# Bhoreal_Slimpro.net
KiCad netlist of a schematic drawn in EAGLE
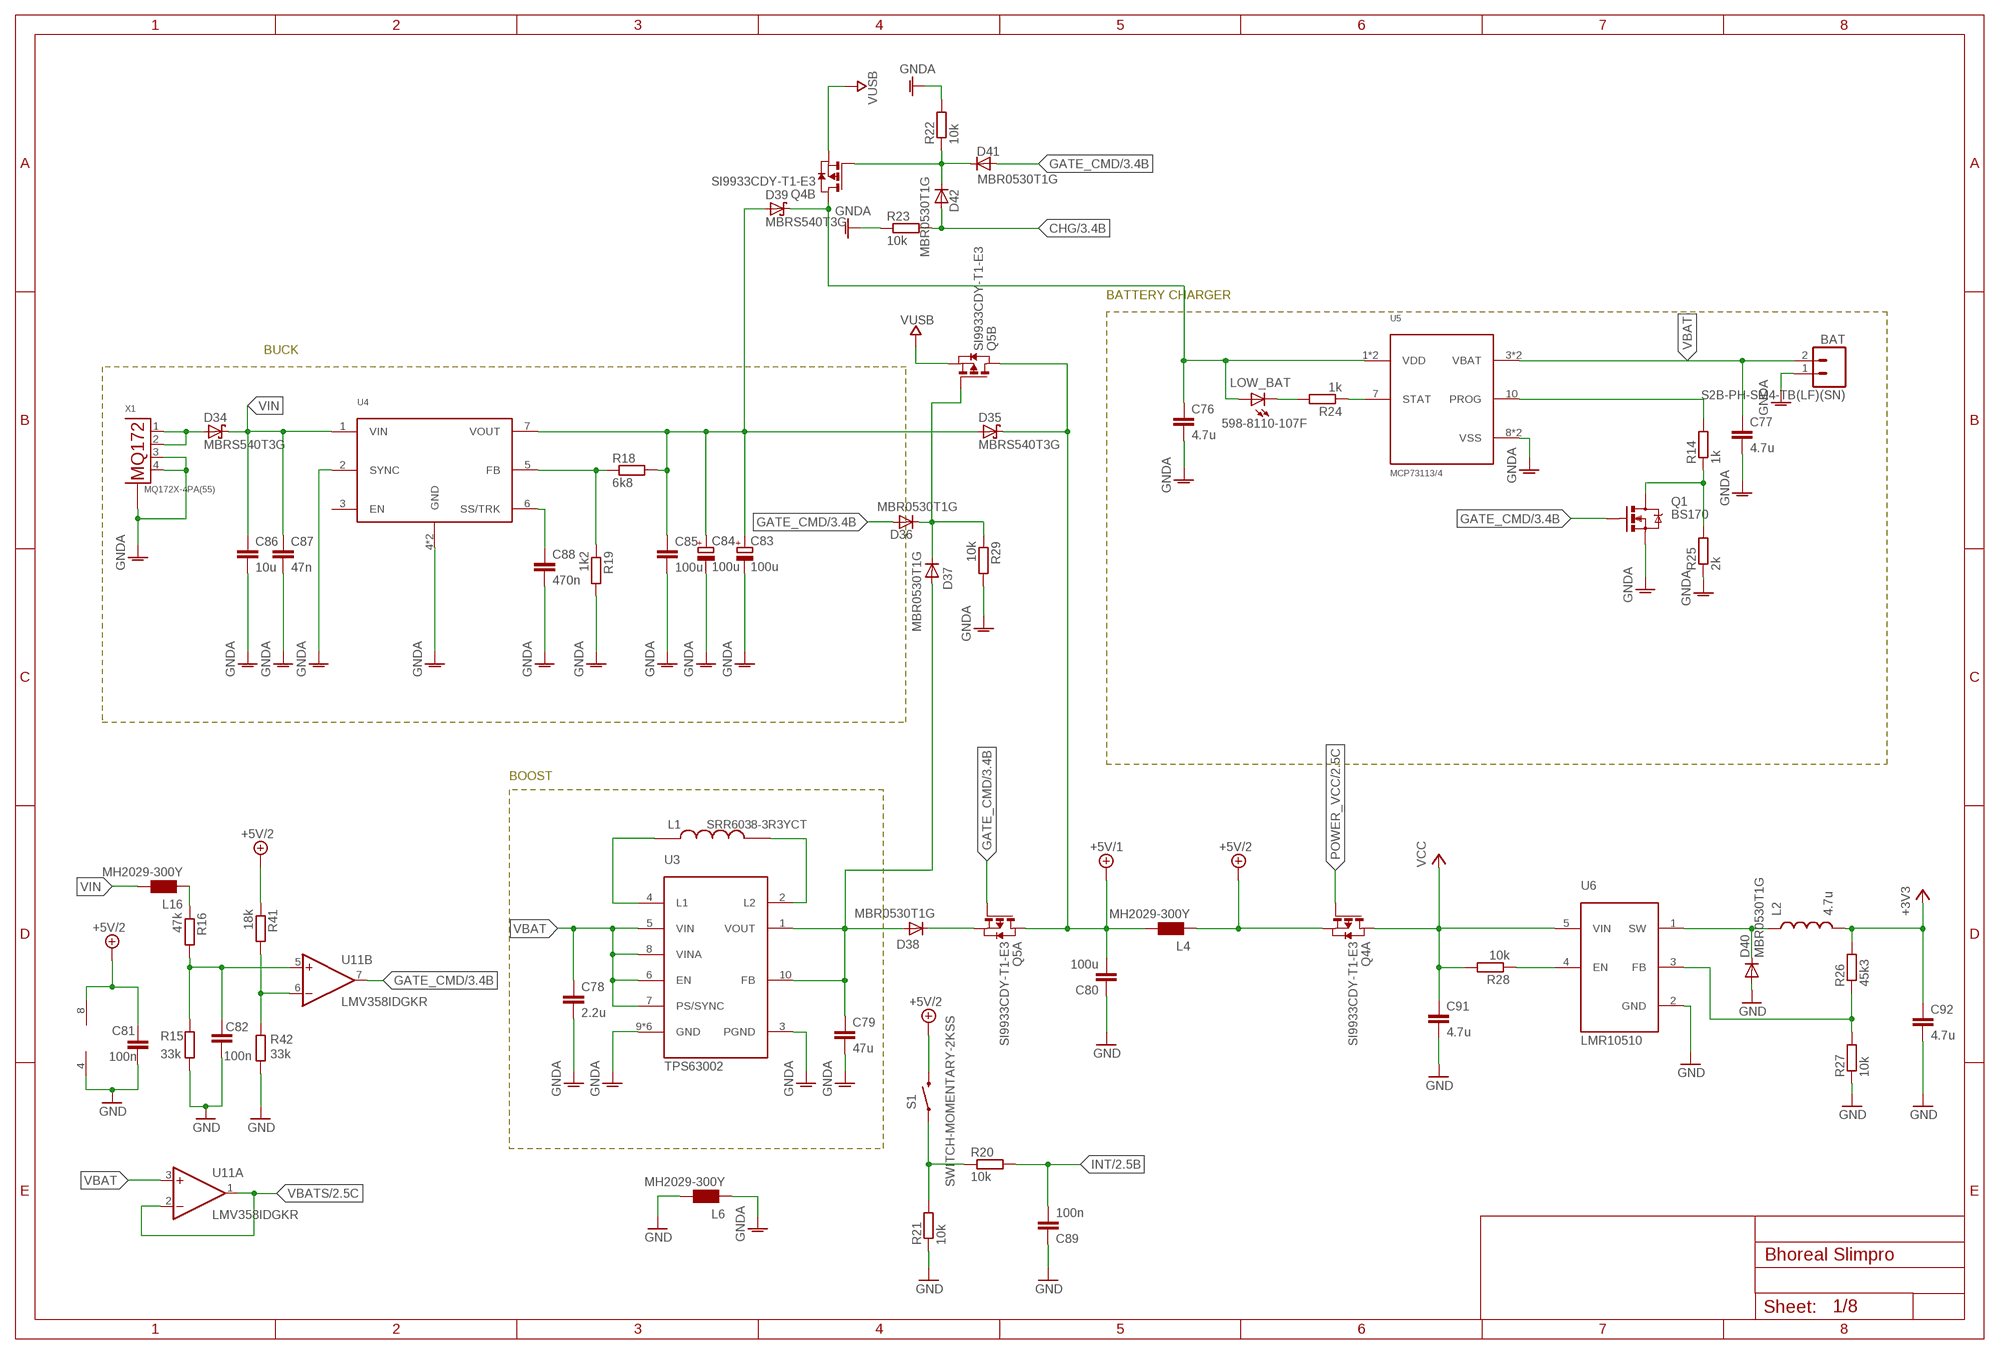
[diagram p0: schematic, sheet 1]
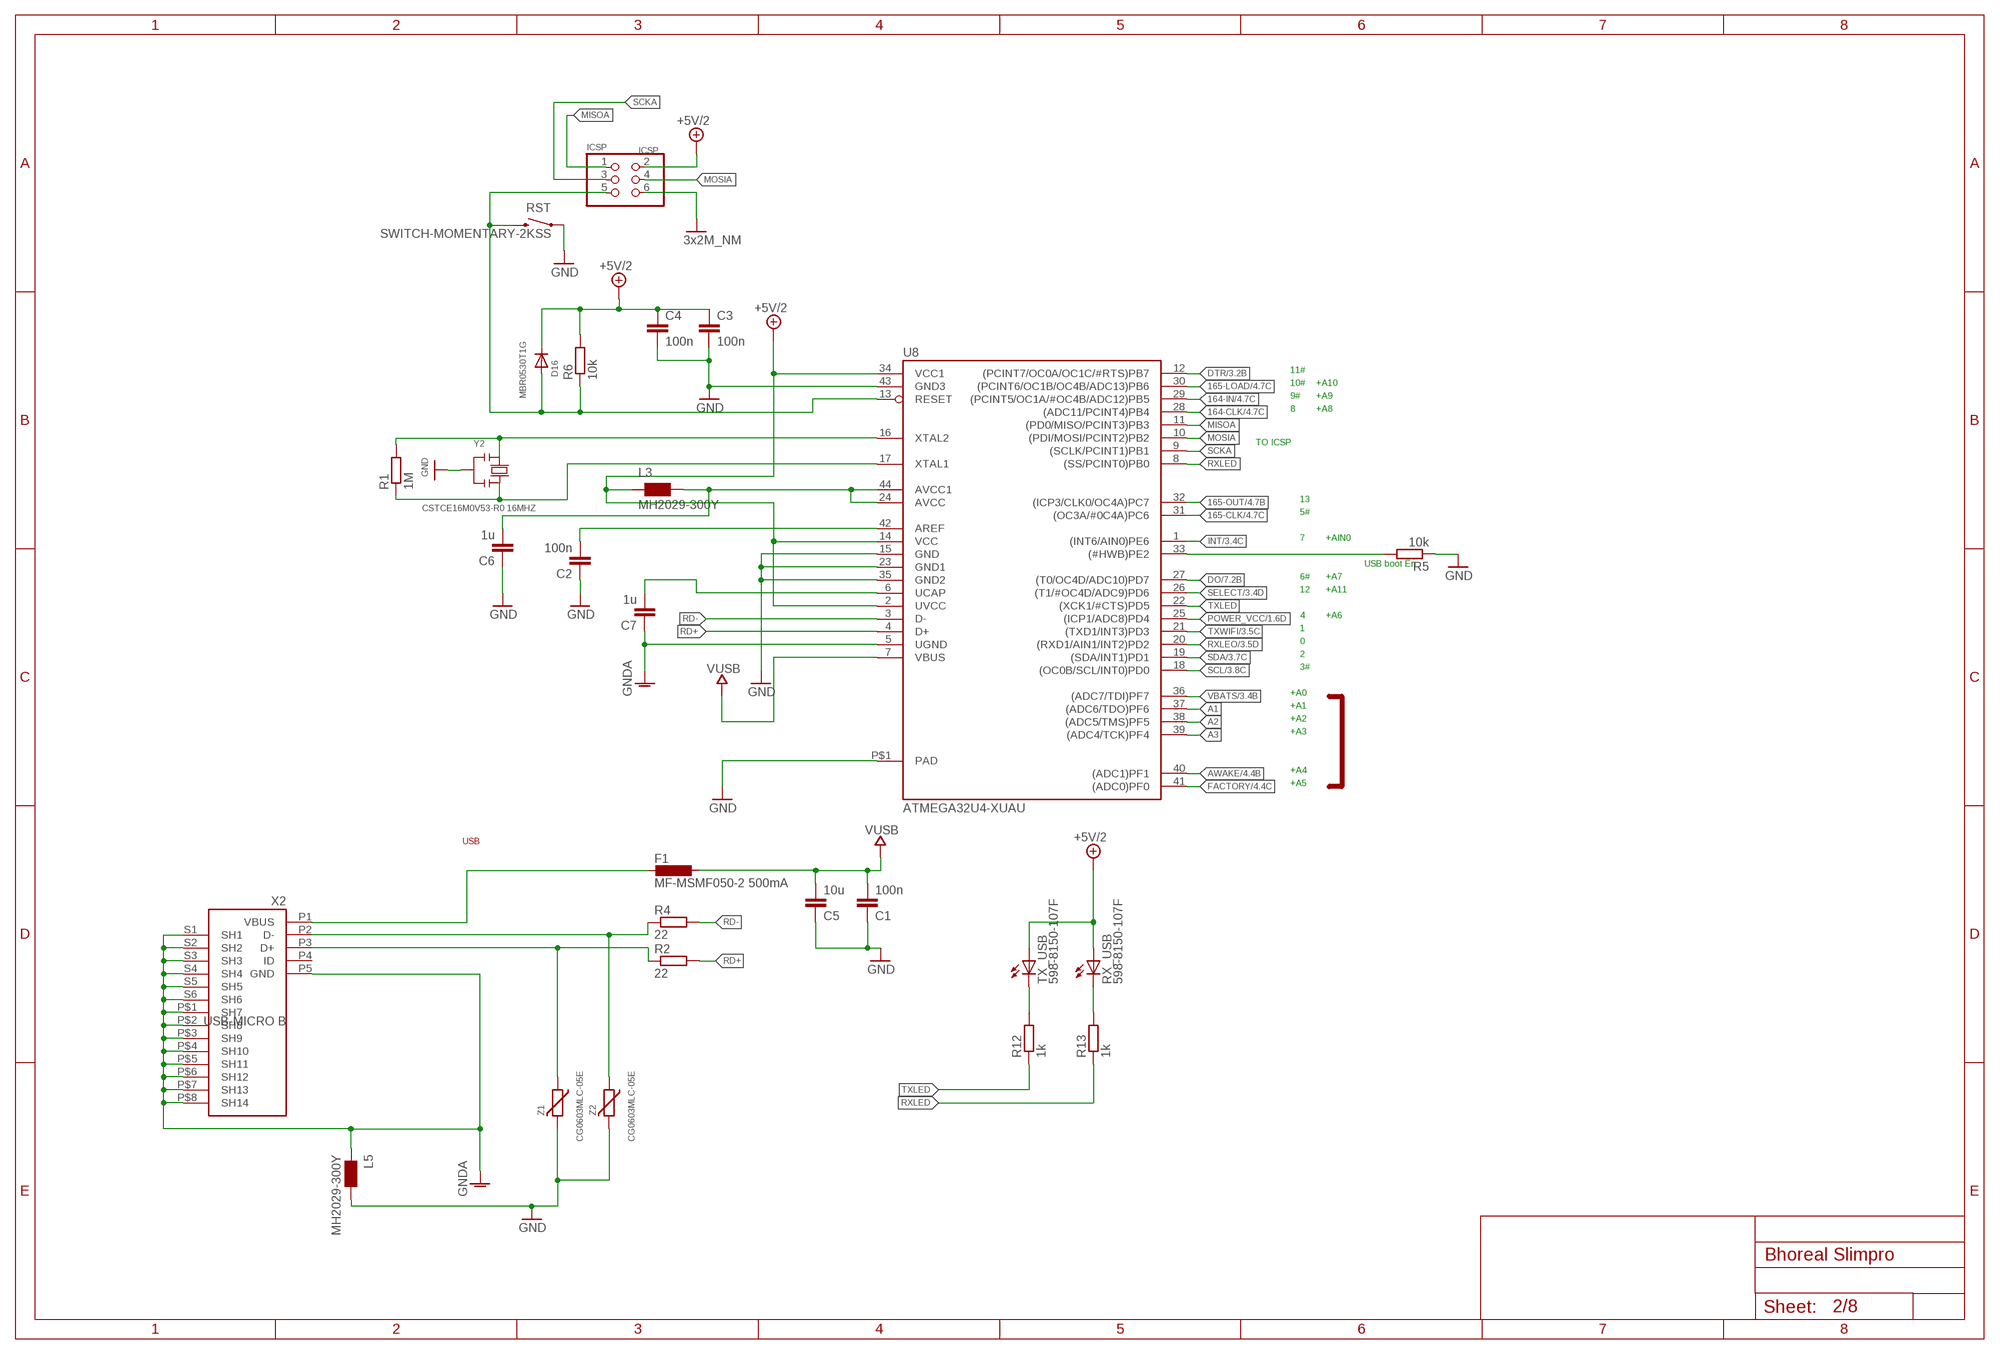
[diagram p1: schematic, sheet 2]
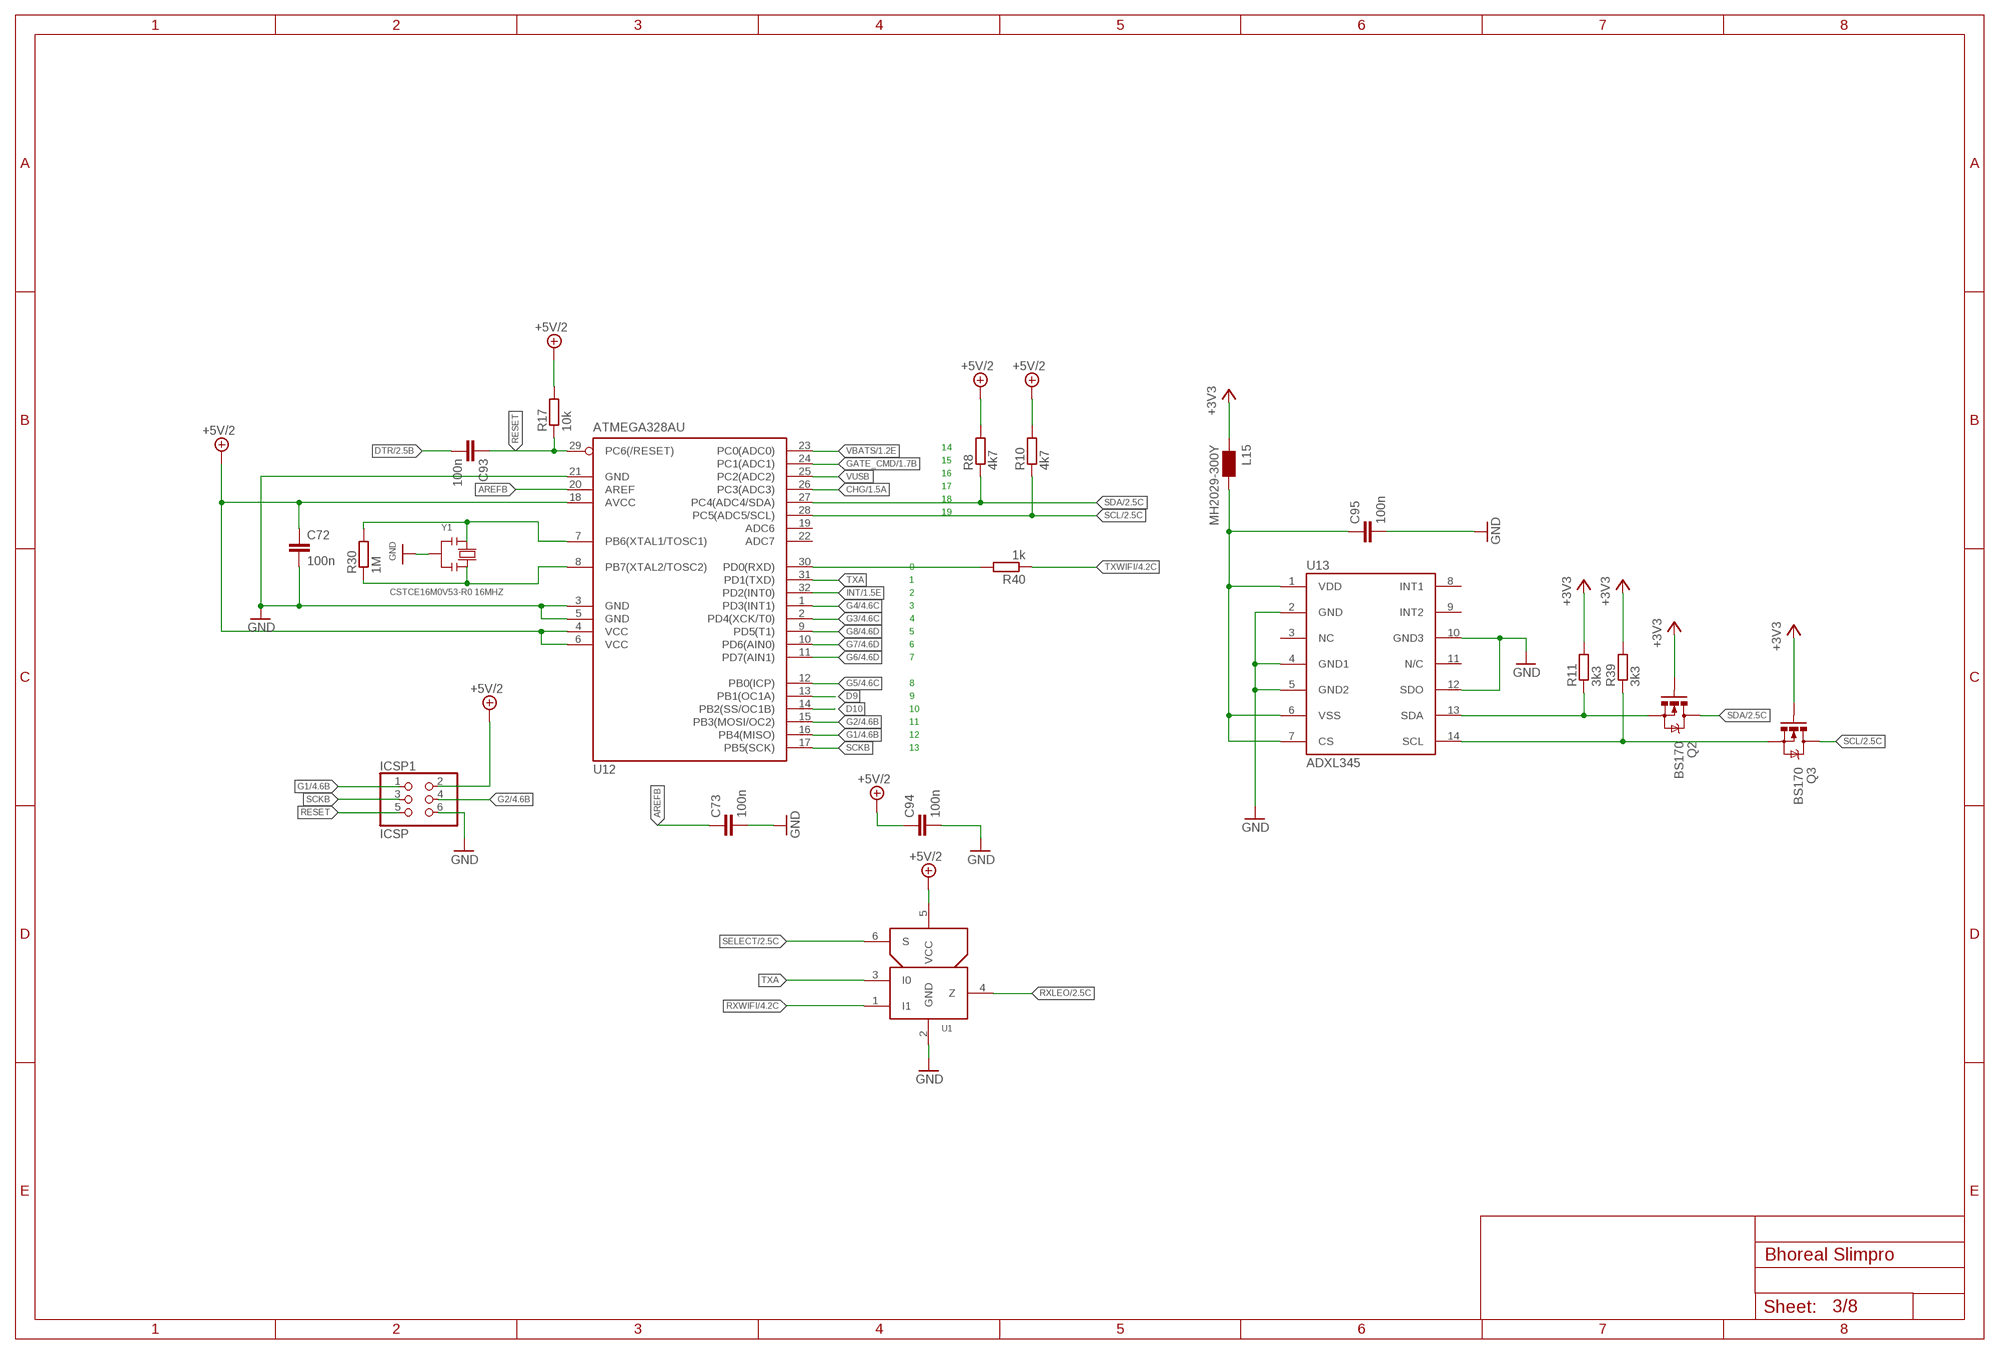
[diagram p2: schematic, sheet 3]
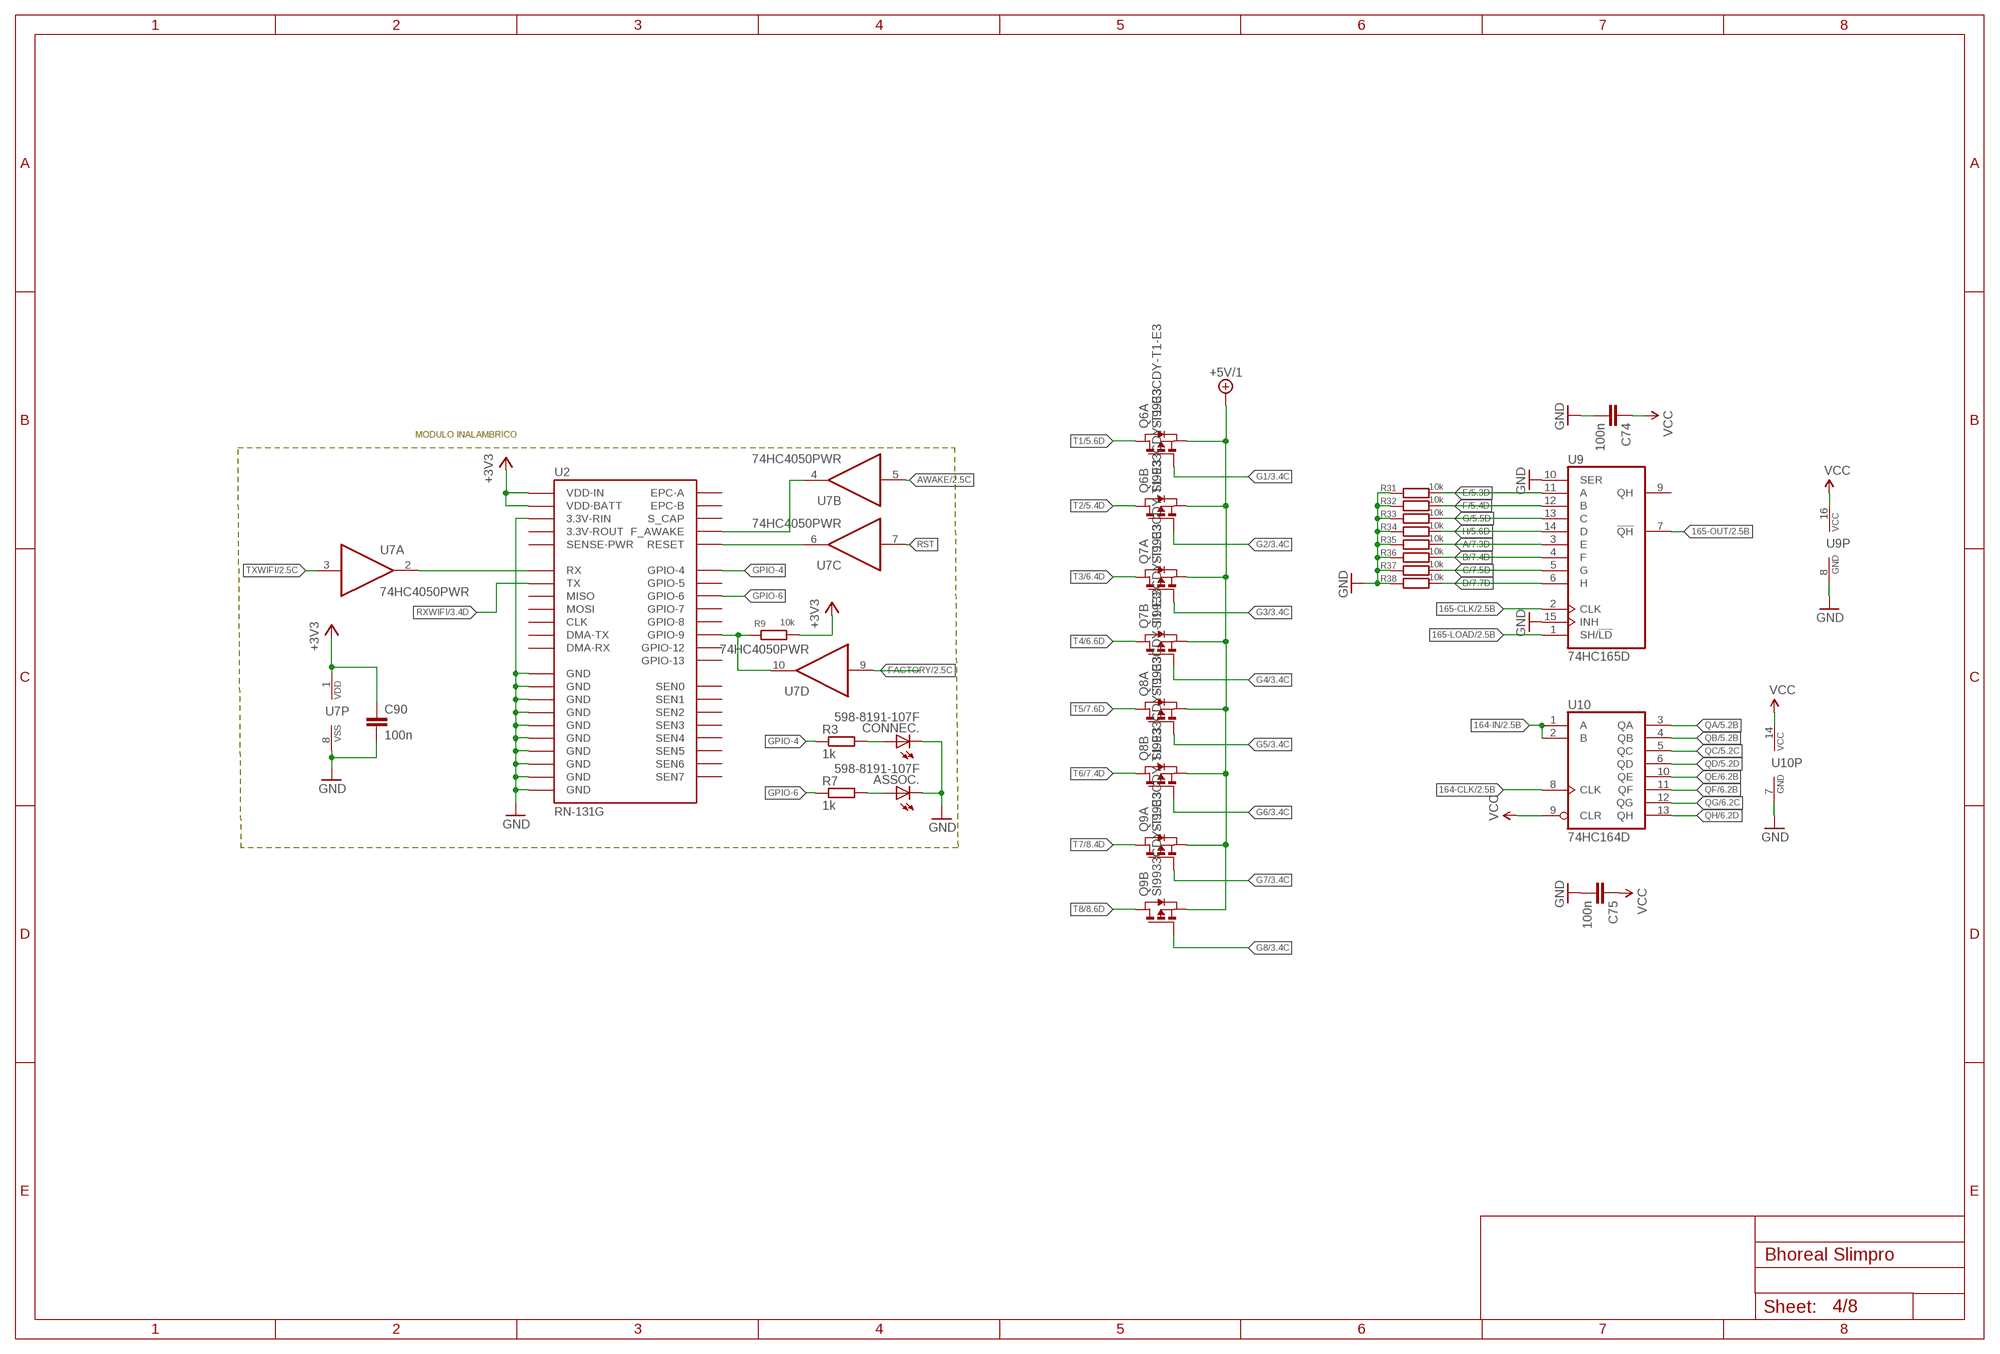
[diagram p3: schematic, sheet 4]
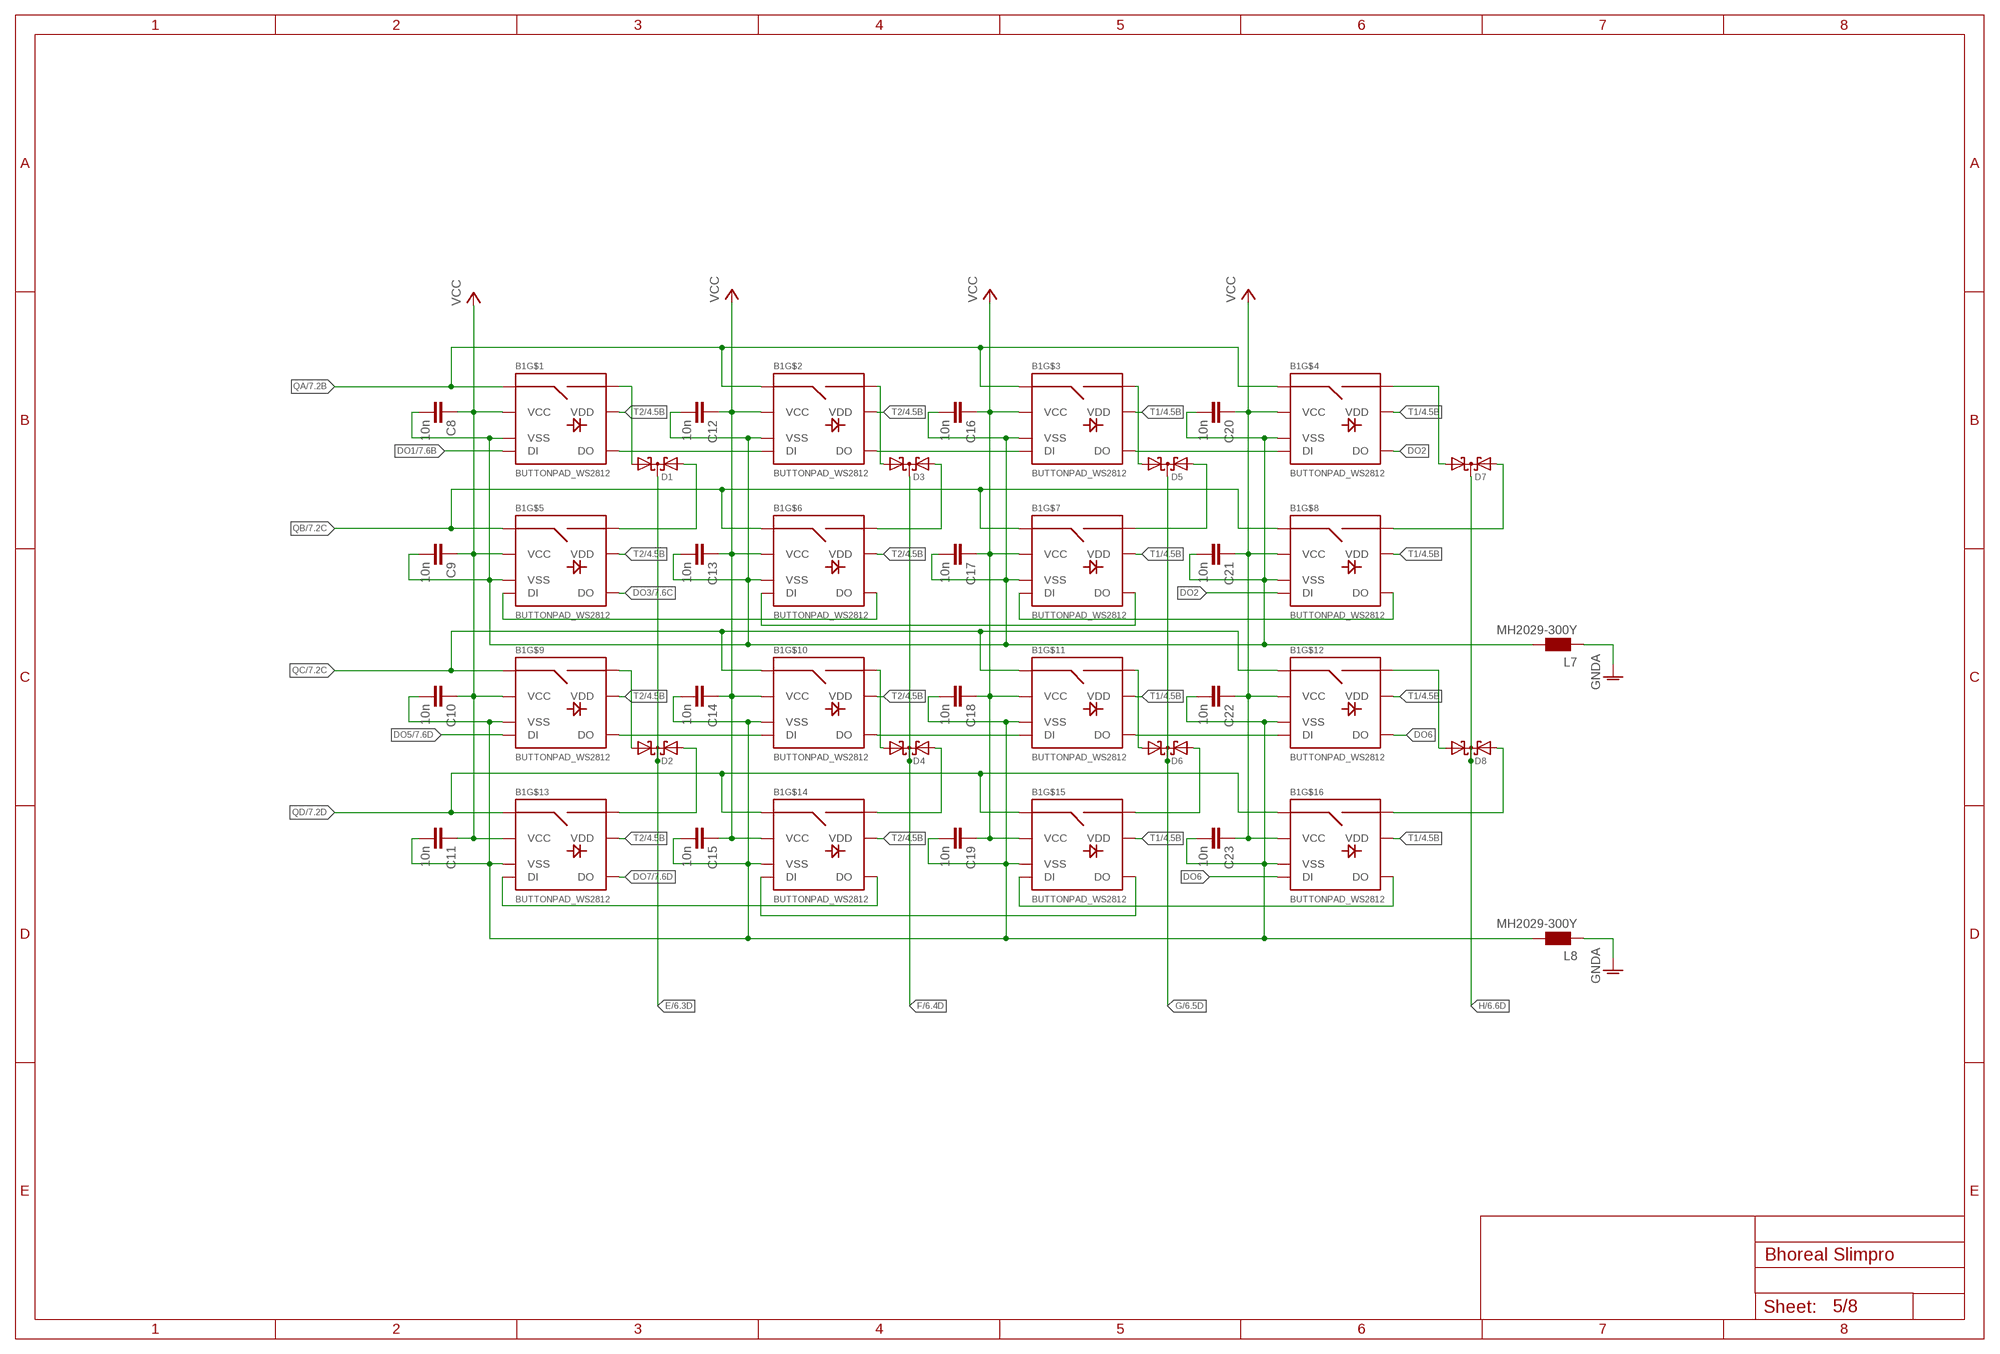
[diagram p4: schematic, sheet 5]
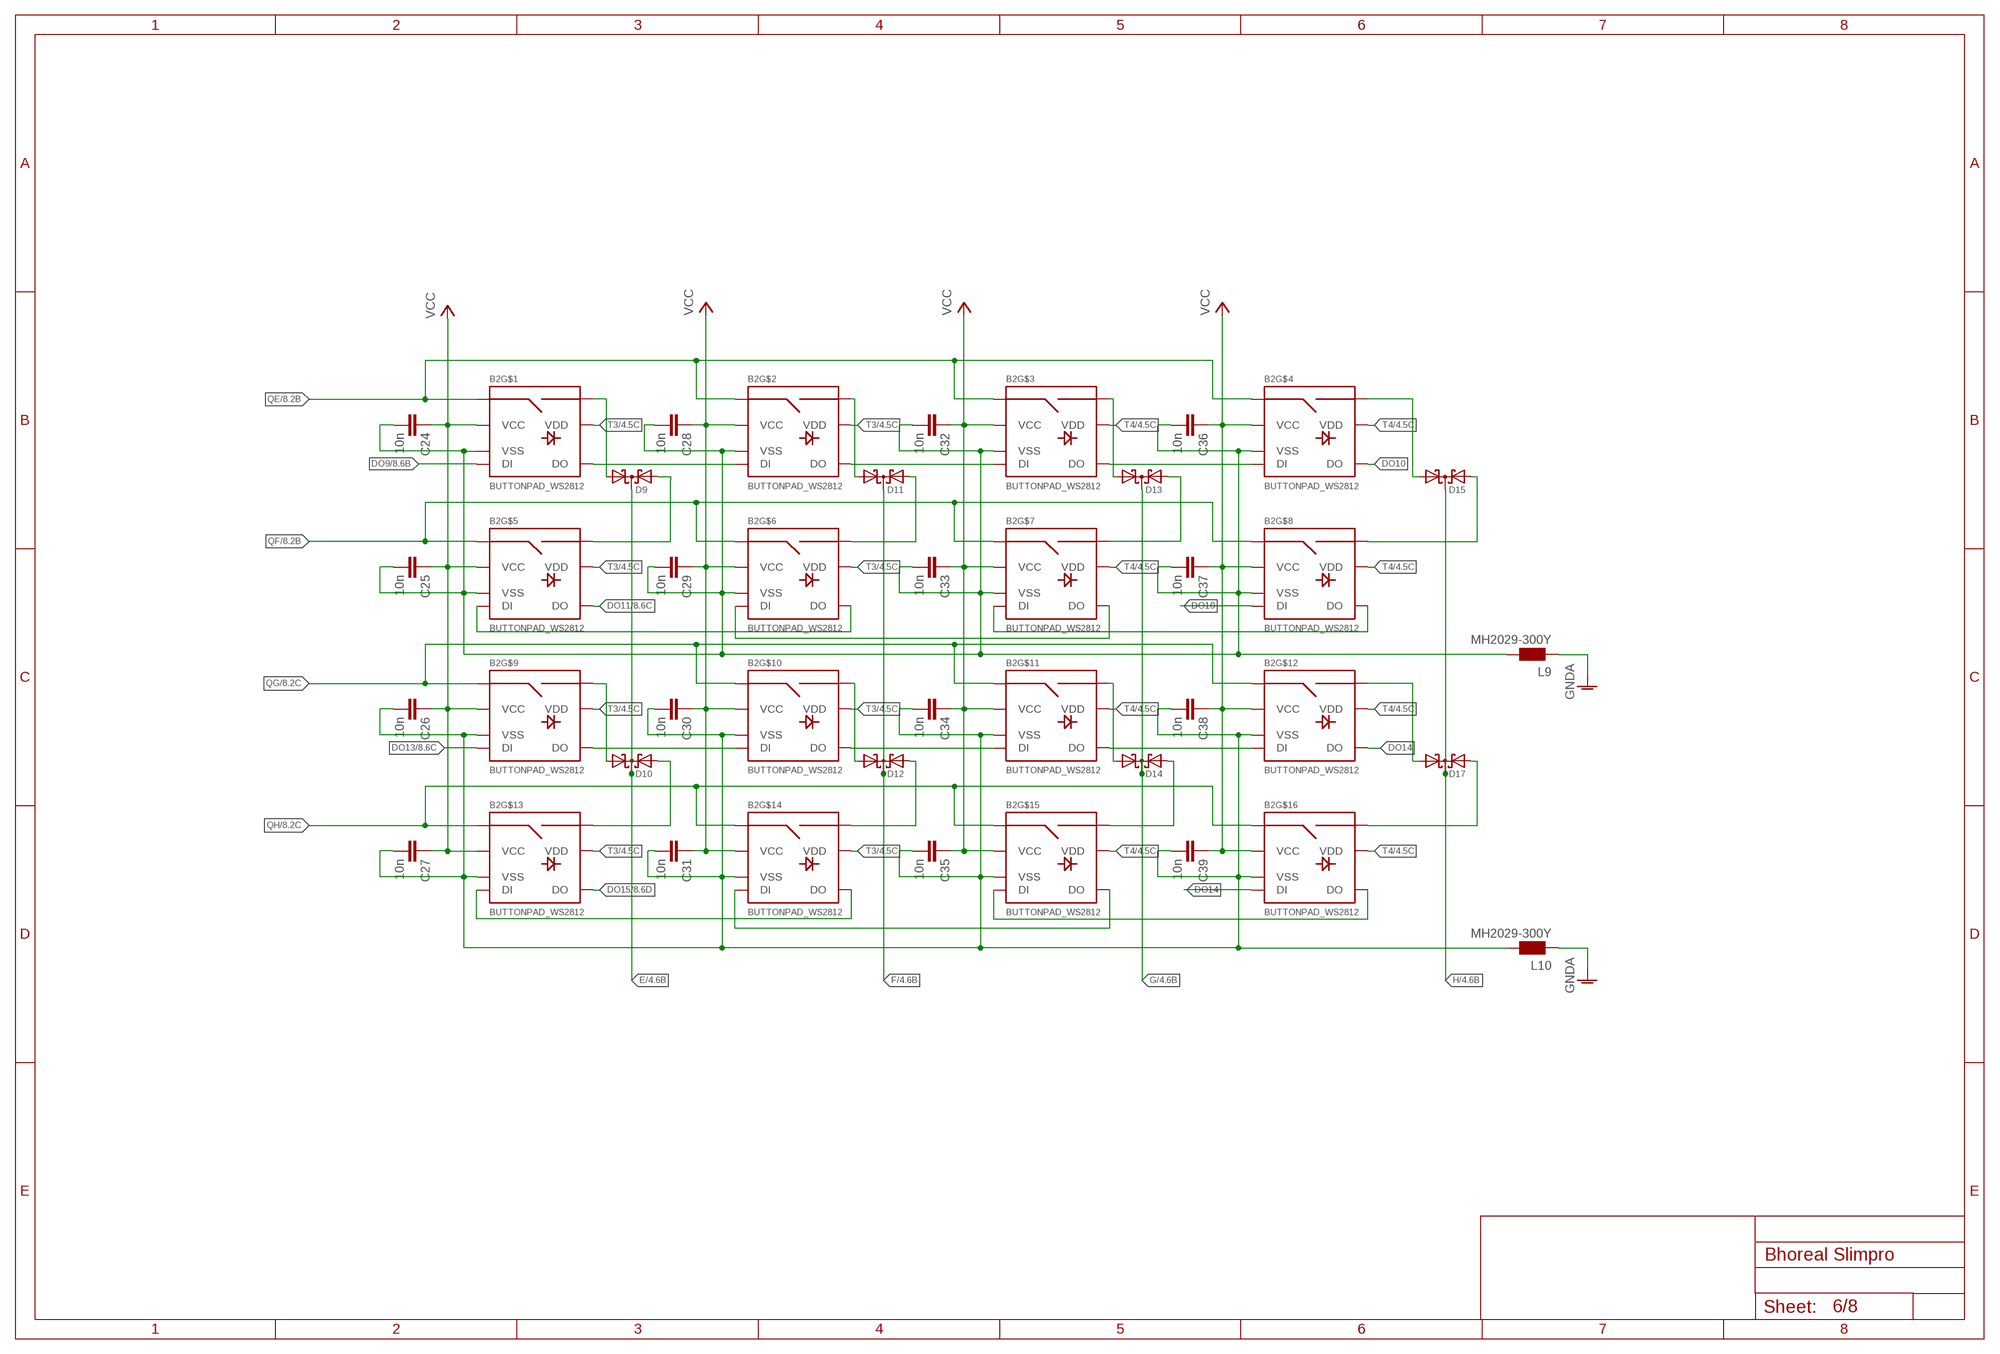
[diagram p5: schematic, sheet 6]
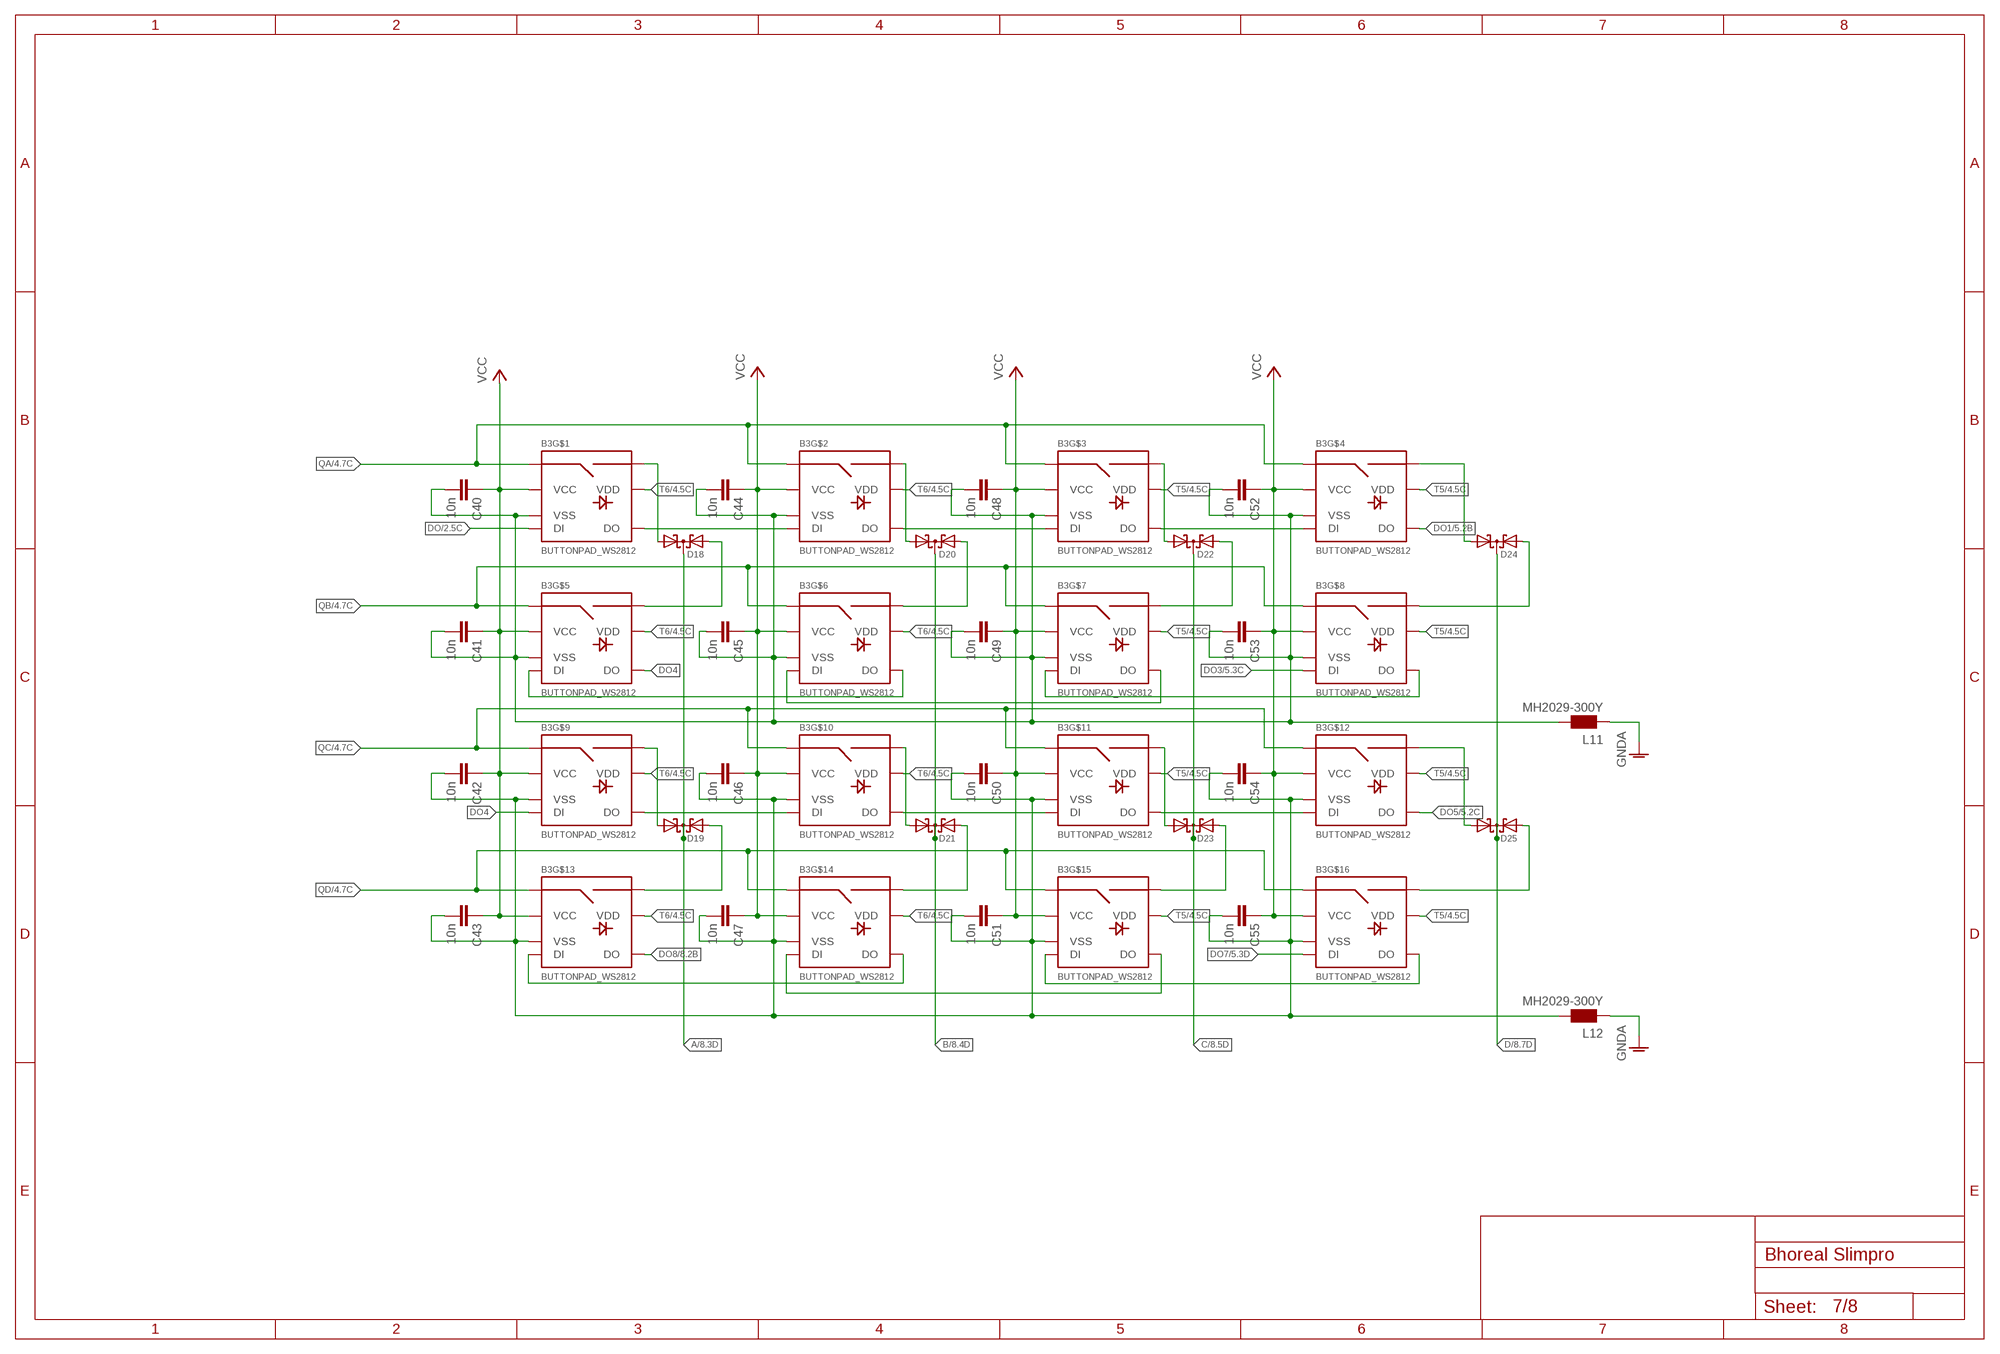
[diagram p6: schematic, sheet 7]
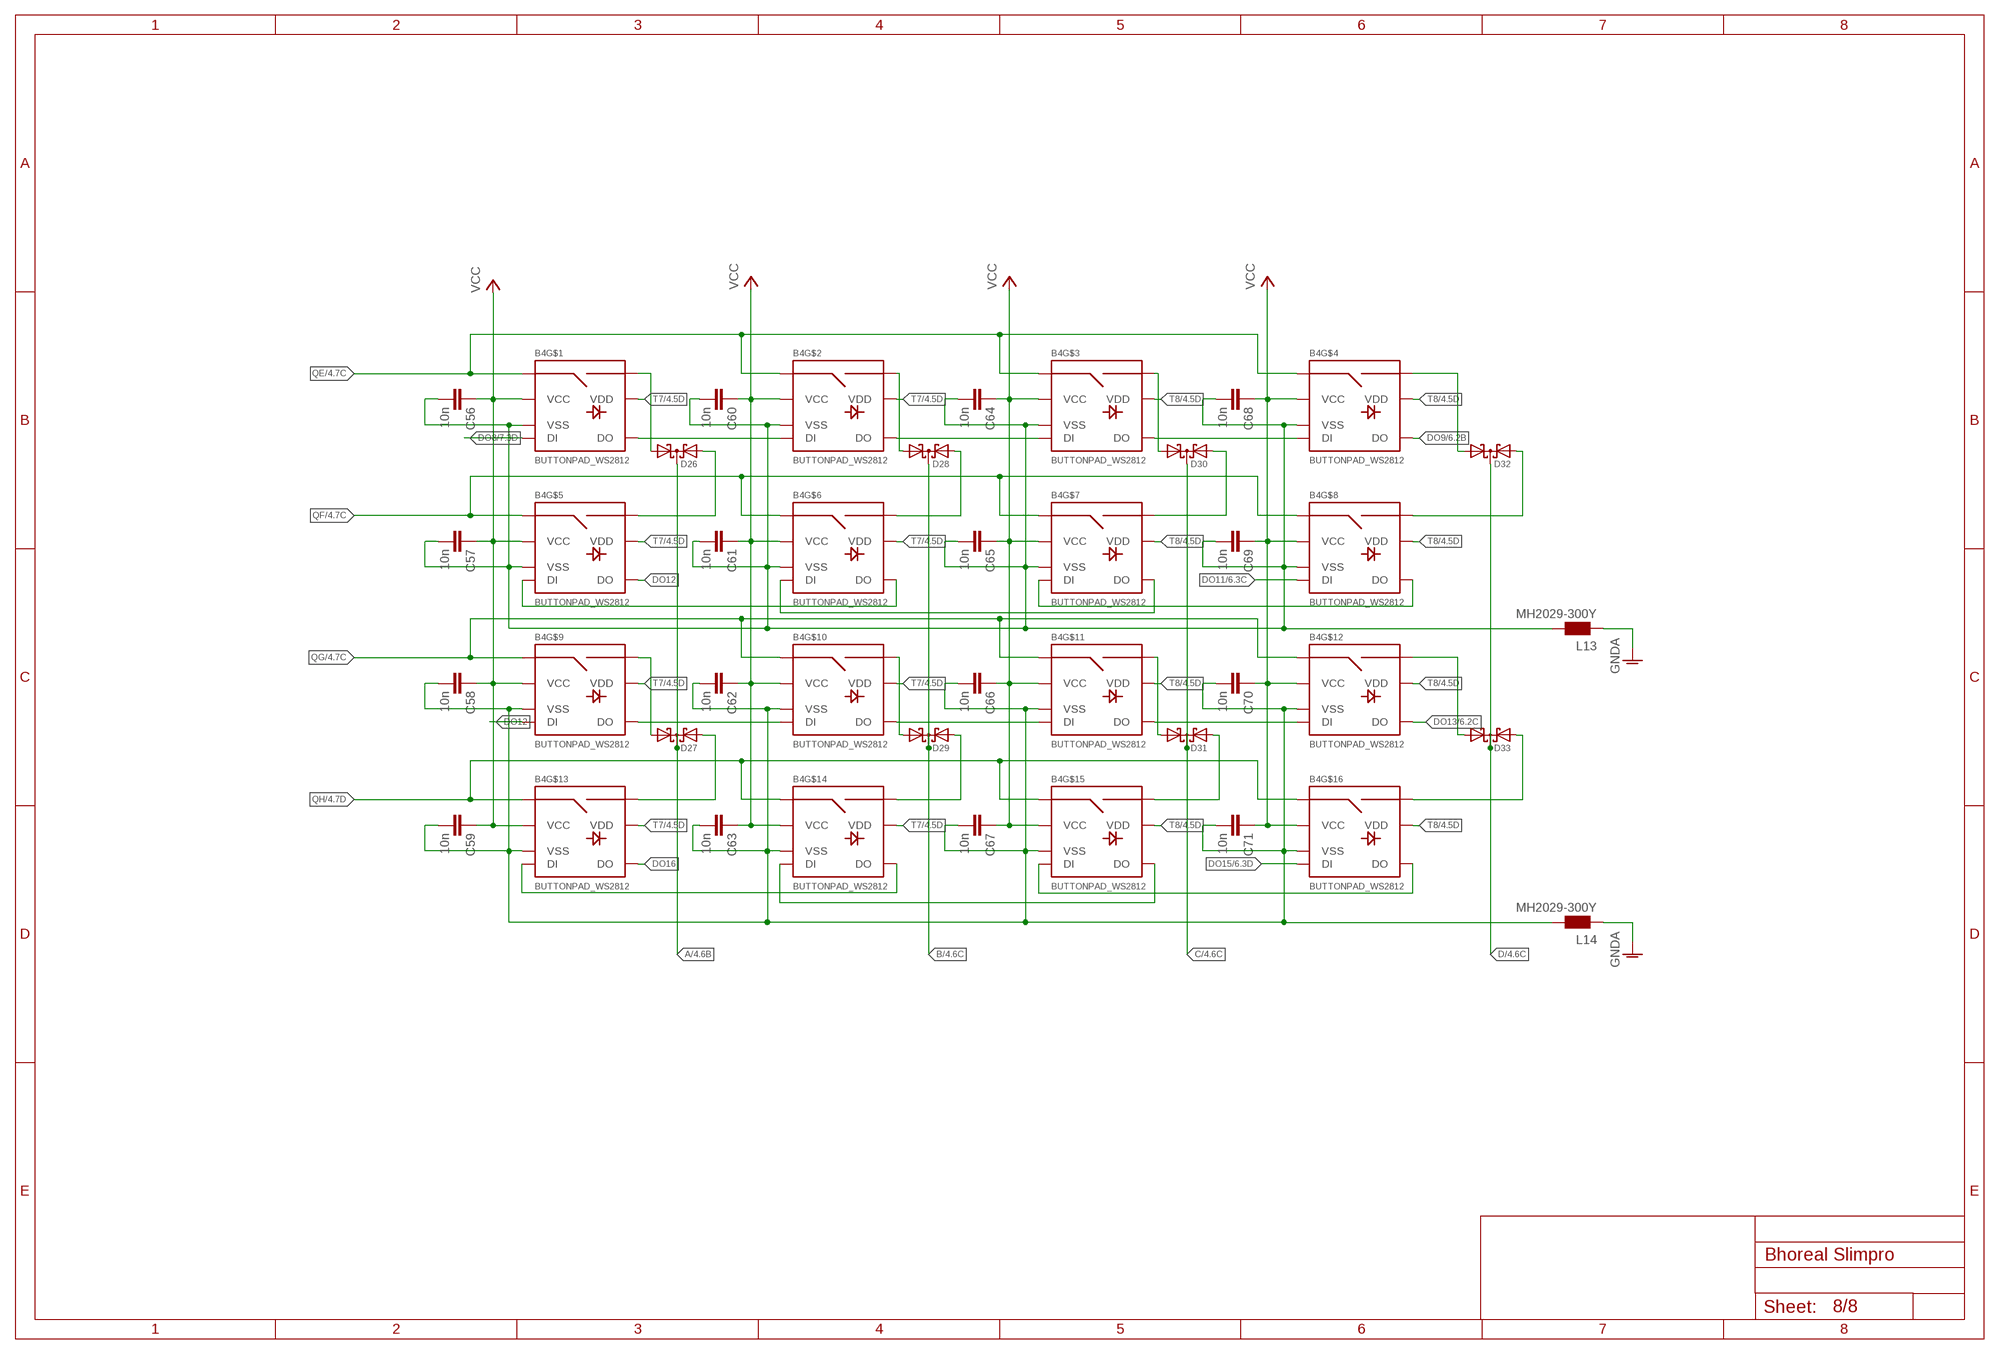
[diagram p7: schematic, sheet 8]

(export (version "E")
  (design (tool "Eeschema 10.0.6"))
  (components
    (comp (ref "ASSOC.")
      (value "598-8191-107F")
      (footprint "eagle-import:CHIP-LED0805")
      (libsource (lib "eagle-import") (part "LEDCHIP-LED0805"))
    )
    (comp (ref "C74")
      (value "100n")
      (footprint "eagle-import:C0603")
      (libsource (lib "eagle-import") (part "rcl_C-EUC0603"))
    )
    (comp (ref "C75")
      (value "100n")
      (footprint "eagle-import:C0603")
      (libsource (lib "eagle-import") (part "rcl_C-EUC0603"))
    )
    (comp (ref "C90")
      (value "100n")
      (footprint "eagle-import:C0603")
      (libsource (lib "eagle-import") (part "rcl_C-EUC0603"))
    )
    (comp (ref "CONNEC.")
      (value "598-8191-107F")
      (footprint "eagle-import:CHIP-LED0805")
      (libsource (lib "eagle-import") (part "LEDCHIP-LED0805"))
    )
    (comp (ref "Q6")
      (value "SI9933CDY-T1-E3")
      (footprint "eagle-import:SO8")
      (libsource (lib "eagle-import") (part "PMOS2SO8"))
    )
    (comp (ref "Q7")
      (value "SI9933CDY-T1-E3")
      (footprint "eagle-import:SO8")
      (libsource (lib "eagle-import") (part "PMOS2SO8"))
    )
    (comp (ref "Q8")
      (value "SI9933CDY-T1-E3")
      (footprint "eagle-import:SO8")
      (libsource (lib "eagle-import") (part "PMOS2SO8"))
    )
    (comp (ref "Q9")
      (value "SI9933CDY-T1-E3")
      (footprint "eagle-import:SO8")
      (libsource (lib "eagle-import") (part "PMOS2SO8"))
    )
    (comp (ref "R3")
      (value "1k")
      (footprint "eagle-import:R0603")
      (libsource (lib "eagle-import") (part "R-EU_R0603"))
    )
    (comp (ref "R7")
      (value "1k")
      (footprint "eagle-import:R0603")
      (libsource (lib "eagle-import") (part "R-EU_R0603"))
    )
    (comp (ref "R9")
      (value "10k")
      (footprint "eagle-import:R0603")
      (libsource (lib "eagle-import") (part "R-EU_R0603"))
    )
    (comp (ref "R31")
      (value "10k")
      (footprint "eagle-import:R0603")
      (libsource (lib "eagle-import") (part "R-EU_R0603"))
    )
    (comp (ref "R32")
      (value "10k")
      (footprint "eagle-import:R0603")
      (libsource (lib "eagle-import") (part "R-EU_R0603"))
    )
    (comp (ref "R33")
      (value "10k")
      (footprint "eagle-import:R0603")
      (libsource (lib "eagle-import") (part "R-EU_R0603"))
    )
    (comp (ref "R34")
      (value "10k")
      (footprint "eagle-import:R0603")
      (libsource (lib "eagle-import") (part "R-EU_R0603"))
    )
    (comp (ref "R35")
      (value "10k")
      (footprint "eagle-import:R0603")
      (libsource (lib "eagle-import") (part "R-EU_R0603"))
    )
    (comp (ref "R36")
      (value "10k")
      (footprint "eagle-import:R0603")
      (libsource (lib "eagle-import") (part "R-EU_R0603"))
    )
    (comp (ref "R37")
      (value "10k")
      (footprint "eagle-import:R0603")
      (libsource (lib "eagle-import") (part "R-EU_R0603"))
    )
    (comp (ref "R38")
      (value "10k")
      (footprint "eagle-import:R0603")
      (libsource (lib "eagle-import") (part "R-EU_R0603"))
    )
    (comp (ref "U2")
      (value "RN-131G")
      (footprint "eagle-import:RN-131G")
      (libsource (lib "eagle-import") (part "RN-131G"))
    )
    (comp (ref "U7")
      (value "74HC4050PWR")
      (footprint "eagle-import:TSSOP16")
      (libsource (lib "eagle-import") (part "74HC4050PWR"))
    )
    (comp (ref "U9")
      (value "74HC165D")
      (footprint "eagle-import:SO16")
      (libsource (lib "eagle-import") (part "74165DHC"))
    )
    (comp (ref "U10")
      (value "74HC164D")
      (footprint "eagle-import:SO14")
      (libsource (lib "eagle-import") (part "74164DHC"))
    )
    (comp (ref "B4")
      (value "BUTTONPAD_WS2812")
      (footprint "eagle-import:BUTTONPAD_WS2812")
      (libsource (lib "eagle-import") (part "BUTTONPAD_WS2812"))
    )
    (comp (ref "C56")
      (value "10n")
      (footprint "eagle-import:C0603")
      (libsource (lib "eagle-import") (part "rcl_C-EUC0603"))
    )
    (comp (ref "C57")
      (value "10n")
      (footprint "eagle-import:C0603")
      (libsource (lib "eagle-import") (part "rcl_C-EUC0603"))
    )
    (comp (ref "C58")
      (value "10n")
      (footprint "eagle-import:C0603")
      (libsource (lib "eagle-import") (part "rcl_C-EUC0603"))
    )
    (comp (ref "C59")
      (value "10n")
      (footprint "eagle-import:C0603")
      (libsource (lib "eagle-import") (part "rcl_C-EUC0603"))
    )
    (comp (ref "C60")
      (value "10n")
      (footprint "eagle-import:C0603")
      (libsource (lib "eagle-import") (part "rcl_C-EUC0603"))
    )
    (comp (ref "C61")
      (value "10n")
      (footprint "eagle-import:C0603")
      (libsource (lib "eagle-import") (part "rcl_C-EUC0603"))
    )
    (comp (ref "C62")
      (value "10n")
      (footprint "eagle-import:C0603")
      (libsource (lib "eagle-import") (part "rcl_C-EUC0603"))
    )
    (comp (ref "C63")
      (value "10n")
      (footprint "eagle-import:C0603")
      (libsource (lib "eagle-import") (part "rcl_C-EUC0603"))
    )
    (comp (ref "C64")
      (value "10n")
      (footprint "eagle-import:C0603")
      (libsource (lib "eagle-import") (part "rcl_C-EUC0603"))
    )
    (comp (ref "C65")
      (value "10n")
      (footprint "eagle-import:C0603")
      (libsource (lib "eagle-import") (part "rcl_C-EUC0603"))
    )
    (comp (ref "C66")
      (value "10n")
      (footprint "eagle-import:C0603")
      (libsource (lib "eagle-import") (part "rcl_C-EUC0603"))
    )
    (comp (ref "C67")
      (value "10n")
      (footprint "eagle-import:C0603")
      (libsource (lib "eagle-import") (part "rcl_C-EUC0603"))
    )
    (comp (ref "C68")
      (value "10n")
      (footprint "eagle-import:C0603")
      (libsource (lib "eagle-import") (part "rcl_C-EUC0603"))
    )
    (comp (ref "C69")
      (value "10n")
      (footprint "eagle-import:C0603")
      (libsource (lib "eagle-import") (part "rcl_C-EUC0603"))
    )
    (comp (ref "C70")
      (value "10n")
      (footprint "eagle-import:C0603")
      (libsource (lib "eagle-import") (part "rcl_C-EUC0603"))
    )
    (comp (ref "C71")
      (value "10n")
      (footprint "eagle-import:C0603")
      (libsource (lib "eagle-import") (part "rcl_C-EUC0603"))
    )
    (comp (ref "D26")
      (value "BAV70LT3G")
      (footprint "eagle-import:SOT23")
      (libsource (lib "eagle-import") (part "BAS70-05"))
    )
    (comp (ref "D27")
      (value "BAV70LT3G")
      (footprint "eagle-import:SOT23")
      (libsource (lib "eagle-import") (part "BAS70-05"))
    )
    (comp (ref "D28")
      (value "BAV70LT3G")
      (footprint "eagle-import:SOT23")
      (libsource (lib "eagle-import") (part "BAS70-05"))
    )
    (comp (ref "D29")
      (value "BAV70LT3G")
      (footprint "eagle-import:SOT23")
      (libsource (lib "eagle-import") (part "BAS70-05"))
    )
    (comp (ref "D30")
      (value "BAV70LT3G")
      (footprint "eagle-import:SOT23")
      (libsource (lib "eagle-import") (part "BAS70-05"))
    )
    (comp (ref "D31")
      (value "BAV70LT3G")
      (footprint "eagle-import:SOT23")
      (libsource (lib "eagle-import") (part "BAS70-05"))
    )
    (comp (ref "D32")
      (value "BAV70LT3G")
      (footprint "eagle-import:SOT23")
      (libsource (lib "eagle-import") (part "BAS70-05"))
    )
    (comp (ref "D33")
      (value "BAV70LT3G")
      (footprint "eagle-import:SOT23")
      (libsource (lib "eagle-import") (part "BAS70-05"))
    )
    (comp (ref "L13")
      (value "MH2029-300Y")
      (footprint "eagle-import:0805")
      (libsource (lib "eagle-import") (part "WE-CBF_0805"))
    )
    (comp (ref "L14")
      (value "MH2029-300Y")
      (footprint "eagle-import:0805")
      (libsource (lib "eagle-import") (part "WE-CBF_0805"))
    )
    (comp (ref "B2")
      (value "BUTTONPAD_WS2812")
      (footprint "eagle-import:BUTTONPAD_WS2812")
      (libsource (lib "eagle-import") (part "BUTTONPAD_WS2812"))
    )
    (comp (ref "C24")
      (value "10n")
      (footprint "eagle-import:C0603")
      (libsource (lib "eagle-import") (part "rcl_C-EUC0603"))
    )
    (comp (ref "C25")
      (value "10n")
      (footprint "eagle-import:C0603")
      (libsource (lib "eagle-import") (part "rcl_C-EUC0603"))
    )
    (comp (ref "C26")
      (value "10n")
      (footprint "eagle-import:C0603")
      (libsource (lib "eagle-import") (part "rcl_C-EUC0603"))
    )
    (comp (ref "C27")
      (value "10n")
      (footprint "eagle-import:C0603")
      (libsource (lib "eagle-import") (part "rcl_C-EUC0603"))
    )
    (comp (ref "C28")
      (value "10n")
      (footprint "eagle-import:C0603")
      (libsource (lib "eagle-import") (part "rcl_C-EUC0603"))
    )
    (comp (ref "C29")
      (value "10n")
      (footprint "eagle-import:C0603")
      (libsource (lib "eagle-import") (part "rcl_C-EUC0603"))
    )
    (comp (ref "C30")
      (value "10n")
      (footprint "eagle-import:C0603")
      (libsource (lib "eagle-import") (part "rcl_C-EUC0603"))
    )
    (comp (ref "C31")
      (value "10n")
      (footprint "eagle-import:C0603")
      (libsource (lib "eagle-import") (part "rcl_C-EUC0603"))
    )
    (comp (ref "C32")
      (value "10n")
      (footprint "eagle-import:C0603")
      (libsource (lib "eagle-import") (part "rcl_C-EUC0603"))
    )
    (comp (ref "C33")
      (value "10n")
      (footprint "eagle-import:C0603")
      (libsource (lib "eagle-import") (part "rcl_C-EUC0603"))
    )
    (comp (ref "C34")
      (value "10n")
      (footprint "eagle-import:C0603")
      (libsource (lib "eagle-import") (part "rcl_C-EUC0603"))
    )
    (comp (ref "C35")
      (value "10n")
      (footprint "eagle-import:C0603")
      (libsource (lib "eagle-import") (part "rcl_C-EUC0603"))
    )
    (comp (ref "C36")
      (value "10n")
      (footprint "eagle-import:C0603")
      (libsource (lib "eagle-import") (part "rcl_C-EUC0603"))
    )
    (comp (ref "C37")
      (value "10n")
      (footprint "eagle-import:C0603")
      (libsource (lib "eagle-import") (part "rcl_C-EUC0603"))
    )
    (comp (ref "C38")
      (value "10n")
      (footprint "eagle-import:C0603")
      (libsource (lib "eagle-import") (part "rcl_C-EUC0603"))
    )
    (comp (ref "C39")
      (value "10n")
      (footprint "eagle-import:C0603")
      (libsource (lib "eagle-import") (part "rcl_C-EUC0603"))
    )
    (comp (ref "D9")
      (value "BAV70LT3G")
      (footprint "eagle-import:SOT23")
      (libsource (lib "eagle-import") (part "BAS70-05"))
    )
    (comp (ref "D10")
      (value "BAV70LT3G")
      (footprint "eagle-import:SOT23")
      (libsource (lib "eagle-import") (part "BAS70-05"))
    )
    (comp (ref "D11")
      (value "BAV70LT3G")
      (footprint "eagle-import:SOT23")
      (libsource (lib "eagle-import") (part "BAS70-05"))
    )
    (comp (ref "D12")
      (value "BAV70LT3G")
      (footprint "eagle-import:SOT23")
      (libsource (lib "eagle-import") (part "BAS70-05"))
    )
    (comp (ref "D13")
      (value "BAV70LT3G")
      (footprint "eagle-import:SOT23")
      (libsource (lib "eagle-import") (part "BAS70-05"))
    )
    (comp (ref "D14")
      (value "BAV70LT3G")
      (footprint "eagle-import:SOT23")
      (libsource (lib "eagle-import") (part "BAS70-05"))
    )
    (comp (ref "D15")
      (value "BAV70LT3G")
      (footprint "eagle-import:SOT23")
      (libsource (lib "eagle-import") (part "BAS70-05"))
    )
    (comp (ref "D17")
      (value "BAV70LT3G")
      (footprint "eagle-import:SOT23")
      (libsource (lib "eagle-import") (part "BAS70-05"))
    )
    (comp (ref "L9")
      (value "MH2029-300Y")
      (footprint "eagle-import:0805")
      (libsource (lib "eagle-import") (part "WE-CBF_0805"))
    )
    (comp (ref "L10")
      (value "MH2029-300Y")
      (footprint "eagle-import:0805")
      (libsource (lib "eagle-import") (part "WE-CBF_0805"))
    )
    (comp (ref "BAT")
      (value "S2B-PH-SM4-TB(LF)(SN)")
      (footprint "eagle-import:S2B-PH")
      (libsource (lib "eagle-import") (part "M02-JST-2MM-SMT"))
    )
    (comp (ref "C76")
      (value "4.7u")
      (footprint "eagle-import:C0805")
      (libsource (lib "eagle-import") (part "rcl_C-EUC0805"))
    )
    (comp (ref "C77")
      (value "4.7u")
      (footprint "eagle-import:C0805")
      (libsource (lib "eagle-import") (part "rcl_C-EUC0805"))
    )
    (comp (ref "C78")
      (value "2.2u")
      (footprint "eagle-import:C0805")
      (libsource (lib "eagle-import") (part "rcl_C-EUC0805"))
    )
    (comp (ref "C79")
      (value "47u")
      (footprint "eagle-import:C1812")
      (libsource (lib "eagle-import") (part "rcl_C-EUC1812"))
    )
    (comp (ref "C80")
      (value "100u")
      (footprint "eagle-import:C1206")
      (libsource (lib "eagle-import") (part "rcl_C-EUC1206"))
    )
    (comp (ref "C81")
      (value "100n")
      (footprint "eagle-import:C0603")
      (libsource (lib "eagle-import") (part "rcl_C-EUC0603"))
    )
    (comp (ref "C82")
      (value "100n")
      (footprint "eagle-import:C0603")
      (libsource (lib "eagle-import") (part "rcl_C-EUC0603"))
    )
    (comp (ref "C83")
      (value "100u")
      (footprint "eagle-import:D_7343-31R")
      (libsource (lib "eagle-import") (part "CPOL-EUD/7343-31R"))
    )
    (comp (ref "C84")
      (value "100u")
      (footprint "eagle-import:D_7343-31R")
      (libsource (lib "eagle-import") (part "CPOL-EUD/7343-31R"))
    )
    (comp (ref "C85")
      (value "100u")
      (footprint "eagle-import:C1210")
      (libsource (lib "eagle-import") (part "rcl_C-EUC1210"))
    )
    (comp (ref "C86")
      (value "10u")
      (footprint "eagle-import:C1210")
      (libsource (lib "eagle-import") (part "rcl_C-EUC1210"))
    )
    (comp (ref "C87")
      (value "47n")
      (footprint "eagle-import:C1206")
      (libsource (lib "eagle-import") (part "rcl_C-EUC1206"))
    )
    (comp (ref "C88")
      (value "470n")
      (footprint "eagle-import:C0805")
      (libsource (lib "eagle-import") (part "rcl_C-EUC0805"))
    )
    (comp (ref "C89")
      (value "100n")
      (footprint "eagle-import:C0603")
      (libsource (lib "eagle-import") (part "rcl_C-EUC0603"))
    )
    (comp (ref "C91")
      (value "4.7u")
      (footprint "eagle-import:C0603")
      (libsource (lib "eagle-import") (part "rcl_C-EUC0603"))
    )
    (comp (ref "C92")
      (value "4.7u")
      (footprint "eagle-import:C0603")
      (libsource (lib "eagle-import") (part "rcl_C-EUC0603"))
    )
    (comp (ref "D34")
      (value "MBRS540T3G")
      (footprint "eagle-import:SMC")
      (libsource (lib "eagle-import") (part "SCHOTTKY-DIODESMC"))
    )
    (comp (ref "D35")
      (value "MBRS540T3G")
      (footprint "eagle-import:SMC")
      (libsource (lib "eagle-import") (part "SCHOTTKY-DIODESMC"))
    )
    (comp (ref "D36")
      (value "MBR0530T1G")
      (footprint "eagle-import:SOD123")
      (libsource (lib "eagle-import") (part "DIODE-SOD123"))
    )
    (comp (ref "D37")
      (value "MBR0530T1G")
      (footprint "eagle-import:SOD123")
      (libsource (lib "eagle-import") (part "DIODE-SOD123"))
    )
    (comp (ref "D38")
      (value "MBR0530T1G")
      (footprint "eagle-import:SOD123")
      (libsource (lib "eagle-import") (part "DIODE-SOD123"))
    )
    (comp (ref "D39")
      (value "MBRS540T3G")
      (footprint "eagle-import:SMC")
      (libsource (lib "eagle-import") (part "SCHOTTKY-DIODESMC"))
    )
    (comp (ref "D40")
      (value "MBR0530T1G")
      (footprint "eagle-import:SOD123")
      (libsource (lib "eagle-import") (part "DIODE-SOD123"))
    )
    (comp (ref "D41")
      (value "MBR0530T1G")
      (footprint "eagle-import:SOD123")
      (libsource (lib "eagle-import") (part "DIODE-SOD123"))
    )
    (comp (ref "D42")
      (value "MBR0530T1G")
      (footprint "eagle-import:SOD123")
      (libsource (lib "eagle-import") (part "DIODE-SOD123"))
    )
    (comp (ref "L1")
      (value "SRR6038-3R3YCT")
      (footprint "eagle-import:SRR6038")
      (libsource (lib "eagle-import") (part "LSRR6038"))
    )
    (comp (ref "L2")
      (value "4.7u")
      (footprint "eagle-import:1210")
      (libsource (lib "eagle-import") (part "INDUCTOR1210"))
    )
    (comp (ref "L4")
      (value "MH2029-300Y")
      (footprint "eagle-import:0805")
      (libsource (lib "eagle-import") (part "WE-CBF_0805"))
    )
    (comp (ref "L6")
      (value "MH2029-300Y")
      (footprint "eagle-import:0805")
      (libsource (lib "eagle-import") (part "WE-CBF_0805"))
    )
    (comp (ref "L16")
      (value "MH2029-300Y")
      (footprint "eagle-import:0805")
      (libsource (lib "eagle-import") (part "WE-CBF_0805"))
    )
    (comp (ref "LOW_BAT")
      (value "598-8110-107F")
      (footprint "eagle-import:CHIP-LED0805")
      (libsource (lib "eagle-import") (part "LEDCHIP-LED0805"))
    )
    (comp (ref "Q1")
      (value "BS170")
      (footprint "eagle-import:SOT23")
      (libsource (lib "eagle-import") (part "MOSFET-NCHANNELBSS123LT1G"))
    )
    (comp (ref "Q4")
      (value "SI9933CDY-T1-E3")
      (footprint "eagle-import:SO8")
      (libsource (lib "eagle-import") (part "PMOS2SO8"))
    )
    (comp (ref "Q5")
      (value "SI9933CDY-T1-E3")
      (footprint "eagle-import:SO8")
      (libsource (lib "eagle-import") (part "PMOS2SO8"))
    )
    (comp (ref "R14")
      (value "1k")
      (footprint "eagle-import:R0603")
      (libsource (lib "eagle-import") (part "R-EU_R0603"))
    )
    (comp (ref "R15")
      (value "33k")
      (footprint "eagle-import:R0603")
      (libsource (lib "eagle-import") (part "R-EU_R0603"))
    )
    (comp (ref "R16")
      (value "47k")
      (footprint "eagle-import:R0603")
      (libsource (lib "eagle-import") (part "R-EU_R0603"))
    )
    (comp (ref "R18")
      (value "6k8")
      (footprint "eagle-import:R0603")
      (libsource (lib "eagle-import") (part "R-EU_R0603"))
    )
    (comp (ref "R19")
      (value "1k2")
      (footprint "eagle-import:R0603")
      (libsource (lib "eagle-import") (part "R-EU_R0603"))
    )
    (comp (ref "R20")
      (value "10k")
      (footprint "eagle-import:R0603")
      (libsource (lib "eagle-import") (part "R-EU_R0603"))
    )
    (comp (ref "R21")
      (value "10k")
      (footprint "eagle-import:R0603")
      (libsource (lib "eagle-import") (part "R-EU_R0603"))
    )
    (comp (ref "R22")
      (value "10k")
      (footprint "eagle-import:R0603")
      (libsource (lib "eagle-import") (part "R-EU_R0603"))
    )
    (comp (ref "R23")
      (value "10k")
      (footprint "eagle-import:R0603")
      (libsource (lib "eagle-import") (part "R-EU_R0603"))
    )
    (comp (ref "R24")
      (value "1k")
      (footprint "eagle-import:R0603")
      (libsource (lib "eagle-import") (part "R-EU_R0603"))
    )
    (comp (ref "R25")
      (value "2k")
      (footprint "eagle-import:R0603")
      (libsource (lib "eagle-import") (part "R-EU_R0603"))
    )
    (comp (ref "R26")
      (value "45k3")
      (footprint "eagle-import:R0603")
      (libsource (lib "eagle-import") (part "R-EU_R0603"))
    )
    (comp (ref "R27")
      (value "10k")
      (footprint "eagle-import:R0603")
      (libsource (lib "eagle-import") (part "R-EU_R0603"))
    )
    (comp (ref "R28")
      (value "10k")
      (footprint "eagle-import:R0603")
      (libsource (lib "eagle-import") (part "R-EU_R0603"))
    )
    (comp (ref "R29")
      (value "10k")
      (footprint "eagle-import:R0603")
      (libsource (lib "eagle-import") (part "R-EU_R0603"))
    )
    (comp (ref "R41")
      (value "18k")
      (footprint "eagle-import:R0603")
      (libsource (lib "eagle-import") (part "R-EU_R0603"))
    )
    (comp (ref "R42")
      (value "33k")
      (footprint "eagle-import:R0603")
      (libsource (lib "eagle-import") (part "R-EU_R0603"))
    )
    (comp (ref "S1")
      (value "SWITCH-MOMENTARY-2KSS")
      (footprint "eagle-import:KSS241G")
      (libsource (lib "eagle-import") (part "SWITCH-MOMENTARY-2KSS"))
    )
    (comp (ref "U3")
      (value "TPS63002")
      (footprint "eagle-import:QFN-10_PAD")
      (libsource (lib "eagle-import") (part "TPS63002"))
    )
    (comp (ref "U4")
      (value "LMZ2200X")
      (footprint "eagle-import:TO-PMOD")
      (libsource (lib "eagle-import") (part "LMZ2200X"))
    )
    (comp (ref "U5")
      (value "MCP73113/4")
      (footprint "eagle-import:DFN-10")
      (libsource (lib "eagle-import") (part "MCP73113/4"))
    )
    (comp (ref "U6")
      (value "LMR10510")
      (footprint "eagle-import:SOT23-5L")
      (libsource (lib "eagle-import") (part "LMR10510SOT23"))
    )
    (comp (ref "U11")
      (value "LMV358IDGKR")
      (footprint "eagle-import:MSOP08")
      (libsource (lib "eagle-import") (part "LMV358?MMX"))
    )
    (comp (ref "X1")
      (value "MQ172X-4PA(55)")
      (footprint "eagle-import:MQ172X-4PA(55)")
      (libsource (lib "eagle-import") (part "MQ172X-4PA(55)"))
    )
    (comp (ref "C72")
      (value "100n")
      (footprint "eagle-import:C0603")
      (libsource (lib "eagle-import") (part "rcl_C-EUC0603"))
    )
    (comp (ref "C73")
      (value "100n")
      (footprint "eagle-import:C0603")
      (libsource (lib "eagle-import") (part "rcl_C-EUC0603"))
    )
    (comp (ref "C93")
      (value "100n")
      (footprint "eagle-import:C0603")
      (libsource (lib "eagle-import") (part "rcl_C-EUC0603"))
    )
    (comp (ref "C94")
      (value "100n")
      (footprint "eagle-import:C0603")
      (libsource (lib "eagle-import") (part "rcl_C-EUC0603"))
    )
    (comp (ref "C95")
      (value "100n")
      (footprint "eagle-import:C0603")
      (libsource (lib "eagle-import") (part "rcl_C-EUC0603"))
    )
    (comp (ref "ICSP1")
      (value "ICSP")
      (footprint "eagle-import:2X03")
      (libsource (lib "eagle-import") (part "pinhead_PINHD-2X3"))
    )
    (comp (ref "L15")
      (value "MH2029-300Y")
      (footprint "eagle-import:0805")
      (libsource (lib "eagle-import") (part "WE-CBF_0805"))
    )
    (comp (ref "Q2")
      (value "BS170")
      (footprint "eagle-import:SOT23")
      (libsource (lib "eagle-import") (part "MOSFET-NCHANNELBSS123LT1G"))
    )
    (comp (ref "Q3")
      (value "BS170")
      (footprint "eagle-import:SOT23")
      (libsource (lib "eagle-import") (part "MOSFET-NCHANNELBSS123LT1G"))
    )
    (comp (ref "R8")
      (value "4k7")
      (footprint "eagle-import:R0603")
      (libsource (lib "eagle-import") (part "R-EU_R0603"))
    )
    (comp (ref "R10")
      (value "4k7")
      (footprint "eagle-import:R0603")
      (libsource (lib "eagle-import") (part "R-EU_R0603"))
    )
    (comp (ref "R11")
      (value "3k3")
      (footprint "eagle-import:R0603")
      (libsource (lib "eagle-import") (part "R-EU_R0603"))
    )
    (comp (ref "R17")
      (value "10k")
      (footprint "eagle-import:R0603")
      (libsource (lib "eagle-import") (part "R-EU_R0603"))
    )
    (comp (ref "R30")
      (value "1M")
      (footprint "eagle-import:R0603")
      (libsource (lib "eagle-import") (part "R-EU_R0603"))
    )
    (comp (ref "R39")
      (value "3k3")
      (footprint "eagle-import:R0603")
      (libsource (lib "eagle-import") (part "R-EU_R0603"))
    )
    (comp (ref "R40")
      (value "1k")
      (footprint "eagle-import:R0603")
      (libsource (lib "eagle-import") (part "R-EU_R0603"))
    )
    (comp (ref "U1")
      (value "NC7SZ157P6X")
      (footprint "eagle-import:SC70")
      (libsource (lib "eagle-import") (part "NC7SV157"))
    )
    (comp (ref "U12")
      (value "ATMEGA328AU")
      (footprint "eagle-import:TQFP32-08")
      (fields (field (name "MPN") "ATMEGA8-16AU"))
      (libsource (lib "eagle-import") (part "MEGA8-AI"))
    )
    (comp (ref "U13")
      (value "ADXL345")
      (footprint "eagle-import:LGA14")
      (libsource (lib "eagle-import") (part "ADXL345"))
    )
    (comp (ref "Y1")
      (value "CSTCE16M0V53-R0 16MHZ")
      (footprint "eagle-import:RESONATOR")
      (libsource (lib "eagle-import") (part "RESONATORMU"))
    )
    (comp (ref "B3")
      (value "BUTTONPAD_WS2812")
      (footprint "eagle-import:BUTTONPAD_WS2812")
      (libsource (lib "eagle-import") (part "BUTTONPAD_WS2812"))
    )
    (comp (ref "C40")
      (value "10n")
      (footprint "eagle-import:C0603")
      (libsource (lib "eagle-import") (part "rcl_C-EUC0603"))
    )
    (comp (ref "C41")
      (value "10n")
      (footprint "eagle-import:C0603")
      (libsource (lib "eagle-import") (part "rcl_C-EUC0603"))
    )
    (comp (ref "C42")
      (value "10n")
      (footprint "eagle-import:C0603")
      (libsource (lib "eagle-import") (part "rcl_C-EUC0603"))
    )
    (comp (ref "C43")
      (value "10n")
      (footprint "eagle-import:C0603")
      (libsource (lib "eagle-import") (part "rcl_C-EUC0603"))
    )
    (comp (ref "C44")
      (value "10n")
      (footprint "eagle-import:C0603")
      (libsource (lib "eagle-import") (part "rcl_C-EUC0603"))
    )
    (comp (ref "C45")
      (value "10n")
      (footprint "eagle-import:C0603")
      (libsource (lib "eagle-import") (part "rcl_C-EUC0603"))
    )
    (comp (ref "C46")
      (value "10n")
      (footprint "eagle-import:C0603")
      (libsource (lib "eagle-import") (part "rcl_C-EUC0603"))
    )
    (comp (ref "C47")
      (value "10n")
      (footprint "eagle-import:C0603")
      (libsource (lib "eagle-import") (part "rcl_C-EUC0603"))
    )
    (comp (ref "C48")
      (value "10n")
      (footprint "eagle-import:C0603")
      (libsource (lib "eagle-import") (part "rcl_C-EUC0603"))
    )
    (comp (ref "C49")
      (value "10n")
      (footprint "eagle-import:C0603")
      (libsource (lib "eagle-import") (part "rcl_C-EUC0603"))
    )
    (comp (ref "C50")
      (value "10n")
      (footprint "eagle-import:C0603")
      (libsource (lib "eagle-import") (part "rcl_C-EUC0603"))
    )
    (comp (ref "C51")
      (value "10n")
      (footprint "eagle-import:C0603")
      (libsource (lib "eagle-import") (part "rcl_C-EUC0603"))
    )
    (comp (ref "C52")
      (value "10n")
      (footprint "eagle-import:C0603")
      (libsource (lib "eagle-import") (part "rcl_C-EUC0603"))
    )
    (comp (ref "C53")
      (value "10n")
      (footprint "eagle-import:C0603")
      (libsource (lib "eagle-import") (part "rcl_C-EUC0603"))
    )
    (comp (ref "C54")
      (value "10n")
      (footprint "eagle-import:C0603")
      (libsource (lib "eagle-import") (part "rcl_C-EUC0603"))
    )
    (comp (ref "C55")
      (value "10n")
      (footprint "eagle-import:C0603")
      (libsource (lib "eagle-import") (part "rcl_C-EUC0603"))
    )
    (comp (ref "D18")
      (value "BAV70LT3G")
      (footprint "eagle-import:SOT23")
      (libsource (lib "eagle-import") (part "BAS70-05"))
    )
    (comp (ref "D19")
      (value "BAV70LT3G")
      (footprint "eagle-import:SOT23")
      (libsource (lib "eagle-import") (part "BAS70-05"))
    )
    (comp (ref "D20")
      (value "BAV70LT3G")
      (footprint "eagle-import:SOT23")
      (libsource (lib "eagle-import") (part "BAS70-05"))
    )
    (comp (ref "D21")
      (value "BAV70LT3G")
      (footprint "eagle-import:SOT23")
      (libsource (lib "eagle-import") (part "BAS70-05"))
    )
    (comp (ref "D22")
      (value "BAV70LT3G")
      (footprint "eagle-import:SOT23")
      (libsource (lib "eagle-import") (part "BAS70-05"))
    )
    (comp (ref "D23")
      (value "BAV70LT3G")
      (footprint "eagle-import:SOT23")
      (libsource (lib "eagle-import") (part "BAS70-05"))
    )
    (comp (ref "D24")
      (value "BAV70LT3G")
      (footprint "eagle-import:SOT23")
      (libsource (lib "eagle-import") (part "BAS70-05"))
    )
    (comp (ref "D25")
      (value "BAV70LT3G")
      (footprint "eagle-import:SOT23")
      (libsource (lib "eagle-import") (part "BAS70-05"))
    )
    (comp (ref "L11")
      (value "MH2029-300Y")
      (footprint "eagle-import:0805")
      (libsource (lib "eagle-import") (part "WE-CBF_0805"))
    )
    (comp (ref "L12")
      (value "MH2029-300Y")
      (footprint "eagle-import:0805")
      (libsource (lib "eagle-import") (part "WE-CBF_0805"))
    )
    (comp (ref "C1")
      (value "100n")
      (footprint "eagle-import:C0603")
      (libsource (lib "eagle-import") (part "rcl_C-EUC0603"))
    )
    (comp (ref "C2")
      (value "100n")
      (footprint "eagle-import:C0603")
      (libsource (lib "eagle-import") (part "rcl_C-EUC0603"))
    )
    (comp (ref "C3")
      (value "100n")
      (footprint "eagle-import:C0603")
      (libsource (lib "eagle-import") (part "rcl_C-EUC0603"))
    )
    (comp (ref "C4")
      (value "100n")
      (footprint "eagle-import:C0603")
      (libsource (lib "eagle-import") (part "rcl_C-EUC0603"))
    )
    (comp (ref "C5")
      (value "10u")
      (footprint "eagle-import:C0805")
      (libsource (lib "eagle-import") (part "C-EUC0805"))
    )
    (comp (ref "C6")
      (value "1u")
      (footprint "eagle-import:C0805")
      (libsource (lib "eagle-import") (part "C-EUC0805"))
    )
    (comp (ref "C7")
      (value "1u")
      (footprint "eagle-import:C0805")
      (libsource (lib "eagle-import") (part "C-EUC0805"))
    )
    (comp (ref "D16")
      (value "MBR0530T1G")
      (footprint "eagle-import:SOD123")
      (libsource (lib "eagle-import") (part "DIODE-SOD123"))
    )
    (comp (ref "F1")
      (value "MF-MSMF050-2 500mA")
      (footprint "eagle-import:L1812")
      (libsource (lib "eagle-import") (part "L-EUL1812"))
    )
    (comp (ref "ICSP")
      (value "ICSP")
      (footprint "eagle-import:2X03")
      (libsource (lib "eagle-import") (part "PINHD-2X3"))
    )
    (comp (ref "L3")
      (value "MH2029-300Y")
      (footprint "eagle-import:0805")
      (libsource (lib "eagle-import") (part "WE-CBF_0805"))
    )
    (comp (ref "L5")
      (value "MH2029-300Y")
      (footprint "eagle-import:0805")
      (libsource (lib "eagle-import") (part "WE-CBF_0805"))
    )
    (comp (ref "R1")
      (value "1M")
      (footprint "eagle-import:R0603")
      (libsource (lib "eagle-import") (part "R-EU_R0603"))
    )
    (comp (ref "R2")
      (value "22")
      (footprint "eagle-import:R0603")
      (libsource (lib "eagle-import") (part "R-EU_R0603"))
    )
    (comp (ref "R4")
      (value "22")
      (footprint "eagle-import:R0603")
      (libsource (lib "eagle-import") (part "R-EU_R0603"))
    )
    (comp (ref "R5")
      (value "10k")
      (footprint "eagle-import:R0603")
      (libsource (lib "eagle-import") (part "R-EU_R0603"))
    )
    (comp (ref "R6")
      (value "10k")
      (footprint "eagle-import:R0603")
      (libsource (lib "eagle-import") (part "R-EU_R0603"))
    )
    (comp (ref "R12")
      (value "1k")
      (footprint "eagle-import:R0603")
      (libsource (lib "eagle-import") (part "R-EU_R0603"))
    )
    (comp (ref "R13")
      (value "1k")
      (footprint "eagle-import:R0603")
      (libsource (lib "eagle-import") (part "R-EU_R0603"))
    )
    (comp (ref "RST")
      (value "SWITCH-MOMENTARY-2KSS")
      (footprint "eagle-import:KSS241G")
      (libsource (lib "eagle-import") (part "SWITCH-MOMENTARY-2KSS"))
    )
    (comp (ref "RX_USB")
      (value "598-8150-107F")
      (footprint "eagle-import:CHIPLED_0805")
      (libsource (lib "eagle-import") (part "LEDCHIPLED_0805"))
    )
    (comp (ref "TX_USB")
      (value "598-8150-107F")
      (footprint "eagle-import:CHIPLED_0805")
      (libsource (lib "eagle-import") (part "LEDCHIPLED_0805"))
    )
    (comp (ref "U8")
      (value "ATMEGA32U4-XUAU")
      (footprint "eagle-import:TQFP44-PAD")
      (libsource (lib "eagle-import") (part "ATMEGA32U4-XUAU"))
    )
    (comp (ref "X2")
      (value "USB-MICRO B")
      (footprint "eagle-import:CON2_USB_MICRO_B_AT")
      (libsource (lib "eagle-import") (part "MYCON2_USB-MINI-B"))
    )
    (comp (ref "Y2")
      (value "CSTCE16M0V53-R0 16MHZ")
      (footprint "eagle-import:RESONATOR")
      (libsource (lib "eagle-import") (part "RESONATORMU"))
    )
    (comp (ref "Z1")
      (value "CG0603MLC-05E")
      (footprint "eagle-import:CT_CN0603")
      (libsource (lib "eagle-import") (part "VARISTORCN0603"))
    )
    (comp (ref "Z2")
      (value "CG0603MLC-05E")
      (footprint "eagle-import:CT_CN0603")
      (libsource (lib "eagle-import") (part "VARISTORCN0603"))
    )
    (comp (ref "B1")
      (value "BUTTONPAD_WS2812")
      (footprint "eagle-import:BUTTONPAD_WS2812")
      (libsource (lib "eagle-import") (part "BUTTONPAD_WS2812"))
    )
    (comp (ref "C8")
      (value "10n")
      (footprint "eagle-import:C0603")
      (libsource (lib "eagle-import") (part "rcl_C-EUC0603"))
    )
    (comp (ref "C9")
      (value "10n")
      (footprint "eagle-import:C0603")
      (libsource (lib "eagle-import") (part "rcl_C-EUC0603"))
    )
    (comp (ref "C10")
      (value "10n")
      (footprint "eagle-import:C0603")
      (libsource (lib "eagle-import") (part "rcl_C-EUC0603"))
    )
    (comp (ref "C11")
      (value "10n")
      (footprint "eagle-import:C0603")
      (libsource (lib "eagle-import") (part "rcl_C-EUC0603"))
    )
    (comp (ref "C12")
      (value "10n")
      (footprint "eagle-import:C0603")
      (libsource (lib "eagle-import") (part "rcl_C-EUC0603"))
    )
    (comp (ref "C13")
      (value "10n")
      (footprint "eagle-import:C0603")
      (libsource (lib "eagle-import") (part "rcl_C-EUC0603"))
    )
    (comp (ref "C14")
      (value "10n")
      (footprint "eagle-import:C0603")
      (libsource (lib "eagle-import") (part "rcl_C-EUC0603"))
    )
    (comp (ref "C15")
      (value "10n")
      (footprint "eagle-import:C0603")
      (libsource (lib "eagle-import") (part "rcl_C-EUC0603"))
    )
    (comp (ref "C16")
      (value "10n")
      (footprint "eagle-import:C0603")
      (libsource (lib "eagle-import") (part "rcl_C-EUC0603"))
    )
    (comp (ref "C17")
      (value "10n")
      (footprint "eagle-import:C0603")
      (libsource (lib "eagle-import") (part "rcl_C-EUC0603"))
    )
    (comp (ref "C18")
      (value "10n")
      (footprint "eagle-import:C0603")
      (libsource (lib "eagle-import") (part "rcl_C-EUC0603"))
    )
    (comp (ref "C19")
      (value "10n")
      (footprint "eagle-import:C0603")
      (libsource (lib "eagle-import") (part "rcl_C-EUC0603"))
    )
    (comp (ref "C20")
      (value "10n")
      (footprint "eagle-import:C0603")
      (libsource (lib "eagle-import") (part "rcl_C-EUC0603"))
    )
    (comp (ref "C21")
      (value "10n")
      (footprint "eagle-import:C0603")
      (libsource (lib "eagle-import") (part "rcl_C-EUC0603"))
    )
    (comp (ref "C22")
      (value "10n")
      (footprint "eagle-import:C0603")
      (libsource (lib "eagle-import") (part "rcl_C-EUC0603"))
    )
    (comp (ref "C23")
      (value "10n")
      (footprint "eagle-import:C0603")
      (libsource (lib "eagle-import") (part "rcl_C-EUC0603"))
    )
    (comp (ref "D1")
      (value "BAV70LT3G")
      (footprint "eagle-import:SOT23")
      (libsource (lib "eagle-import") (part "BAS70-05"))
    )
    (comp (ref "D2")
      (value "BAV70LT3G")
      (footprint "eagle-import:SOT23")
      (libsource (lib "eagle-import") (part "BAS70-05"))
    )
    (comp (ref "D3")
      (value "BAV70LT3G")
      (footprint "eagle-import:SOT23")
      (libsource (lib "eagle-import") (part "BAS70-05"))
    )
    (comp (ref "D4")
      (value "BAV70LT3G")
      (footprint "eagle-import:SOT23")
      (libsource (lib "eagle-import") (part "BAS70-05"))
    )
    (comp (ref "D5")
      (value "BAV70LT3G")
      (footprint "eagle-import:SOT23")
      (libsource (lib "eagle-import") (part "BAS70-05"))
    )
    (comp (ref "D6")
      (value "BAV70LT3G")
      (footprint "eagle-import:SOT23")
      (libsource (lib "eagle-import") (part "BAS70-05"))
    )
    (comp (ref "D7")
      (value "BAV70LT3G")
      (footprint "eagle-import:SOT23")
      (libsource (lib "eagle-import") (part "BAS70-05"))
    )
    (comp (ref "D8")
      (value "BAV70LT3G")
      (footprint "eagle-import:SOT23")
      (libsource (lib "eagle-import") (part "BAS70-05"))
    )
    (comp (ref "L7")
      (value "MH2029-300Y")
      (footprint "eagle-import:0805")
      (libsource (lib "eagle-import") (part "WE-CBF_0805"))
    )
    (comp (ref "L8")
      (value "MH2029-300Y")
      (footprint "eagle-import:0805")
      (libsource (lib "eagle-import") (part "WE-CBF_0805"))
    )
  )
  (nets
    (net (code "1") (name "+3V3") (class "Default")
      (node (ref "C90") (pin "1") (pinfunction "1_1") (pintype "passive"))
      (node (ref "C92") (pin "1") (pinfunction "1_1") (pintype "passive"))
      (node (ref "L15") (pin "1") (pinfunction "1_1") (pintype "passive"))
      (node (ref "L2") (pin "2") (pinfunction "2_2") (pintype "passive"))
      (node (ref "Q2") (pin "1") (pinfunction "G_1") (pintype "passive"))
      (node (ref "Q3") (pin "1") (pinfunction "G_1") (pintype "passive"))
      (node (ref "R11") (pin "2") (pinfunction "2_2") (pintype "passive"))
      (node (ref "R26") (pin "2") (pinfunction "2_2") (pintype "passive"))
      (node (ref "R39") (pin "2") (pinfunction "2_2") (pintype "passive"))
      (node (ref "R9") (pin "2") (pinfunction "2_2") (pintype "passive"))
      (node (ref "U2") (pin "P$20") (pinfunction "VDD-BATT_P$20") (pintype "bidirectional"))
      (node (ref "U2") (pin "P$21") (pinfunction "VDD-IN_P$21") (pintype "bidirectional"))
      (node (ref "U7") (pin "1") (pinfunction "VDD_1") (pintype "power_in"))
    )
    (net (code "2") (name "+5V{slash}1") (class "Default")
      (node (ref "C80") (pin "2") (pinfunction "2_2") (pintype "passive"))
      (node (ref "D35") (pin "C") (pinfunction "C_C") (pintype "passive"))
      (node (ref "L4") (pin "2") (pinfunction "2_2") (pintype "passive"))
      (node (ref "Q5") (pin "5") (pinfunction "D_5") (pintype "passive"))
      (node (ref "Q5") (pin "6") (pinfunction "D_6") (pintype "passive"))
      (node (ref "Q5") (pin "7") (pinfunction "D_7") (pintype "passive"))
      (node (ref "Q5") (pin "8") (pinfunction "D_8") (pintype "passive"))
      (node (ref "Q6") (pin "1") (pinfunction "S_1") (pintype "passive"))
      (node (ref "Q6") (pin "3") (pinfunction "S_3") (pintype "passive"))
      (node (ref "Q7") (pin "1") (pinfunction "S_1") (pintype "passive"))
      (node (ref "Q7") (pin "3") (pinfunction "S_3") (pintype "passive"))
      (node (ref "Q8") (pin "1") (pinfunction "S_1") (pintype "passive"))
      (node (ref "Q8") (pin "3") (pinfunction "S_3") (pintype "passive"))
      (node (ref "Q9") (pin "1") (pinfunction "S_1") (pintype "passive"))
      (node (ref "Q9") (pin "3") (pinfunction "S_3") (pintype "passive"))
    )
    (net (code "3") (name "+5V{slash}2") (class "Default")
      (node (ref "C3") (pin "1") (pinfunction "1_1") (pintype "passive"))
      (node (ref "C4") (pin "1") (pinfunction "1_1") (pintype "passive"))
      (node (ref "C72") (pin "1") (pinfunction "1_1") (pintype "passive"))
      (node (ref "C81") (pin "1") (pinfunction "1_1") (pintype "passive"))
      (node (ref "C94") (pin "1") (pinfunction "1_1") (pintype "passive"))
      (node (ref "D16") (pin "C") (pinfunction "C_C") (pintype "passive"))
      (node (ref "ICSP") (pin "2") (pinfunction "2_2") (pintype "passive"))
      (node (ref "ICSP1") (pin "2") (pinfunction "2_2") (pintype "passive"))
      (node (ref "L3") (pin "1") (pinfunction "1_1") (pintype "passive"))
      (node (ref "L4") (pin "1") (pinfunction "1_1") (pintype "passive"))
      (node (ref "Q4") (pin "1") (pinfunction "S_1") (pintype "passive"))
      (node (ref "R10") (pin "2") (pinfunction "2_2") (pintype "passive"))
      (node (ref "R17") (pin "2") (pinfunction "2_2") (pintype "passive"))
      (node (ref "R41") (pin "1") (pinfunction "1_1") (pintype "passive"))
      (node (ref "R6") (pin "2") (pinfunction "2_2") (pintype "passive"))
      (node (ref "R8") (pin "2") (pinfunction "2_2") (pintype "passive"))
      (node (ref "RX_USB") (pin "A") (pinfunction "A_A") (pintype "passive"))
      (node (ref "S1") (pin "2") (pinfunction "2_2") (pintype "passive"))
      (node (ref "TX_USB") (pin "A") (pinfunction "A_A") (pintype "passive"))
      (node (ref "U1") (pin "5") (pinfunction "VCC_5") (pintype "bidirectional"))
      (node (ref "U11") (pin "8") (pinfunction "V+_8") (pintype "power_in"))
      (node (ref "U12") (pin "18") (pinfunction "AVCC_18") (pintype "power_in"))
      (node (ref "U12") (pin "4") (pinfunction "VCC_4") (pintype "power_in"))
      (node (ref "U12") (pin "6") (pinfunction "VCC_6") (pintype "power_in"))
      (node (ref "U8") (pin "14") (pinfunction "VCC_14") (pintype "power_in"))
      (node (ref "U8") (pin "2") (pinfunction "UVCC_2") (pintype "power_in"))
      (node (ref "U8") (pin "34") (pinfunction "VCC1_34") (pintype "power_in"))
    )
    (net (code "4") (name "164-CLK") (class "Default")
      (node (ref "U10") (pin "8") (pinfunction "CLK_8") (pintype "input"))
      (node (ref "U8") (pin "28") (pinfunction "(ADC11/PCINT4)PB4_28") (pintype "bidirectional"))
    )
    (net (code "5") (name "164-IN") (class "Default")
      (node (ref "U10") (pin "1") (pinfunction "A_1") (pintype "input"))
      (node (ref "U10") (pin "2") (pinfunction "B_2") (pintype "input"))
      (node (ref "U8") (pin "29") (pinfunction "(PCINT5/OC1A/#OC4B/ADC12)PB5_29") (pintype "bidirectional"))
    )
    (net (code "6") (name "165-CLK") (class "Default")
      (node (ref "U8") (pin "31") (pinfunction "(OC3A/#0C4A)PC6_31") (pintype "bidirectional"))
      (node (ref "U9") (pin "2") (pinfunction "CLK_2") (pintype "input"))
    )
    (net (code "7") (name "165-LOAD") (class "Default")
      (node (ref "U8") (pin "30") (pinfunction "(PCINT6/OC1B/OC4B/ADC13)PB6_30") (pintype "bidirectional"))
      (node (ref "U9") (pin "1") (pinfunction "SH/~{LD}_1") (pintype "input"))
    )
    (net (code "8") (name "165-OUT") (class "Default")
      (node (ref "U8") (pin "32") (pinfunction "(ICP3/CLK0/OC4A)PC7_32") (pintype "bidirectional"))
      (node (ref "U9") (pin "7") (pinfunction "~{QH}_7") (pintype "output"))
    )
    (net (code "9") (name "A") (class "Default")
      (node (ref "D18") (pin "3") (pinfunction "C_3") (pintype "passive"))
      (node (ref "D19") (pin "3") (pinfunction "C_3") (pintype "passive"))
      (node (ref "D26") (pin "3") (pinfunction "C_3") (pintype "passive"))
      (node (ref "D27") (pin "3") (pinfunction "C_3") (pintype "passive"))
      (node (ref "R35") (pin "2") (pinfunction "2_2") (pintype "passive"))
      (node (ref "U9") (pin "3") (pinfunction "E_3") (pintype "input"))
    )
    (net (code "10") (name "A1") (class "Default")
      (node (ref "U8") (pin "37") (pinfunction "(ADC6/TDO)PF6_37") (pintype "bidirectional"))
    )
    (net (code "11") (name "A2") (class "Default")
      (node (ref "U8") (pin "38") (pinfunction "(ADC5/TMS)PF5_38") (pintype "bidirectional"))
    )
    (net (code "12") (name "A3") (class "Default")
      (node (ref "U8") (pin "39") (pinfunction "(ADC4/TCK)PF4_39") (pintype "bidirectional"))
    )
    (net (code "13") (name "AREFB") (class "Default")
      (node (ref "C73") (pin "1") (pinfunction "1_1") (pintype "passive"))
      (node (ref "U12") (pin "20") (pinfunction "AREF_20") (pintype "passive"))
    )
    (net (code "14") (name "AWAKE") (class "Default")
      (node (ref "U7") (pin "5") (pinfunction "I_5") (pintype "input"))
      (node (ref "U8") (pin "40") (pinfunction "(ADC1)PF1_40") (pintype "bidirectional"))
    )
    (net (code "15") (name "B") (class "Default")
      (node (ref "D20") (pin "3") (pinfunction "C_3") (pintype "passive"))
      (node (ref "D21") (pin "3") (pinfunction "C_3") (pintype "passive"))
      (node (ref "D28") (pin "3") (pinfunction "C_3") (pintype "passive"))
      (node (ref "D29") (pin "3") (pinfunction "C_3") (pintype "passive"))
      (node (ref "R36") (pin "2") (pinfunction "2_2") (pintype "passive"))
      (node (ref "U9") (pin "4") (pinfunction "F_4") (pintype "input"))
    )
    (net (code "16") (name "C") (class "Default")
      (node (ref "D22") (pin "3") (pinfunction "C_3") (pintype "passive"))
      (node (ref "D23") (pin "3") (pinfunction "C_3") (pintype "passive"))
      (node (ref "D30") (pin "3") (pinfunction "C_3") (pintype "passive"))
      (node (ref "D31") (pin "3") (pinfunction "C_3") (pintype "passive"))
      (node (ref "R37") (pin "2") (pinfunction "2_2") (pintype "passive"))
      (node (ref "U9") (pin "5") (pinfunction "G_5") (pintype "input"))
    )
    (net (code "17") (name "CHG") (class "Default")
      (node (ref "D42") (pin "A") (pinfunction "A_A") (pintype "passive"))
      (node (ref "R23") (pin "2") (pinfunction "2_2") (pintype "passive"))
      (node (ref "U12") (pin "26") (pinfunction "PC3(ADC3)_26") (pintype "bidirectional"))
    )
    (net (code "18") (name "D") (class "Default")
      (node (ref "D24") (pin "3") (pinfunction "C_3") (pintype "passive"))
      (node (ref "D25") (pin "3") (pinfunction "C_3") (pintype "passive"))
      (node (ref "D32") (pin "3") (pinfunction "C_3") (pintype "passive"))
      (node (ref "D33") (pin "3") (pinfunction "C_3") (pintype "passive"))
      (node (ref "R38") (pin "2") (pinfunction "2_2") (pintype "passive"))
      (node (ref "U9") (pin "6") (pinfunction "H_6") (pintype "input"))
    )
    (net (code "19") (name "D9") (class "Default")
      (node (ref "U12") (pin "13") (pinfunction "PB1(OC1A)_13") (pintype "bidirectional"))
    )
    (net (code "20") (name "D10") (class "Default")
      (node (ref "U12") (pin "14") (pinfunction "PB2(SS/OC1B)_14") (pintype "bidirectional"))
    )
    (net (code "21") (name "DO") (class "Default")
      (node (ref "B3") (pin "2A") (pinfunction "DI_2A") (pintype "bidirectional"))
      (node (ref "U8") (pin "27") (pinfunction "(T0/OC4D/ADC10)PD7_27") (pintype "bidirectional"))
    )
    (net (code "22") (name "DO1") (class "Default")
      (node (ref "B1") (pin "2A") (pinfunction "DI_2A") (pintype "bidirectional"))
      (node (ref "B3") (pin "1D") (pinfunction "DO_1D") (pintype "bidirectional"))
    )
    (net (code "23") (name "DO2") (class "Default")
      (node (ref "B1") (pin "1D") (pinfunction "DO_1D") (pintype "bidirectional"))
      (node (ref "B1") (pin "2H") (pinfunction "DI_2H") (pintype "bidirectional"))
    )
    (net (code "24") (name "DO3") (class "Default")
      (node (ref "B1") (pin "1E") (pinfunction "DO_1E") (pintype "bidirectional"))
      (node (ref "B3") (pin "2H") (pinfunction "DI_2H") (pintype "bidirectional"))
    )
    (net (code "25") (name "DO4") (class "Default")
      (node (ref "B3") (pin "1E") (pinfunction "DO_1E") (pintype "bidirectional"))
      (node (ref "B3") (pin "2I") (pinfunction "DI_2I") (pintype "bidirectional"))
    )
    (net (code "26") (name "DO5") (class "Default")
      (node (ref "B1") (pin "2I") (pinfunction "DI_2I") (pintype "bidirectional"))
      (node (ref "B3") (pin "1L") (pinfunction "DO_1L") (pintype "bidirectional"))
    )
    (net (code "27") (name "DO6") (class "Default")
      (node (ref "B1") (pin "1L") (pinfunction "DO_1L") (pintype "bidirectional"))
      (node (ref "B1") (pin "2P") (pinfunction "DI_2P") (pintype "bidirectional"))
    )
    (net (code "28") (name "DO7") (class "Default")
      (node (ref "B1") (pin "1M") (pinfunction "DO_1M") (pintype "bidirectional"))
      (node (ref "B3") (pin "2P") (pinfunction "DI_2P") (pintype "bidirectional"))
    )
    (net (code "29") (name "DO8") (class "Default")
      (node (ref "B3") (pin "1M") (pinfunction "DO_1M") (pintype "bidirectional"))
      (node (ref "B4") (pin "2A") (pinfunction "DI_2A") (pintype "bidirectional"))
    )
    (net (code "30") (name "DO9") (class "Default")
      (node (ref "B2") (pin "2A") (pinfunction "DI_2A") (pintype "bidirectional"))
      (node (ref "B4") (pin "1D") (pinfunction "DO_1D") (pintype "bidirectional"))
    )
    (net (code "31") (name "DO10") (class "Default")
      (node (ref "B2") (pin "1D") (pinfunction "DO_1D") (pintype "bidirectional"))
      (node (ref "B2") (pin "2H") (pinfunction "DI_2H") (pintype "bidirectional"))
    )
    (net (code "32") (name "DO11") (class "Default")
      (node (ref "B2") (pin "1E") (pinfunction "DO_1E") (pintype "bidirectional"))
      (node (ref "B4") (pin "2H") (pinfunction "DI_2H") (pintype "bidirectional"))
    )
    (net (code "33") (name "DO12") (class "Default")
      (node (ref "B4") (pin "1E") (pinfunction "DO_1E") (pintype "bidirectional"))
      (node (ref "B4") (pin "2I") (pinfunction "DI_2I") (pintype "bidirectional"))
    )
    (net (code "34") (name "DO13") (class "Default")
      (node (ref "B2") (pin "2I") (pinfunction "DI_2I") (pintype "bidirectional"))
      (node (ref "B4") (pin "1L") (pinfunction "DO_1L") (pintype "bidirectional"))
    )
    (net (code "35") (name "DO14") (class "Default")
      (node (ref "B2") (pin "1L") (pinfunction "DO_1L") (pintype "bidirectional"))
      (node (ref "B2") (pin "2P") (pinfunction "DI_2P") (pintype "bidirectional"))
    )
    (net (code "36") (name "DO15") (class "Default")
      (node (ref "B2") (pin "1M") (pinfunction "DO_1M") (pintype "bidirectional"))
      (node (ref "B4") (pin "2P") (pinfunction "DI_2P") (pintype "bidirectional"))
    )
    (net (code "37") (name "DO16") (class "Default")
      (node (ref "B4") (pin "1M") (pinfunction "DO_1M") (pintype "bidirectional"))
    )
    (net (code "38") (name "DTR") (class "Default")
      (node (ref "C93") (pin "2") (pinfunction "2_2") (pintype "passive"))
      (node (ref "U8") (pin "12") (pinfunction "(PCINT7/OC0A/OC1C/#RTS)PB7_12") (pintype "bidirectional"))
    )
    (net (code "39") (name "E") (class "Default")
      (node (ref "D1") (pin "3") (pinfunction "C_3") (pintype "passive"))
      (node (ref "D10") (pin "3") (pinfunction "C_3") (pintype "passive"))
      (node (ref "D2") (pin "3") (pinfunction "C_3") (pintype "passive"))
      (node (ref "D9") (pin "3") (pinfunction "C_3") (pintype "passive"))
      (node (ref "R31") (pin "2") (pinfunction "2_2") (pintype "passive"))
      (node (ref "U9") (pin "11") (pinfunction "A_11") (pintype "input"))
    )
    (net (code "40") (name "F") (class "Default")
      (node (ref "D11") (pin "3") (pinfunction "C_3") (pintype "passive"))
      (node (ref "D12") (pin "3") (pinfunction "C_3") (pintype "passive"))
      (node (ref "D3") (pin "3") (pinfunction "C_3") (pintype "passive"))
      (node (ref "D4") (pin "3") (pinfunction "C_3") (pintype "passive"))
      (node (ref "R32") (pin "2") (pinfunction "2_2") (pintype "passive"))
      (node (ref "U9") (pin "12") (pinfunction "B_12") (pintype "input"))
    )
    (net (code "41") (name "FACTORY") (class "Default")
      (node (ref "U7") (pin "9") (pinfunction "I_9") (pintype "input"))
      (node (ref "U8") (pin "41") (pinfunction "(ADC0)PF0_41") (pintype "bidirectional"))
    )
    (net (code "42") (name "G") (class "Default")
      (node (ref "D13") (pin "3") (pinfunction "C_3") (pintype "passive"))
      (node (ref "D14") (pin "3") (pinfunction "C_3") (pintype "passive"))
      (node (ref "D5") (pin "3") (pinfunction "C_3") (pintype "passive"))
      (node (ref "D6") (pin "3") (pinfunction "C_3") (pintype "passive"))
      (node (ref "R33") (pin "2") (pinfunction "2_2") (pintype "passive"))
      (node (ref "U9") (pin "13") (pinfunction "C_13") (pintype "input"))
    )
    (net (code "43") (name "G1") (class "Default")
      (node (ref "ICSP1") (pin "1") (pinfunction "1_1") (pintype "passive"))
      (node (ref "Q6") (pin "2") (pinfunction "G_2") (pintype "passive"))
      (node (ref "U12") (pin "16") (pinfunction "PB4(MISO)_16") (pintype "bidirectional"))
    )
    (net (code "44") (name "G2") (class "Default")
      (node (ref "ICSP1") (pin "4") (pinfunction "4_4") (pintype "passive"))
      (node (ref "Q6") (pin "4") (pinfunction "G_4") (pintype "passive"))
      (node (ref "U12") (pin "15") (pinfunction "PB3(MOSI/OC2)_15") (pintype "bidirectional"))
    )
    (net (code "45") (name "G3") (class "Default")
      (node (ref "Q7") (pin "2") (pinfunction "G_2") (pintype "passive"))
      (node (ref "U12") (pin "2") (pinfunction "PD4(XCK/T0)_2") (pintype "bidirectional"))
    )
    (net (code "46") (name "G4") (class "Default")
      (node (ref "Q7") (pin "4") (pinfunction "G_4") (pintype "passive"))
      (node (ref "U12") (pin "1") (pinfunction "PD3(INT1)_1") (pintype "bidirectional"))
    )
    (net (code "47") (name "G5") (class "Default")
      (node (ref "Q8") (pin "2") (pinfunction "G_2") (pintype "passive"))
      (node (ref "U12") (pin "12") (pinfunction "PB0(ICP)_12") (pintype "bidirectional"))
    )
    (net (code "48") (name "G6") (class "Default")
      (node (ref "Q8") (pin "4") (pinfunction "G_4") (pintype "passive"))
      (node (ref "U12") (pin "11") (pinfunction "PD7(AIN1)_11") (pintype "bidirectional"))
    )
    (net (code "49") (name "G7") (class "Default")
      (node (ref "Q9") (pin "2") (pinfunction "G_2") (pintype "passive"))
      (node (ref "U12") (pin "10") (pinfunction "PD6(AIN0)_10") (pintype "bidirectional"))
    )
    (net (code "50") (name "G8") (class "Default")
      (node (ref "Q9") (pin "4") (pinfunction "G_4") (pintype "passive"))
      (node (ref "U12") (pin "9") (pinfunction "PD5(T1)_9") (pintype "bidirectional"))
    )
    (net (code "51") (name "GATE_CMD") (class "Default")
      (node (ref "D36") (pin "A") (pinfunction "A_A") (pintype "passive"))
      (node (ref "D41") (pin "A") (pinfunction "A_A") (pintype "passive"))
      (node (ref "Q1") (pin "1") (pinfunction "G_1") (pintype "passive"))
      (node (ref "Q5") (pin "2") (pinfunction "G_2") (pintype "passive"))
      (node (ref "U11") (pin "7") (pinfunction "OUT_7") (pintype "output"))
      (node (ref "U12") (pin "24") (pinfunction "PC1(ADC1)_24") (pintype "bidirectional"))
    )
    (net (code "52") (name "GND") (class "Default")
      (node (ref "ASSOC.") (pin "C") (pinfunction "C_C") (pintype "passive"))
      (node (ref "C1") (pin "1") (pinfunction "1_1") (pintype "passive"))
      (node (ref "C2") (pin "1") (pinfunction "1_1") (pintype "passive"))
      (node (ref "C3") (pin "2") (pinfunction "2_2") (pintype "passive"))
      (node (ref "C4") (pin "2") (pinfunction "2_2") (pintype "passive"))
      (node (ref "C5") (pin "1") (pinfunction "1_1") (pintype "passive"))
      (node (ref "C6") (pin "1") (pinfunction "1_1") (pintype "passive"))
      (node (ref "C72") (pin "2") (pinfunction "2_2") (pintype "passive"))
      (node (ref "C73") (pin "2") (pinfunction "2_2") (pintype "passive"))
      (node (ref "C74") (pin "2") (pinfunction "2_2") (pintype "passive"))
      (node (ref "C75") (pin "2") (pinfunction "2_2") (pintype "passive"))
      (node (ref "C80") (pin "1") (pinfunction "1_1") (pintype "passive"))
      (node (ref "C81") (pin "2") (pinfunction "2_2") (pintype "passive"))
      (node (ref "C82") (pin "1") (pinfunction "1_1") (pintype "passive"))
      (node (ref "C89") (pin "1") (pinfunction "1_1") (pintype "passive"))
      (node (ref "C90") (pin "2") (pinfunction "2_2") (pintype "passive"))
      (node (ref "C91") (pin "2") (pinfunction "2_2") (pintype "passive"))
      (node (ref "C92") (pin "2") (pinfunction "2_2") (pintype "passive"))
      (node (ref "C94") (pin "2") (pinfunction "2_2") (pintype "passive"))
      (node (ref "C95") (pin "2") (pinfunction "2_2") (pintype "passive"))
      (node (ref "CONNEC.") (pin "C") (pinfunction "C_C") (pintype "passive"))
      (node (ref "D40") (pin "A") (pinfunction "A_A") (pintype "passive"))
      (node (ref "ICSP") (pin "6") (pinfunction "6_6") (pintype "passive"))
      (node (ref "ICSP1") (pin "6") (pinfunction "6_6") (pintype "passive"))
      (node (ref "L5") (pin "2") (pinfunction "2_2") (pintype "passive"))
      (node (ref "L6") (pin "2") (pinfunction "2_2") (pintype "passive"))
      (node (ref "R15") (pin "2") (pinfunction "2_2") (pintype "passive"))
      (node (ref "R21") (pin "1") (pinfunction "1_1") (pintype "passive"))
      (node (ref "R27") (pin "1") (pinfunction "1_1") (pintype "passive"))
      (node (ref "R31") (pin "1") (pinfunction "1_1") (pintype "passive"))
      (node (ref "R32") (pin "1") (pinfunction "1_1") (pintype "passive"))
      (node (ref "R33") (pin "1") (pinfunction "1_1") (pintype "passive"))
      (node (ref "R34") (pin "1") (pinfunction "1_1") (pintype "passive"))
      (node (ref "R35") (pin "1") (pinfunction "1_1") (pintype "passive"))
      (node (ref "R36") (pin "1") (pinfunction "1_1") (pintype "passive"))
      (node (ref "R37") (pin "1") (pinfunction "1_1") (pintype "passive"))
      (node (ref "R38") (pin "1") (pinfunction "1_1") (pintype "passive"))
      (node (ref "R42") (pin "2") (pinfunction "2_2") (pintype "passive"))
      (node (ref "R5") (pin "1") (pinfunction "1_1") (pintype "passive"))
      (node (ref "RST") (pin "1") (pinfunction "1_1") (pintype "passive"))
      (node (ref "U1") (pin "2") (pinfunction "GND_2") (pintype "bidirectional"))
      (node (ref "U10") (pin "7") (pinfunction "GND_7") (pintype "power_in"))
      (node (ref "U11") (pin "4") (pinfunction "V-_4") (pintype "power_in"))
      (node (ref "U12") (pin "21") (pinfunction "GND_21") (pintype "power_in"))
      (node (ref "U12") (pin "3") (pinfunction "GND_3") (pintype "power_in"))
      (node (ref "U12") (pin "5") (pinfunction "GND_5") (pintype "power_in"))
      (node (ref "U13") (pin "10") (pinfunction "GND3_10") (pintype "bidirectional"))
      (node (ref "U13") (pin "12") (pinfunction "SDO_12") (pintype "bidirectional"))
      (node (ref "U13") (pin "2") (pinfunction "GND_2") (pintype "bidirectional"))
      (node (ref "U13") (pin "4") (pinfunction "GND1_4") (pintype "bidirectional"))
      (node (ref "U13") (pin "5") (pinfunction "GND2_5") (pintype "bidirectional"))
      (node (ref "U2") (pin "P$18") (pinfunction "3.3V-RIN_P$18") (pintype "bidirectional"))
      (node (ref "U2") (pin "P$19") (pinfunction "GND_P$19") (pintype "bidirectional"))
      (node (ref "U2") (pin "P$36") (pinfunction "GND_P$36") (pintype "bidirectional"))
      (node (ref "U2") (pin "P$37") (pinfunction "GND_P$37") (pintype "bidirectional"))
      (node (ref "U2") (pin "P$38") (pinfunction "GND_P$38") (pintype "bidirectional"))
      (node (ref "U2") (pin "P$39") (pinfunction "GND_P$39") (pintype "bidirectional"))
      (node (ref "U2") (pin "P$40") (pinfunction "GND_P$40") (pintype "bidirectional"))
      (node (ref "U2") (pin "P$41") (pinfunction "GND_P$41") (pintype "bidirectional"))
      (node (ref "U2") (pin "P$42") (pinfunction "GND_P$42") (pintype "bidirectional"))
      (node (ref "U2") (pin "P$43") (pinfunction "GND_P$43") (pintype "bidirectional"))
      (node (ref "U2") (pin "P$44") (pinfunction "GND_P$44") (pintype "bidirectional"))
      (node (ref "U6") (pin "2") (pinfunction "GND_2") (pintype "bidirectional"))
      (node (ref "U7") (pin "8") (pinfunction "VSS_8") (pintype "power_in"))
      (node (ref "U8") (pin "15") (pinfunction "GND_15") (pintype "power_in"))
      (node (ref "U8") (pin "23") (pinfunction "GND1_23") (pintype "power_in"))
      (node (ref "U8") (pin "35") (pinfunction "GND2_35") (pintype "power_in"))
      (node (ref "U8") (pin "43") (pinfunction "GND3_43") (pintype "power_in"))
      (node (ref "U8") (pin "P$1") (pinfunction "PAD_P$1") (pintype "power_in"))
      (node (ref "U9") (pin "10") (pinfunction "SER_10") (pintype "input"))
      (node (ref "U9") (pin "15") (pinfunction "INH_15") (pintype "input"))
      (node (ref "U9") (pin "8") (pinfunction "GND_8") (pintype "power_in"))
      (node (ref "Y1") (pin "2") (pinfunction "2_2") (pintype "passive"))
      (node (ref "Y2") (pin "2") (pinfunction "2_2") (pintype "passive"))
      (node (ref "Z1") (pin "2") (pinfunction "2_2") (pintype "passive"))
      (node (ref "Z2") (pin "2") (pinfunction "2_2") (pintype "passive"))
    )
    (net (code "53") (name "GNDA") (class "Default")
      (node (ref "BAT") (pin "1") (pinfunction "1_1") (pintype "passive"))
      (node (ref "C7") (pin "1") (pinfunction "1_1") (pintype "passive"))
      (node (ref "C76") (pin "2") (pinfunction "2_2") (pintype "passive"))
      (node (ref "C77") (pin "2") (pinfunction "2_2") (pintype "passive"))
      (node (ref "C78") (pin "2") (pinfunction "2_2") (pintype "passive"))
      (node (ref "C79") (pin "2") (pinfunction "2_2") (pintype "passive"))
      (node (ref "C83") (pin "-") (pinfunction "-_-") (pintype "passive"))
      (node (ref "C84") (pin "-") (pinfunction "-_-") (pintype "passive"))
      (node (ref "C85") (pin "2") (pinfunction "2_2") (pintype "passive"))
      (node (ref "C86") (pin "2") (pinfunction "2_2") (pintype "passive"))
      (node (ref "C87") (pin "2") (pinfunction "2_2") (pintype "passive"))
      (node (ref "C88") (pin "2") (pinfunction "2_2") (pintype "passive"))
      (node (ref "L10") (pin "1") (pinfunction "1_1") (pintype "passive"))
      (node (ref "L11") (pin "1") (pinfunction "1_1") (pintype "passive"))
      (node (ref "L12") (pin "1") (pinfunction "1_1") (pintype "passive"))
      (node (ref "L13") (pin "1") (pinfunction "1_1") (pintype "passive"))
      (node (ref "L14") (pin "1") (pinfunction "1_1") (pintype "passive"))
      (node (ref "L5") (pin "1") (pinfunction "1_1") (pintype "passive"))
      (node (ref "L6") (pin "1") (pinfunction "1_1") (pintype "passive"))
      (node (ref "L7") (pin "1") (pinfunction "1_1") (pintype "passive"))
      (node (ref "L8") (pin "1") (pinfunction "1_1") (pintype "passive"))
      (node (ref "L9") (pin "1") (pinfunction "1_1") (pintype "passive"))
      (node (ref "Q1") (pin "2") (pinfunction "S_2") (pintype "passive"))
      (node (ref "R19") (pin "2") (pinfunction "2_2") (pintype "passive"))
      (node (ref "R22") (pin "2") (pinfunction "2_2") (pintype "passive"))
      (node (ref "R23") (pin "1") (pinfunction "1_1") (pintype "passive"))
      (node (ref "R25") (pin "1") (pinfunction "1_1") (pintype "passive"))
      (node (ref "R29") (pin "2") (pinfunction "2_2") (pintype "passive"))
      (node (ref "U3") (pin "11") (pinfunction "GND_11") (pintype "bidirectional"))
      (node (ref "U3") (pin "12") (pinfunction "GND_12") (pintype "bidirectional"))
      (node (ref "U3") (pin "13") (pinfunction "GND_13") (pintype "bidirectional"))
      (node (ref "U3") (pin "14") (pinfunction "GND_14") (pintype "bidirectional"))
      (node (ref "U3") (pin "15") (pinfunction "GND_15") (pintype "bidirectional"))
      (node (ref "U3") (pin "3") (pinfunction "PGND_3") (pintype "bidirectional"))
      (node (ref "U3") (pin "9") (pinfunction "GND_9") (pintype "bidirectional"))
      (node (ref "U4") (pin "2") (pinfunction "SYNC_2") (pintype "bidirectional"))
      (node (ref "U4") (pin "4") (pinfunction "GND_4") (pintype "bidirectional"))
      (node (ref "U4") (pin "8") (pinfunction "GND_8") (pintype "bidirectional"))
      (node (ref "U5") (pin "8") (pinfunction "VSS_8") (pintype "bidirectional"))
      (node (ref "U5") (pin "9") (pinfunction "VSS_9") (pintype "bidirectional"))
      (node (ref "U8") (pin "5") (pinfunction "UGND_5") (pintype "power_in"))
      (node (ref "X1") (pin "3") (pinfunction "3_3") (pintype "bidirectional"))
      (node (ref "X1") (pin "4") (pinfunction "4_4") (pintype "bidirectional"))
      (node (ref "X1") (pin "P$1") (pinfunction "P$1_P$1") (pintype "bidirectional"))
      (node (ref "X1") (pin "P$2") (pinfunction "P$1_P$2") (pintype "bidirectional"))
      (node (ref "X2") (pin "P$1") (pinfunction "SH7_P$1") (pintype "passive"))
      (node (ref "X2") (pin "P$2") (pinfunction "SH8_P$2") (pintype "passive"))
      (node (ref "X2") (pin "P$3") (pinfunction "SH9_P$3") (pintype "passive"))
      (node (ref "X2") (pin "P$4") (pinfunction "SH10_P$4") (pintype "passive"))
      (node (ref "X2") (pin "P$5") (pinfunction "SH11_P$5") (pintype "passive"))
      (node (ref "X2") (pin "P$6") (pinfunction "SH12_P$6") (pintype "passive"))
      (node (ref "X2") (pin "P$7") (pinfunction "SH13_P$7") (pintype "passive"))
      (node (ref "X2") (pin "P$8") (pinfunction "SH14_P$8") (pintype "passive"))
      (node (ref "X2") (pin "P5") (pinfunction "GND_P5") (pintype "passive"))
      (node (ref "X2") (pin "S1") (pinfunction "SH1_S1") (pintype "passive"))
      (node (ref "X2") (pin "S2") (pinfunction "SH2_S2") (pintype "passive"))
      (node (ref "X2") (pin "S3") (pinfunction "SH3_S3") (pintype "passive"))
      (node (ref "X2") (pin "S4") (pinfunction "SH4_S4") (pintype "passive"))
      (node (ref "X2") (pin "S5") (pinfunction "SH5_S5") (pintype "passive"))
      (node (ref "X2") (pin "S6") (pinfunction "SH6_S6") (pintype "passive"))
    )
    (net (code "54") (name "GPIO-4") (class "Default")
      (node (ref "R3") (pin "1") (pinfunction "1_1") (pintype "passive"))
      (node (ref "U2") (pin "P$29") (pinfunction "GPIO-4_P$29") (pintype "bidirectional"))
    )
    (net (code "55") (name "GPIO-6") (class "Default")
      (node (ref "R7") (pin "1") (pinfunction "1_1") (pintype "passive"))
      (node (ref "U2") (pin "P$27") (pinfunction "GPIO-6_P$27") (pintype "bidirectional"))
    )
    (net (code "56") (name "H") (class "Default")
      (node (ref "D15") (pin "3") (pinfunction "C_3") (pintype "passive"))
      (node (ref "D17") (pin "3") (pinfunction "C_3") (pintype "passive"))
      (node (ref "D7") (pin "3") (pinfunction "C_3") (pintype "passive"))
      (node (ref "D8") (pin "3") (pinfunction "C_3") (pintype "passive"))
      (node (ref "R34") (pin "2") (pinfunction "2_2") (pintype "passive"))
      (node (ref "U9") (pin "14") (pinfunction "D_14") (pintype "input"))
    )
    (net (code "57") (name "INT") (class "Default")
      (node (ref "C89") (pin "2") (pinfunction "2_2") (pintype "passive"))
      (node (ref "R20") (pin "2") (pinfunction "2_2") (pintype "passive"))
      (node (ref "U12") (pin "32") (pinfunction "PD2(INT0)_32") (pintype "bidirectional"))
      (node (ref "U8") (pin "1") (pinfunction "(INT6/AIN0)PE6_1") (pintype "bidirectional"))
    )
    (net (code "58") (name "MISOA") (class "Default")
      (node (ref "ICSP") (pin "1") (pinfunction "1_1") (pintype "passive"))
      (node (ref "U8") (pin "11") (pinfunction "(PD0/MISO/PCINT3)PB3_11") (pintype "bidirectional"))
    )
    (net (code "59") (name "MOSIA") (class "Default")
      (node (ref "ICSP") (pin "4") (pinfunction "4_4") (pintype "passive"))
      (node (ref "U8") (pin "10") (pinfunction "(PDI/MOSI/PCINT2)PB2_10") (pintype "bidirectional"))
    )
    (net (code "60") (name "Net-(ASSOC.-PadA)") (class "Default")
      (node (ref "ASSOC.") (pin "A") (pinfunction "A_A") (pintype "passive"))
      (node (ref "R7") (pin "2") (pinfunction "2_2") (pintype "passive"))
    )
    (net (code "61") (name "Net-(B1A-DO)") (class "Default")
      (node (ref "B1") (pin "1A") (pinfunction "DO_1A") (pintype "bidirectional"))
      (node (ref "B1") (pin "2B") (pinfunction "DI_2B") (pintype "bidirectional"))
    )
    (net (code "62") (name "Net-(B1A-SIG2)") (class "Default")
      (node (ref "B1") (pin "SIG2A") (pinfunction "SIG2_SIG2A") (pintype "bidirectional"))
      (node (ref "D1") (pin "1") (pinfunction "A1_1") (pintype "passive"))
    )
    (net (code "63") (name "Net-(B1A-VSS)") (class "Default")
      (node (ref "B1") (pin "6A") (pinfunction "VSS_6A") (pintype "bidirectional"))
      (node (ref "B1") (pin "6B") (pinfunction "VSS_6B") (pintype "bidirectional"))
      (node (ref "B1") (pin "6C") (pinfunction "VSS_6C") (pintype "bidirectional"))
      (node (ref "B1") (pin "6D") (pinfunction "VSS_6D") (pintype "bidirectional"))
      (node (ref "B1") (pin "6E") (pinfunction "VSS_6E") (pintype "bidirectional"))
      (node (ref "B1") (pin "6F") (pinfunction "VSS_6F") (pintype "bidirectional"))
      (node (ref "B1") (pin "6G") (pinfunction "VSS_6G") (pintype "bidirectional"))
      (node (ref "B1") (pin "6H") (pinfunction "VSS_6H") (pintype "bidirectional"))
      (node (ref "C12") (pin "2") (pinfunction "2_2") (pintype "passive"))
      (node (ref "C13") (pin "2") (pinfunction "2_2") (pintype "passive"))
      (node (ref "C16") (pin "2") (pinfunction "2_2") (pintype "passive"))
      (node (ref "C17") (pin "2") (pinfunction "2_2") (pintype "passive"))
      (node (ref "C20") (pin "2") (pinfunction "2_2") (pintype "passive"))
      (node (ref "C21") (pin "2") (pinfunction "2_2") (pintype "passive"))
      (node (ref "C8") (pin "2") (pinfunction "2_2") (pintype "passive"))
      (node (ref "C9") (pin "2") (pinfunction "2_2") (pintype "passive"))
      (node (ref "L7") (pin "2") (pinfunction "2_2") (pintype "passive"))
    )
    (net (code "64") (name "Net-(B1B-DI)") (class "Default")
      (node (ref "B1") (pin "1I") (pinfunction "DO_1I") (pintype "bidirectional"))
      (node (ref "B1") (pin "2J") (pinfunction "DI_2J") (pintype "bidirectional"))
    )
    (net (code "65") (name "Net-(B1B-DO)") (class "Default")
      (node (ref "B1") (pin "1J") (pinfunction "DO_1J") (pintype "bidirectional"))
      (node (ref "B1") (pin "2K") (pinfunction "DI_2K") (pintype "bidirectional"))
    )
    (net (code "66") (name "Net-(B1B-SIG2)") (class "Default")
      (node (ref "B1") (pin "SIG2J") (pinfunction "SIG2_SIG2J") (pintype "bidirectional"))
      (node (ref "D4") (pin "1") (pinfunction "A1_1") (pintype "passive"))
    )
    (net (code "67") (name "Net-(B1B-VSS)") (class "Default")
      (node (ref "B1") (pin "6I") (pinfunction "VSS_6I") (pintype "bidirectional"))
      (node (ref "B1") (pin "6J") (pinfunction "VSS_6J") (pintype "bidirectional"))
      (node (ref "B1") (pin "6K") (pinfunction "VSS_6K") (pintype "bidirectional"))
      (node (ref "B1") (pin "6L") (pinfunction "VSS_6L") (pintype "bidirectional"))
      (node (ref "B1") (pin "6M") (pinfunction "VSS_6M") (pintype "bidirectional"))
      (node (ref "B1") (pin "6N") (pinfunction "VSS_6N") (pintype "bidirectional"))
      (node (ref "B1") (pin "6O") (pinfunction "VSS_6O") (pintype "bidirectional"))
      (node (ref "B1") (pin "6P") (pinfunction "VSS_6P") (pintype "bidirectional"))
      (node (ref "C10") (pin "2") (pinfunction "2_2") (pintype "passive"))
      (node (ref "C11") (pin "2") (pinfunction "2_2") (pintype "passive"))
      (node (ref "C14") (pin "2") (pinfunction "2_2") (pintype "passive"))
      (node (ref "C15") (pin "2") (pinfunction "2_2") (pintype "passive"))
      (node (ref "C18") (pin "2") (pinfunction "2_2") (pintype "passive"))
      (node (ref "C19") (pin "2") (pinfunction "2_2") (pintype "passive"))
      (node (ref "C22") (pin "2") (pinfunction "2_2") (pintype "passive"))
      (node (ref "C23") (pin "2") (pinfunction "2_2") (pintype "passive"))
      (node (ref "L8") (pin "2") (pinfunction "2_2") (pintype "passive"))
    )
    (net (code "68") (name "Net-(B1C-DO)") (class "Default")
      (node (ref "B1") (pin "1K") (pinfunction "DO_1K") (pintype "bidirectional"))
      (node (ref "B1") (pin "2L") (pinfunction "DI_2L") (pintype "bidirectional"))
    )
    (net (code "69") (name "Net-(B1C-SIG2)") (class "Default")
      (node (ref "B1") (pin "SIG2K") (pinfunction "SIG2_SIG2K") (pintype "bidirectional"))
      (node (ref "D6") (pin "1") (pinfunction "A1_1") (pintype "passive"))
    )
    (net (code "70") (name "Net-(B1D-SIG2)") (class "Default")
      (node (ref "B1") (pin "SIG2L") (pinfunction "SIG2_SIG2L") (pintype "bidirectional"))
      (node (ref "D8") (pin "1") (pinfunction "A1_1") (pintype "passive"))
    )
    (net (code "71") (name "Net-(B1E-DI)") (class "Default")
      (node (ref "B1") (pin "1N") (pinfunction "DO_1N") (pintype "bidirectional"))
      (node (ref "B1") (pin "2M") (pinfunction "DI_2M") (pintype "bidirectional"))
    )
    (net (code "72") (name "Net-(B1E-SIG2)") (class "Default")
      (node (ref "B1") (pin "SIG2M") (pinfunction "SIG2_SIG2M") (pintype "bidirectional"))
      (node (ref "D2") (pin "2") (pinfunction "A2_2") (pintype "passive"))
    )
    (net (code "73") (name "Net-(B1F-DI)") (class "Default")
      (node (ref "B1") (pin "1O") (pinfunction "DO_1O") (pintype "bidirectional"))
      (node (ref "B1") (pin "2N") (pinfunction "DI_2N") (pintype "bidirectional"))
    )
    (net (code "74") (name "Net-(B1F-SIG2)") (class "Default")
      (node (ref "B1") (pin "SIG2N") (pinfunction "SIG2_SIG2N") (pintype "bidirectional"))
      (node (ref "D4") (pin "2") (pinfunction "A2_2") (pintype "passive"))
    )
    (net (code "75") (name "Net-(B1G-DI)") (class "Default")
      (node (ref "B1") (pin "1P") (pinfunction "DO_1P") (pintype "bidirectional"))
      (node (ref "B1") (pin "2O") (pinfunction "DI_2O") (pintype "bidirectional"))
    )
    (net (code "76") (name "Net-(B1G-SIG2)") (class "Default")
      (node (ref "B1") (pin "SIG2O") (pinfunction "SIG2_SIG2O") (pintype "bidirectional"))
      (node (ref "D6") (pin "2") (pinfunction "A2_2") (pintype "passive"))
    )
    (net (code "77") (name "Net-(B1H-SIG2)") (class "Default")
      (node (ref "B1") (pin "SIG2P") (pinfunction "SIG2_SIG2P") (pintype "bidirectional"))
      (node (ref "D8") (pin "2") (pinfunction "A2_2") (pintype "passive"))
    )
    (net (code "78") (name "Net-(B1I-DO)") (class "Default")
      (node (ref "B1") (pin "1B") (pinfunction "DO_1B") (pintype "bidirectional"))
      (node (ref "B1") (pin "2C") (pinfunction "DI_2C") (pintype "bidirectional"))
    )
    (net (code "79") (name "Net-(B1I-SIG2)") (class "Default")
      (node (ref "B1") (pin "SIG2B") (pinfunction "SIG2_SIG2B") (pintype "bidirectional"))
      (node (ref "D3") (pin "1") (pinfunction "A1_1") (pintype "passive"))
    )
    (net (code "80") (name "Net-(B1J-DO)") (class "Default")
      (node (ref "B1") (pin "1C") (pinfunction "DO_1C") (pintype "bidirectional"))
      (node (ref "B1") (pin "2D") (pinfunction "DI_2D") (pintype "bidirectional"))
    )
    (net (code "81") (name "Net-(B1J-SIG2)") (class "Default")
      (node (ref "B1") (pin "SIG2C") (pinfunction "SIG2_SIG2C") (pintype "bidirectional"))
      (node (ref "D5") (pin "1") (pinfunction "A1_1") (pintype "passive"))
    )
    (net (code "82") (name "Net-(B1K-SIG2)") (class "Default")
      (node (ref "B1") (pin "SIG2D") (pinfunction "SIG2_SIG2D") (pintype "bidirectional"))
      (node (ref "D7") (pin "1") (pinfunction "A1_1") (pintype "passive"))
    )
    (net (code "83") (name "Net-(B1L-DI)") (class "Default")
      (node (ref "B1") (pin "1F") (pinfunction "DO_1F") (pintype "bidirectional"))
      (node (ref "B1") (pin "2E") (pinfunction "DI_2E") (pintype "bidirectional"))
    )
    (net (code "84") (name "Net-(B1L-SIG2)") (class "Default")
      (node (ref "B1") (pin "SIG2E") (pinfunction "SIG2_SIG2E") (pintype "bidirectional"))
      (node (ref "D1") (pin "2") (pinfunction "A2_2") (pintype "passive"))
    )
    (net (code "85") (name "Net-(B1M-DI)") (class "Default")
      (node (ref "B1") (pin "1G") (pinfunction "DO_1G") (pintype "bidirectional"))
      (node (ref "B1") (pin "2F") (pinfunction "DI_2F") (pintype "bidirectional"))
    )
    (net (code "86") (name "Net-(B1M-SIG2)") (class "Default")
      (node (ref "B1") (pin "SIG2F") (pinfunction "SIG2_SIG2F") (pintype "bidirectional"))
      (node (ref "D3") (pin "2") (pinfunction "A2_2") (pintype "passive"))
    )
    (net (code "87") (name "Net-(B1N-DI)") (class "Default")
      (node (ref "B1") (pin "1H") (pinfunction "DO_1H") (pintype "bidirectional"))
      (node (ref "B1") (pin "2G") (pinfunction "DI_2G") (pintype "bidirectional"))
    )
    (net (code "88") (name "Net-(B1N-SIG2)") (class "Default")
      (node (ref "B1") (pin "SIG2G") (pinfunction "SIG2_SIG2G") (pintype "bidirectional"))
      (node (ref "D5") (pin "2") (pinfunction "A2_2") (pintype "passive"))
    )
    (net (code "89") (name "Net-(B1O-SIG2)") (class "Default")
      (node (ref "B1") (pin "SIG2H") (pinfunction "SIG2_SIG2H") (pintype "bidirectional"))
      (node (ref "D7") (pin "2") (pinfunction "A2_2") (pintype "passive"))
    )
    (net (code "90") (name "Net-(B1P-SIG2)") (class "Default")
      (node (ref "B1") (pin "SIG2I") (pinfunction "SIG2_SIG2I") (pintype "bidirectional"))
      (node (ref "D2") (pin "1") (pinfunction "A1_1") (pintype "passive"))
    )
    (net (code "91") (name "Net-(B2A-DO)") (class "Default")
      (node (ref "B2") (pin "1A") (pinfunction "DO_1A") (pintype "bidirectional"))
      (node (ref "B2") (pin "2B") (pinfunction "DI_2B") (pintype "bidirectional"))
    )
    (net (code "92") (name "Net-(B2A-SIG2)") (class "Default")
      (node (ref "B2") (pin "SIG2A") (pinfunction "SIG2_SIG2A") (pintype "bidirectional"))
      (node (ref "D9") (pin "1") (pinfunction "A1_1") (pintype "passive"))
    )
    (net (code "93") (name "Net-(B2A-VSS)") (class "Default")
      (node (ref "B2") (pin "6A") (pinfunction "VSS_6A") (pintype "bidirectional"))
      (node (ref "B2") (pin "6B") (pinfunction "VSS_6B") (pintype "bidirectional"))
      (node (ref "B2") (pin "6C") (pinfunction "VSS_6C") (pintype "bidirectional"))
      (node (ref "B2") (pin "6D") (pinfunction "VSS_6D") (pintype "bidirectional"))
      (node (ref "B2") (pin "6E") (pinfunction "VSS_6E") (pintype "bidirectional"))
      (node (ref "B2") (pin "6F") (pinfunction "VSS_6F") (pintype "bidirectional"))
      (node (ref "B2") (pin "6G") (pinfunction "VSS_6G") (pintype "bidirectional"))
      (node (ref "B2") (pin "6H") (pinfunction "VSS_6H") (pintype "bidirectional"))
      (node (ref "C24") (pin "2") (pinfunction "2_2") (pintype "passive"))
      (node (ref "C25") (pin "2") (pinfunction "2_2") (pintype "passive"))
      (node (ref "C28") (pin "2") (pinfunction "2_2") (pintype "passive"))
      (node (ref "C29") (pin "2") (pinfunction "2_2") (pintype "passive"))
      (node (ref "C32") (pin "2") (pinfunction "2_2") (pintype "passive"))
      (node (ref "C33") (pin "2") (pinfunction "2_2") (pintype "passive"))
      (node (ref "C36") (pin "2") (pinfunction "2_2") (pintype "passive"))
      (node (ref "C37") (pin "2") (pinfunction "2_2") (pintype "passive"))
      (node (ref "L9") (pin "2") (pinfunction "2_2") (pintype "passive"))
    )
    (net (code "94") (name "Net-(B2B-DI)") (class "Default")
      (node (ref "B2") (pin "1I") (pinfunction "DO_1I") (pintype "bidirectional"))
      (node (ref "B2") (pin "2J") (pinfunction "DI_2J") (pintype "bidirectional"))
    )
    (net (code "95") (name "Net-(B2B-DO)") (class "Default")
      (node (ref "B2") (pin "1J") (pinfunction "DO_1J") (pintype "bidirectional"))
      (node (ref "B2") (pin "2K") (pinfunction "DI_2K") (pintype "bidirectional"))
    )
    (net (code "96") (name "Net-(B2B-SIG2)") (class "Default")
      (node (ref "B2") (pin "SIG2J") (pinfunction "SIG2_SIG2J") (pintype "bidirectional"))
      (node (ref "D12") (pin "1") (pinfunction "A1_1") (pintype "passive"))
    )
    (net (code "97") (name "Net-(B2B-VSS)") (class "Default")
      (node (ref "B2") (pin "6I") (pinfunction "VSS_6I") (pintype "bidirectional"))
      (node (ref "B2") (pin "6J") (pinfunction "VSS_6J") (pintype "bidirectional"))
      (node (ref "B2") (pin "6K") (pinfunction "VSS_6K") (pintype "bidirectional"))
      (node (ref "B2") (pin "6L") (pinfunction "VSS_6L") (pintype "bidirectional"))
      (node (ref "B2") (pin "6M") (pinfunction "VSS_6M") (pintype "bidirectional"))
      (node (ref "B2") (pin "6N") (pinfunction "VSS_6N") (pintype "bidirectional"))
      (node (ref "B2") (pin "6O") (pinfunction "VSS_6O") (pintype "bidirectional"))
      (node (ref "B2") (pin "6P") (pinfunction "VSS_6P") (pintype "bidirectional"))
      (node (ref "C26") (pin "2") (pinfunction "2_2") (pintype "passive"))
      (node (ref "C27") (pin "2") (pinfunction "2_2") (pintype "passive"))
      (node (ref "C30") (pin "2") (pinfunction "2_2") (pintype "passive"))
      (node (ref "C31") (pin "2") (pinfunction "2_2") (pintype "passive"))
      (node (ref "C34") (pin "2") (pinfunction "2_2") (pintype "passive"))
      (node (ref "C35") (pin "2") (pinfunction "2_2") (pintype "passive"))
      (node (ref "C38") (pin "2") (pinfunction "2_2") (pintype "passive"))
      (node (ref "C39") (pin "2") (pinfunction "2_2") (pintype "passive"))
      (node (ref "L10") (pin "2") (pinfunction "2_2") (pintype "passive"))
    )
    (net (code "98") (name "Net-(B2C-DO)") (class "Default")
      (node (ref "B2") (pin "1K") (pinfunction "DO_1K") (pintype "bidirectional"))
      (node (ref "B2") (pin "2L") (pinfunction "DI_2L") (pintype "bidirectional"))
    )
    (net (code "99") (name "Net-(B2C-SIG2)") (class "Default")
      (node (ref "B2") (pin "SIG2K") (pinfunction "SIG2_SIG2K") (pintype "bidirectional"))
      (node (ref "D14") (pin "1") (pinfunction "A1_1") (pintype "passive"))
    )
    (net (code "100") (name "Net-(B2D-SIG2)") (class "Default")
      (node (ref "B2") (pin "SIG2L") (pinfunction "SIG2_SIG2L") (pintype "bidirectional"))
      (node (ref "D17") (pin "1") (pinfunction "A1_1") (pintype "passive"))
    )
    (net (code "101") (name "Net-(B2E-DI)") (class "Default")
      (node (ref "B2") (pin "1N") (pinfunction "DO_1N") (pintype "bidirectional"))
      (node (ref "B2") (pin "2M") (pinfunction "DI_2M") (pintype "bidirectional"))
    )
    (net (code "102") (name "Net-(B2E-SIG2)") (class "Default")
      (node (ref "B2") (pin "SIG2M") (pinfunction "SIG2_SIG2M") (pintype "bidirectional"))
      (node (ref "D10") (pin "2") (pinfunction "A2_2") (pintype "passive"))
    )
    (net (code "103") (name "Net-(B2F-DI)") (class "Default")
      (node (ref "B2") (pin "1O") (pinfunction "DO_1O") (pintype "bidirectional"))
      (node (ref "B2") (pin "2N") (pinfunction "DI_2N") (pintype "bidirectional"))
    )
    (net (code "104") (name "Net-(B2F-SIG2)") (class "Default")
      (node (ref "B2") (pin "SIG2N") (pinfunction "SIG2_SIG2N") (pintype "bidirectional"))
      (node (ref "D12") (pin "2") (pinfunction "A2_2") (pintype "passive"))
    )
    (net (code "105") (name "Net-(B2G-DI)") (class "Default")
      (node (ref "B2") (pin "1P") (pinfunction "DO_1P") (pintype "bidirectional"))
      (node (ref "B2") (pin "2O") (pinfunction "DI_2O") (pintype "bidirectional"))
    )
    (net (code "106") (name "Net-(B2G-SIG2)") (class "Default")
      (node (ref "B2") (pin "SIG2O") (pinfunction "SIG2_SIG2O") (pintype "bidirectional"))
      (node (ref "D14") (pin "2") (pinfunction "A2_2") (pintype "passive"))
    )
    (net (code "107") (name "Net-(B2H-SIG2)") (class "Default")
      (node (ref "B2") (pin "SIG2P") (pinfunction "SIG2_SIG2P") (pintype "bidirectional"))
      (node (ref "D17") (pin "2") (pinfunction "A2_2") (pintype "passive"))
    )
    (net (code "108") (name "Net-(B2I-DO)") (class "Default")
      (node (ref "B2") (pin "1B") (pinfunction "DO_1B") (pintype "bidirectional"))
      (node (ref "B2") (pin "2C") (pinfunction "DI_2C") (pintype "bidirectional"))
    )
    (net (code "109") (name "Net-(B2I-SIG2)") (class "Default")
      (node (ref "B2") (pin "SIG2B") (pinfunction "SIG2_SIG2B") (pintype "bidirectional"))
      (node (ref "D11") (pin "1") (pinfunction "A1_1") (pintype "passive"))
    )
    (net (code "110") (name "Net-(B2J-DO)") (class "Default")
      (node (ref "B2") (pin "1C") (pinfunction "DO_1C") (pintype "bidirectional"))
      (node (ref "B2") (pin "2D") (pinfunction "DI_2D") (pintype "bidirectional"))
    )
    (net (code "111") (name "Net-(B2J-SIG2)") (class "Default")
      (node (ref "B2") (pin "SIG2C") (pinfunction "SIG2_SIG2C") (pintype "bidirectional"))
      (node (ref "D13") (pin "1") (pinfunction "A1_1") (pintype "passive"))
    )
    (net (code "112") (name "Net-(B2K-SIG2)") (class "Default")
      (node (ref "B2") (pin "SIG2D") (pinfunction "SIG2_SIG2D") (pintype "bidirectional"))
      (node (ref "D15") (pin "1") (pinfunction "A1_1") (pintype "passive"))
    )
    (net (code "113") (name "Net-(B2L-DI)") (class "Default")
      (node (ref "B2") (pin "1F") (pinfunction "DO_1F") (pintype "bidirectional"))
      (node (ref "B2") (pin "2E") (pinfunction "DI_2E") (pintype "bidirectional"))
    )
    (net (code "114") (name "Net-(B2L-SIG2)") (class "Default")
      (node (ref "B2") (pin "SIG2E") (pinfunction "SIG2_SIG2E") (pintype "bidirectional"))
      (node (ref "D9") (pin "2") (pinfunction "A2_2") (pintype "passive"))
    )
    (net (code "115") (name "Net-(B2M-DI)") (class "Default")
      (node (ref "B2") (pin "1G") (pinfunction "DO_1G") (pintype "bidirectional"))
      (node (ref "B2") (pin "2F") (pinfunction "DI_2F") (pintype "bidirectional"))
    )
    (net (code "116") (name "Net-(B2M-SIG2)") (class "Default")
      (node (ref "B2") (pin "SIG2F") (pinfunction "SIG2_SIG2F") (pintype "bidirectional"))
      (node (ref "D11") (pin "2") (pinfunction "A2_2") (pintype "passive"))
    )
    (net (code "117") (name "Net-(B2N-DI)") (class "Default")
      (node (ref "B2") (pin "1H") (pinfunction "DO_1H") (pintype "bidirectional"))
      (node (ref "B2") (pin "2G") (pinfunction "DI_2G") (pintype "bidirectional"))
    )
    (net (code "118") (name "Net-(B2N-SIG2)") (class "Default")
      (node (ref "B2") (pin "SIG2G") (pinfunction "SIG2_SIG2G") (pintype "bidirectional"))
      (node (ref "D13") (pin "2") (pinfunction "A2_2") (pintype "passive"))
    )
    (net (code "119") (name "Net-(B2O-SIG2)") (class "Default")
      (node (ref "B2") (pin "SIG2H") (pinfunction "SIG2_SIG2H") (pintype "bidirectional"))
      (node (ref "D15") (pin "2") (pinfunction "A2_2") (pintype "passive"))
    )
    (net (code "120") (name "Net-(B2P-SIG2)") (class "Default")
      (node (ref "B2") (pin "SIG2I") (pinfunction "SIG2_SIG2I") (pintype "bidirectional"))
      (node (ref "D10") (pin "1") (pinfunction "A1_1") (pintype "passive"))
    )
    (net (code "121") (name "Net-(B3A-DO)") (class "Default")
      (node (ref "B3") (pin "1A") (pinfunction "DO_1A") (pintype "bidirectional"))
      (node (ref "B3") (pin "2B") (pinfunction "DI_2B") (pintype "bidirectional"))
    )
    (net (code "122") (name "Net-(B3A-SIG2)") (class "Default")
      (node (ref "B3") (pin "SIG2A") (pinfunction "SIG2_SIG2A") (pintype "bidirectional"))
      (node (ref "D18") (pin "1") (pinfunction "A1_1") (pintype "passive"))
    )
    (net (code "123") (name "Net-(B3A-VSS)") (class "Default")
      (node (ref "B3") (pin "6A") (pinfunction "VSS_6A") (pintype "bidirectional"))
      (node (ref "B3") (pin "6B") (pinfunction "VSS_6B") (pintype "bidirectional"))
      (node (ref "B3") (pin "6C") (pinfunction "VSS_6C") (pintype "bidirectional"))
      (node (ref "B3") (pin "6D") (pinfunction "VSS_6D") (pintype "bidirectional"))
      (node (ref "B3") (pin "6E") (pinfunction "VSS_6E") (pintype "bidirectional"))
      (node (ref "B3") (pin "6F") (pinfunction "VSS_6F") (pintype "bidirectional"))
      (node (ref "B3") (pin "6G") (pinfunction "VSS_6G") (pintype "bidirectional"))
      (node (ref "B3") (pin "6H") (pinfunction "VSS_6H") (pintype "bidirectional"))
      (node (ref "C40") (pin "2") (pinfunction "2_2") (pintype "passive"))
      (node (ref "C41") (pin "2") (pinfunction "2_2") (pintype "passive"))
      (node (ref "C44") (pin "2") (pinfunction "2_2") (pintype "passive"))
      (node (ref "C45") (pin "2") (pinfunction "2_2") (pintype "passive"))
      (node (ref "C48") (pin "2") (pinfunction "2_2") (pintype "passive"))
      (node (ref "C49") (pin "2") (pinfunction "2_2") (pintype "passive"))
      (node (ref "C52") (pin "2") (pinfunction "2_2") (pintype "passive"))
      (node (ref "C53") (pin "2") (pinfunction "2_2") (pintype "passive"))
      (node (ref "L11") (pin "2") (pinfunction "2_2") (pintype "passive"))
    )
    (net (code "124") (name "Net-(B3B-DI)") (class "Default")
      (node (ref "B3") (pin "1I") (pinfunction "DO_1I") (pintype "bidirectional"))
      (node (ref "B3") (pin "2J") (pinfunction "DI_2J") (pintype "bidirectional"))
    )
    (net (code "125") (name "Net-(B3B-DO)") (class "Default")
      (node (ref "B3") (pin "1J") (pinfunction "DO_1J") (pintype "bidirectional"))
      (node (ref "B3") (pin "2K") (pinfunction "DI_2K") (pintype "bidirectional"))
    )
    (net (code "126") (name "Net-(B3B-SIG2)") (class "Default")
      (node (ref "B3") (pin "SIG2J") (pinfunction "SIG2_SIG2J") (pintype "bidirectional"))
      (node (ref "D21") (pin "1") (pinfunction "A1_1") (pintype "passive"))
    )
    (net (code "127") (name "Net-(B3B-VSS)") (class "Default")
      (node (ref "B3") (pin "6I") (pinfunction "VSS_6I") (pintype "bidirectional"))
      (node (ref "B3") (pin "6J") (pinfunction "VSS_6J") (pintype "bidirectional"))
      (node (ref "B3") (pin "6K") (pinfunction "VSS_6K") (pintype "bidirectional"))
      (node (ref "B3") (pin "6L") (pinfunction "VSS_6L") (pintype "bidirectional"))
      (node (ref "B3") (pin "6M") (pinfunction "VSS_6M") (pintype "bidirectional"))
      (node (ref "B3") (pin "6N") (pinfunction "VSS_6N") (pintype "bidirectional"))
      (node (ref "B3") (pin "6O") (pinfunction "VSS_6O") (pintype "bidirectional"))
      (node (ref "B3") (pin "6P") (pinfunction "VSS_6P") (pintype "bidirectional"))
      (node (ref "C42") (pin "2") (pinfunction "2_2") (pintype "passive"))
      (node (ref "C43") (pin "2") (pinfunction "2_2") (pintype "passive"))
      (node (ref "C46") (pin "2") (pinfunction "2_2") (pintype "passive"))
      (node (ref "C47") (pin "2") (pinfunction "2_2") (pintype "passive"))
      (node (ref "C50") (pin "2") (pinfunction "2_2") (pintype "passive"))
      (node (ref "C51") (pin "2") (pinfunction "2_2") (pintype "passive"))
      (node (ref "C54") (pin "2") (pinfunction "2_2") (pintype "passive"))
      (node (ref "C55") (pin "2") (pinfunction "2_2") (pintype "passive"))
      (node (ref "L12") (pin "2") (pinfunction "2_2") (pintype "passive"))
    )
    (net (code "128") (name "Net-(B3C-DO)") (class "Default")
      (node (ref "B3") (pin "1K") (pinfunction "DO_1K") (pintype "bidirectional"))
      (node (ref "B3") (pin "2L") (pinfunction "DI_2L") (pintype "bidirectional"))
    )
    (net (code "129") (name "Net-(B3C-SIG2)") (class "Default")
      (node (ref "B3") (pin "SIG2K") (pinfunction "SIG2_SIG2K") (pintype "bidirectional"))
      (node (ref "D23") (pin "1") (pinfunction "A1_1") (pintype "passive"))
    )
    (net (code "130") (name "Net-(B3D-SIG2)") (class "Default")
      (node (ref "B3") (pin "SIG2L") (pinfunction "SIG2_SIG2L") (pintype "bidirectional"))
      (node (ref "D25") (pin "1") (pinfunction "A1_1") (pintype "passive"))
    )
    (net (code "131") (name "Net-(B3E-DI)") (class "Default")
      (node (ref "B3") (pin "1N") (pinfunction "DO_1N") (pintype "bidirectional"))
      (node (ref "B3") (pin "2M") (pinfunction "DI_2M") (pintype "bidirectional"))
    )
    (net (code "132") (name "Net-(B3E-SIG2)") (class "Default")
      (node (ref "B3") (pin "SIG2M") (pinfunction "SIG2_SIG2M") (pintype "bidirectional"))
      (node (ref "D19") (pin "2") (pinfunction "A2_2") (pintype "passive"))
    )
    (net (code "133") (name "Net-(B3F-DI)") (class "Default")
      (node (ref "B3") (pin "1O") (pinfunction "DO_1O") (pintype "bidirectional"))
      (node (ref "B3") (pin "2N") (pinfunction "DI_2N") (pintype "bidirectional"))
    )
    (net (code "134") (name "Net-(B3F-SIG2)") (class "Default")
      (node (ref "B3") (pin "SIG2N") (pinfunction "SIG2_SIG2N") (pintype "bidirectional"))
      (node (ref "D21") (pin "2") (pinfunction "A2_2") (pintype "passive"))
    )
    (net (code "135") (name "Net-(B3G-DI)") (class "Default")
      (node (ref "B3") (pin "1P") (pinfunction "DO_1P") (pintype "bidirectional"))
      (node (ref "B3") (pin "2O") (pinfunction "DI_2O") (pintype "bidirectional"))
    )
    (net (code "136") (name "Net-(B3G-SIG2)") (class "Default")
      (node (ref "B3") (pin "SIG2O") (pinfunction "SIG2_SIG2O") (pintype "bidirectional"))
      (node (ref "D23") (pin "2") (pinfunction "A2_2") (pintype "passive"))
    )
    (net (code "137") (name "Net-(B3H-SIG2)") (class "Default")
      (node (ref "B3") (pin "SIG2P") (pinfunction "SIG2_SIG2P") (pintype "bidirectional"))
      (node (ref "D25") (pin "2") (pinfunction "A2_2") (pintype "passive"))
    )
    (net (code "138") (name "Net-(B3I-DO)") (class "Default")
      (node (ref "B3") (pin "1B") (pinfunction "DO_1B") (pintype "bidirectional"))
      (node (ref "B3") (pin "2C") (pinfunction "DI_2C") (pintype "bidirectional"))
    )
    (net (code "139") (name "Net-(B3I-SIG2)") (class "Default")
      (node (ref "B3") (pin "SIG2B") (pinfunction "SIG2_SIG2B") (pintype "bidirectional"))
      (node (ref "D20") (pin "1") (pinfunction "A1_1") (pintype "passive"))
    )
    (net (code "140") (name "Net-(B3J-DO)") (class "Default")
      (node (ref "B3") (pin "1C") (pinfunction "DO_1C") (pintype "bidirectional"))
      (node (ref "B3") (pin "2D") (pinfunction "DI_2D") (pintype "bidirectional"))
    )
    (net (code "141") (name "Net-(B3J-SIG2)") (class "Default")
      (node (ref "B3") (pin "SIG2C") (pinfunction "SIG2_SIG2C") (pintype "bidirectional"))
      (node (ref "D22") (pin "1") (pinfunction "A1_1") (pintype "passive"))
    )
    (net (code "142") (name "Net-(B3K-SIG2)") (class "Default")
      (node (ref "B3") (pin "SIG2D") (pinfunction "SIG2_SIG2D") (pintype "bidirectional"))
      (node (ref "D24") (pin "1") (pinfunction "A1_1") (pintype "passive"))
    )
    (net (code "143") (name "Net-(B3L-DI)") (class "Default")
      (node (ref "B3") (pin "1F") (pinfunction "DO_1F") (pintype "bidirectional"))
      (node (ref "B3") (pin "2E") (pinfunction "DI_2E") (pintype "bidirectional"))
    )
    (net (code "144") (name "Net-(B3L-SIG2)") (class "Default")
      (node (ref "B3") (pin "SIG2E") (pinfunction "SIG2_SIG2E") (pintype "bidirectional"))
      (node (ref "D18") (pin "2") (pinfunction "A2_2") (pintype "passive"))
    )
    (net (code "145") (name "Net-(B3M-DI)") (class "Default")
      (node (ref "B3") (pin "1G") (pinfunction "DO_1G") (pintype "bidirectional"))
      (node (ref "B3") (pin "2F") (pinfunction "DI_2F") (pintype "bidirectional"))
    )
    (net (code "146") (name "Net-(B3M-SIG2)") (class "Default")
      (node (ref "B3") (pin "SIG2F") (pinfunction "SIG2_SIG2F") (pintype "bidirectional"))
      (node (ref "D20") (pin "2") (pinfunction "A2_2") (pintype "passive"))
    )
    (net (code "147") (name "Net-(B3N-DI)") (class "Default")
      (node (ref "B3") (pin "1H") (pinfunction "DO_1H") (pintype "bidirectional"))
      (node (ref "B3") (pin "2G") (pinfunction "DI_2G") (pintype "bidirectional"))
    )
    (net (code "148") (name "Net-(B3N-SIG2)") (class "Default")
      (node (ref "B3") (pin "SIG2G") (pinfunction "SIG2_SIG2G") (pintype "bidirectional"))
      (node (ref "D22") (pin "2") (pinfunction "A2_2") (pintype "passive"))
    )
    (net (code "149") (name "Net-(B3O-SIG2)") (class "Default")
      (node (ref "B3") (pin "SIG2H") (pinfunction "SIG2_SIG2H") (pintype "bidirectional"))
      (node (ref "D24") (pin "2") (pinfunction "A2_2") (pintype "passive"))
    )
    (net (code "150") (name "Net-(B3P-SIG2)") (class "Default")
      (node (ref "B3") (pin "SIG2I") (pinfunction "SIG2_SIG2I") (pintype "bidirectional"))
      (node (ref "D19") (pin "1") (pinfunction "A1_1") (pintype "passive"))
    )
    (net (code "151") (name "Net-(B4A-DO)") (class "Default")
      (node (ref "B4") (pin "1A") (pinfunction "DO_1A") (pintype "bidirectional"))
      (node (ref "B4") (pin "2B") (pinfunction "DI_2B") (pintype "bidirectional"))
    )
    (net (code "152") (name "Net-(B4A-SIG2)") (class "Default")
      (node (ref "B4") (pin "SIG2A") (pinfunction "SIG2_SIG2A") (pintype "bidirectional"))
      (node (ref "D26") (pin "1") (pinfunction "A1_1") (pintype "passive"))
    )
    (net (code "153") (name "Net-(B4A-VSS)") (class "Default")
      (node (ref "B4") (pin "6A") (pinfunction "VSS_6A") (pintype "bidirectional"))
      (node (ref "B4") (pin "6B") (pinfunction "VSS_6B") (pintype "bidirectional"))
      (node (ref "B4") (pin "6C") (pinfunction "VSS_6C") (pintype "bidirectional"))
      (node (ref "B4") (pin "6D") (pinfunction "VSS_6D") (pintype "bidirectional"))
      (node (ref "B4") (pin "6E") (pinfunction "VSS_6E") (pintype "bidirectional"))
      (node (ref "B4") (pin "6F") (pinfunction "VSS_6F") (pintype "bidirectional"))
      (node (ref "B4") (pin "6G") (pinfunction "VSS_6G") (pintype "bidirectional"))
      (node (ref "B4") (pin "6H") (pinfunction "VSS_6H") (pintype "bidirectional"))
      (node (ref "C56") (pin "2") (pinfunction "2_2") (pintype "passive"))
      (node (ref "C57") (pin "2") (pinfunction "2_2") (pintype "passive"))
      (node (ref "C60") (pin "2") (pinfunction "2_2") (pintype "passive"))
      (node (ref "C61") (pin "2") (pinfunction "2_2") (pintype "passive"))
      (node (ref "C64") (pin "2") (pinfunction "2_2") (pintype "passive"))
      (node (ref "C65") (pin "2") (pinfunction "2_2") (pintype "passive"))
      (node (ref "C68") (pin "2") (pinfunction "2_2") (pintype "passive"))
      (node (ref "C69") (pin "2") (pinfunction "2_2") (pintype "passive"))
      (node (ref "L13") (pin "2") (pinfunction "2_2") (pintype "passive"))
    )
    (net (code "154") (name "Net-(B4B-DI)") (class "Default")
      (node (ref "B4") (pin "1I") (pinfunction "DO_1I") (pintype "bidirectional"))
      (node (ref "B4") (pin "2J") (pinfunction "DI_2J") (pintype "bidirectional"))
    )
    (net (code "155") (name "Net-(B4B-DO)") (class "Default")
      (node (ref "B4") (pin "1J") (pinfunction "DO_1J") (pintype "bidirectional"))
      (node (ref "B4") (pin "2K") (pinfunction "DI_2K") (pintype "bidirectional"))
    )
    (net (code "156") (name "Net-(B4B-SIG2)") (class "Default")
      (node (ref "B4") (pin "SIG2J") (pinfunction "SIG2_SIG2J") (pintype "bidirectional"))
      (node (ref "D29") (pin "1") (pinfunction "A1_1") (pintype "passive"))
    )
    (net (code "157") (name "Net-(B4B-VSS)") (class "Default")
      (node (ref "B4") (pin "6I") (pinfunction "VSS_6I") (pintype "bidirectional"))
      (node (ref "B4") (pin "6J") (pinfunction "VSS_6J") (pintype "bidirectional"))
      (node (ref "B4") (pin "6K") (pinfunction "VSS_6K") (pintype "bidirectional"))
      (node (ref "B4") (pin "6L") (pinfunction "VSS_6L") (pintype "bidirectional"))
      (node (ref "B4") (pin "6M") (pinfunction "VSS_6M") (pintype "bidirectional"))
      (node (ref "B4") (pin "6N") (pinfunction "VSS_6N") (pintype "bidirectional"))
      (node (ref "B4") (pin "6O") (pinfunction "VSS_6O") (pintype "bidirectional"))
      (node (ref "B4") (pin "6P") (pinfunction "VSS_6P") (pintype "bidirectional"))
      (node (ref "C58") (pin "2") (pinfunction "2_2") (pintype "passive"))
      (node (ref "C59") (pin "2") (pinfunction "2_2") (pintype "passive"))
      (node (ref "C62") (pin "2") (pinfunction "2_2") (pintype "passive"))
      (node (ref "C63") (pin "2") (pinfunction "2_2") (pintype "passive"))
      (node (ref "C66") (pin "2") (pinfunction "2_2") (pintype "passive"))
      (node (ref "C67") (pin "2") (pinfunction "2_2") (pintype "passive"))
      (node (ref "C70") (pin "2") (pinfunction "2_2") (pintype "passive"))
      (node (ref "C71") (pin "2") (pinfunction "2_2") (pintype "passive"))
      (node (ref "L14") (pin "2") (pinfunction "2_2") (pintype "passive"))
    )
    (net (code "158") (name "Net-(B4C-DO)") (class "Default")
      (node (ref "B4") (pin "1K") (pinfunction "DO_1K") (pintype "bidirectional"))
      (node (ref "B4") (pin "2L") (pinfunction "DI_2L") (pintype "bidirectional"))
    )
    (net (code "159") (name "Net-(B4C-SIG2)") (class "Default")
      (node (ref "B4") (pin "SIG2K") (pinfunction "SIG2_SIG2K") (pintype "bidirectional"))
      (node (ref "D31") (pin "1") (pinfunction "A1_1") (pintype "passive"))
    )
    (net (code "160") (name "Net-(B4D-SIG2)") (class "Default")
      (node (ref "B4") (pin "SIG2L") (pinfunction "SIG2_SIG2L") (pintype "bidirectional"))
      (node (ref "D33") (pin "1") (pinfunction "A1_1") (pintype "passive"))
    )
    (net (code "161") (name "Net-(B4E-DI)") (class "Default")
      (node (ref "B4") (pin "1N") (pinfunction "DO_1N") (pintype "bidirectional"))
      (node (ref "B4") (pin "2M") (pinfunction "DI_2M") (pintype "bidirectional"))
    )
    (net (code "162") (name "Net-(B4E-SIG2)") (class "Default")
      (node (ref "B4") (pin "SIG2M") (pinfunction "SIG2_SIG2M") (pintype "bidirectional"))
      (node (ref "D27") (pin "2") (pinfunction "A2_2") (pintype "passive"))
    )
    (net (code "163") (name "Net-(B4F-DI)") (class "Default")
      (node (ref "B4") (pin "1O") (pinfunction "DO_1O") (pintype "bidirectional"))
      (node (ref "B4") (pin "2N") (pinfunction "DI_2N") (pintype "bidirectional"))
    )
    (net (code "164") (name "Net-(B4F-SIG2)") (class "Default")
      (node (ref "B4") (pin "SIG2N") (pinfunction "SIG2_SIG2N") (pintype "bidirectional"))
      (node (ref "D29") (pin "2") (pinfunction "A2_2") (pintype "passive"))
    )
    (net (code "165") (name "Net-(B4G-DI)") (class "Default")
      (node (ref "B4") (pin "1P") (pinfunction "DO_1P") (pintype "bidirectional"))
      (node (ref "B4") (pin "2O") (pinfunction "DI_2O") (pintype "bidirectional"))
    )
    (net (code "166") (name "Net-(B4G-SIG2)") (class "Default")
      (node (ref "B4") (pin "SIG2O") (pinfunction "SIG2_SIG2O") (pintype "bidirectional"))
      (node (ref "D31") (pin "2") (pinfunction "A2_2") (pintype "passive"))
    )
    (net (code "167") (name "Net-(B4H-SIG2)") (class "Default")
      (node (ref "B4") (pin "SIG2P") (pinfunction "SIG2_SIG2P") (pintype "bidirectional"))
      (node (ref "D33") (pin "2") (pinfunction "A2_2") (pintype "passive"))
    )
    (net (code "168") (name "Net-(B4I-DO)") (class "Default")
      (node (ref "B4") (pin "1B") (pinfunction "DO_1B") (pintype "bidirectional"))
      (node (ref "B4") (pin "2C") (pinfunction "DI_2C") (pintype "bidirectional"))
    )
    (net (code "169") (name "Net-(B4I-SIG2)") (class "Default")
      (node (ref "B4") (pin "SIG2B") (pinfunction "SIG2_SIG2B") (pintype "bidirectional"))
      (node (ref "D28") (pin "1") (pinfunction "A1_1") (pintype "passive"))
    )
    (net (code "170") (name "Net-(B4J-DO)") (class "Default")
      (node (ref "B4") (pin "1C") (pinfunction "DO_1C") (pintype "bidirectional"))
      (node (ref "B4") (pin "2D") (pinfunction "DI_2D") (pintype "bidirectional"))
    )
    (net (code "171") (name "Net-(B4J-SIG2)") (class "Default")
      (node (ref "B4") (pin "SIG2C") (pinfunction "SIG2_SIG2C") (pintype "bidirectional"))
      (node (ref "D30") (pin "1") (pinfunction "A1_1") (pintype "passive"))
    )
    (net (code "172") (name "Net-(B4K-SIG2)") (class "Default")
      (node (ref "B4") (pin "SIG2D") (pinfunction "SIG2_SIG2D") (pintype "bidirectional"))
      (node (ref "D32") (pin "1") (pinfunction "A1_1") (pintype "passive"))
    )
    (net (code "173") (name "Net-(B4L-DI)") (class "Default")
      (node (ref "B4") (pin "1F") (pinfunction "DO_1F") (pintype "bidirectional"))
      (node (ref "B4") (pin "2E") (pinfunction "DI_2E") (pintype "bidirectional"))
    )
    (net (code "174") (name "Net-(B4L-SIG2)") (class "Default")
      (node (ref "B4") (pin "SIG2E") (pinfunction "SIG2_SIG2E") (pintype "bidirectional"))
      (node (ref "D26") (pin "2") (pinfunction "A2_2") (pintype "passive"))
    )
    (net (code "175") (name "Net-(B4M-DI)") (class "Default")
      (node (ref "B4") (pin "1G") (pinfunction "DO_1G") (pintype "bidirectional"))
      (node (ref "B4") (pin "2F") (pinfunction "DI_2F") (pintype "bidirectional"))
    )
    (net (code "176") (name "Net-(B4M-SIG2)") (class "Default")
      (node (ref "B4") (pin "SIG2F") (pinfunction "SIG2_SIG2F") (pintype "bidirectional"))
      (node (ref "D28") (pin "2") (pinfunction "A2_2") (pintype "passive"))
    )
    (net (code "177") (name "Net-(B4N-DI)") (class "Default")
      (node (ref "B4") (pin "1H") (pinfunction "DO_1H") (pintype "bidirectional"))
      (node (ref "B4") (pin "2G") (pinfunction "DI_2G") (pintype "bidirectional"))
    )
    (net (code "178") (name "Net-(B4N-SIG2)") (class "Default")
      (node (ref "B4") (pin "SIG2G") (pinfunction "SIG2_SIG2G") (pintype "bidirectional"))
      (node (ref "D30") (pin "2") (pinfunction "A2_2") (pintype "passive"))
    )
    (net (code "179") (name "Net-(B4O-SIG2)") (class "Default")
      (node (ref "B4") (pin "SIG2H") (pinfunction "SIG2_SIG2H") (pintype "bidirectional"))
      (node (ref "D32") (pin "2") (pinfunction "A2_2") (pintype "passive"))
    )
    (net (code "180") (name "Net-(B4P-SIG2)") (class "Default")
      (node (ref "B4") (pin "SIG2I") (pinfunction "SIG2_SIG2I") (pintype "bidirectional"))
      (node (ref "D27") (pin "1") (pinfunction "A1_1") (pintype "passive"))
    )
    (net (code "181") (name "Net-(C76-Pad1)") (class "Default")
      (node (ref "C76") (pin "1") (pinfunction "1_1") (pintype "passive"))
      (node (ref "D39") (pin "C") (pinfunction "C_C") (pintype "passive"))
      (node (ref "LOW_BAT") (pin "A") (pinfunction "A_A") (pintype "passive"))
      (node (ref "Q4") (pin "5") (pinfunction "D_5") (pintype "passive"))
      (node (ref "Q4") (pin "6") (pinfunction "D_6") (pintype "passive"))
      (node (ref "U5") (pin "1") (pinfunction "VDD_1") (pintype "bidirectional"))
      (node (ref "U5") (pin "2") (pinfunction "VDD_2") (pintype "bidirectional"))
    )
    (net (code "182") (name "Net-(CONNEC.-PadA)") (class "Default")
      (node (ref "CONNEC.") (pin "A") (pinfunction "A_A") (pintype "passive"))
      (node (ref "R3") (pin "2") (pinfunction "2_2") (pintype "passive"))
    )
    (net (code "183") (name "Net-(D34-PadA)") (class "Default")
      (node (ref "D34") (pin "A") (pinfunction "A_A") (pintype "passive"))
      (node (ref "X1") (pin "1") (pinfunction "1_1") (pintype "bidirectional"))
      (node (ref "X1") (pin "2") (pinfunction "2_2") (pintype "bidirectional"))
    )
    (net (code "184") (name "Net-(L1-1)") (class "Default")
      (node (ref "L1") (pin "P$1") (pinfunction "1_P$1") (pintype "bidirectional"))
      (node (ref "U3") (pin "4") (pinfunction "L1_4") (pintype "bidirectional"))
    )
    (net (code "185") (name "Net-(L1-2)") (class "Default")
      (node (ref "L1") (pin "P$2") (pinfunction "2_P$2") (pintype "bidirectional"))
      (node (ref "U3") (pin "2") (pinfunction "L2_2") (pintype "bidirectional"))
    )
    (net (code "186") (name "Net-(L16-Pad1)") (class "Default")
      (node (ref "L16") (pin "1") (pinfunction "1_1") (pintype "passive"))
      (node (ref "R16") (pin "1") (pinfunction "1_1") (pintype "passive"))
    )
    (net (code "187") (name "Net-(LOW_BAT-PadC)") (class "Default")
      (node (ref "LOW_BAT") (pin "C") (pinfunction "C_C") (pintype "passive"))
      (node (ref "R24") (pin "2") (pinfunction "2_2") (pintype "passive"))
    )
    (net (code "188") (name "Net-(Q1-D)") (class "Default")
      (node (ref "Q1") (pin "3") (pinfunction "D_3") (pintype "passive"))
      (node (ref "R14") (pin "1") (pinfunction "1_1") (pintype "passive"))
      (node (ref "R25") (pin "2") (pinfunction "2_2") (pintype "passive"))
    )
    (net (code "189") (name "Net-(Q2-S)") (class "Default")
      (node (ref "Q2") (pin "2") (pinfunction "S_2") (pintype "passive"))
      (node (ref "R11") (pin "1") (pinfunction "1_1") (pintype "passive"))
      (node (ref "U13") (pin "13") (pinfunction "SDA_13") (pintype "bidirectional"))
    )
    (net (code "190") (name "Net-(Q3-S)") (class "Default")
      (node (ref "Q3") (pin "2") (pinfunction "S_2") (pintype "passive"))
      (node (ref "R39") (pin "1") (pinfunction "1_1") (pintype "passive"))
      (node (ref "U13") (pin "14") (pinfunction "SCL_14") (pintype "bidirectional"))
    )
    (net (code "191") (name "Net-(Q4B-G)") (class "Default")
      (node (ref "D41") (pin "C") (pinfunction "C_C") (pintype "passive"))
      (node (ref "D42") (pin "C") (pinfunction "C_C") (pintype "passive"))
      (node (ref "Q4") (pin "4") (pinfunction "G_4") (pintype "passive"))
      (node (ref "R22") (pin "1") (pinfunction "1_1") (pintype "passive"))
    )
    (net (code "192") (name "Net-(Q5A-S)") (class "Default")
      (node (ref "D38") (pin "C") (pinfunction "C_C") (pintype "passive"))
      (node (ref "Q5") (pin "1") (pinfunction "S_1") (pintype "passive"))
    )
    (net (code "193") (name "Net-(Q5B-G)") (class "Default")
      (node (ref "D36") (pin "C") (pinfunction "C_C") (pintype "passive"))
      (node (ref "D37") (pin "C") (pinfunction "C_C") (pintype "passive"))
      (node (ref "Q5") (pin "4") (pinfunction "G_4") (pintype "passive"))
      (node (ref "R29") (pin "1") (pinfunction "1_1") (pintype "passive"))
    )
    (net (code "194") (name "Net-(R12-Pad2)") (class "Default")
      (node (ref "R12") (pin "2") (pinfunction "2_2") (pintype "passive"))
      (node (ref "TX_USB") (pin "C") (pinfunction "C_C") (pintype "passive"))
    )
    (net (code "195") (name "Net-(R13-Pad2)") (class "Default")
      (node (ref "R13") (pin "2") (pinfunction "2_2") (pintype "passive"))
      (node (ref "RX_USB") (pin "C") (pinfunction "C_C") (pintype "passive"))
    )
    (net (code "196") (name "Net-(R20-Pad1)") (class "Default")
      (node (ref "R20") (pin "1") (pinfunction "1_1") (pintype "passive"))
      (node (ref "R21") (pin "2") (pinfunction "2_2") (pintype "passive"))
      (node (ref "S1") (pin "1") (pinfunction "1_1") (pintype "passive"))
    )
    (net (code "197") (name "Net-(U2-F_AWAKE)") (class "Default")
      (node (ref "U2") (pin "P$9") (pinfunction "F_AWAKE_P$9") (pintype "bidirectional"))
      (node (ref "U7") (pin "4") (pinfunction "O_4") (pintype "output"))
    )
    (net (code "198") (name "Net-(U2-GPIO-9)") (class "Default")
      (node (ref "R9") (pin "1") (pinfunction "1_1") (pintype "passive"))
      (node (ref "U2") (pin "P$24") (pinfunction "GPIO-9_P$24") (pintype "bidirectional"))
      (node (ref "U7") (pin "10") (pinfunction "O_10") (pintype "output"))
    )
    (net (code "199") (name "Net-(U2-RESET)") (class "Default")
      (node (ref "U2") (pin "P$5") (pinfunction "RESET_P$5") (pintype "bidirectional"))
      (node (ref "U7") (pin "6") (pinfunction "O_6") (pintype "output"))
    )
    (net (code "200") (name "Net-(U2-RX)") (class "Default")
      (node (ref "U2") (pin "P$12") (pinfunction "RX_P$12") (pintype "bidirectional"))
      (node (ref "U7") (pin "2") (pinfunction "O_2") (pintype "output"))
    )
    (net (code "201") (name "Net-(U3-FB)") (class "Default")
      (node (ref "C79") (pin "1") (pinfunction "1_1") (pintype "passive"))
      (node (ref "D37") (pin "A") (pinfunction "A_A") (pintype "passive"))
      (node (ref "D38") (pin "A") (pinfunction "A_A") (pintype "passive"))
      (node (ref "U3") (pin "1") (pinfunction "VOUT_1") (pintype "bidirectional"))
      (node (ref "U3") (pin "10") (pinfunction "FB_10") (pintype "bidirectional"))
    )
    (net (code "202") (name "Net-(U4-FB)") (class "Default")
      (node (ref "R18") (pin "1") (pinfunction "1_1") (pintype "passive"))
      (node (ref "R19") (pin "1") (pinfunction "1_1") (pintype "passive"))
      (node (ref "U4") (pin "5") (pinfunction "FB_5") (pintype "bidirectional"))
    )
    (net (code "203") (name "Net-(U4-SS{slash}TRK)") (class "Default")
      (node (ref "C88") (pin "1") (pinfunction "1_1") (pintype "passive"))
      (node (ref "U4") (pin "6") (pinfunction "SS/TRK_6") (pintype "bidirectional"))
    )
    (net (code "204") (name "Net-(U4-VOUT)") (class "Default")
      (node (ref "C83") (pin "+") (pinfunction "+_+") (pintype "passive"))
      (node (ref "C84") (pin "+") (pinfunction "+_+") (pintype "passive"))
      (node (ref "C85") (pin "1") (pinfunction "1_1") (pintype "passive"))
      (node (ref "D35") (pin "A") (pinfunction "A_A") (pintype "passive"))
      (node (ref "D39") (pin "A") (pinfunction "A_A") (pintype "passive"))
      (node (ref "R18") (pin "2") (pinfunction "2_2") (pintype "passive"))
      (node (ref "U4") (pin "7") (pinfunction "VOUT_7") (pintype "bidirectional"))
    )
    (net (code "205") (name "Net-(U5-PROG)") (class "Default")
      (node (ref "R14") (pin "2") (pinfunction "2_2") (pintype "passive"))
      (node (ref "U5") (pin "10") (pinfunction "PROG_10") (pintype "bidirectional"))
    )
    (net (code "206") (name "Net-(U5-STAT)") (class "Default")
      (node (ref "R24") (pin "1") (pinfunction "1_1") (pintype "passive"))
      (node (ref "U5") (pin "7") (pinfunction "STAT_7") (pintype "bidirectional"))
    )
    (net (code "207") (name "Net-(U6-EN)") (class "Default")
      (node (ref "R28") (pin "1") (pinfunction "1_1") (pintype "passive"))
      (node (ref "U6") (pin "4") (pinfunction "EN_4") (pintype "bidirectional"))
    )
    (net (code "208") (name "Net-(U6-FB)") (class "Default")
      (node (ref "R26") (pin "1") (pinfunction "1_1") (pintype "passive"))
      (node (ref "R27") (pin "2") (pinfunction "2_2") (pintype "passive"))
      (node (ref "U6") (pin "3") (pinfunction "FB_3") (pintype "bidirectional"))
    )
    (net (code "209") (name "Net-(U6-SW)") (class "Default")
      (node (ref "D40") (pin "C") (pinfunction "C_C") (pintype "passive"))
      (node (ref "L2") (pin "1") (pinfunction "1_1") (pintype "passive"))
      (node (ref "U6") (pin "1") (pinfunction "SW_1") (pintype "bidirectional"))
    )
    (net (code "210") (name "Net-(U8-(#HWB)PE2)") (class "Default")
      (node (ref "R5") (pin "2") (pinfunction "2_2") (pintype "passive"))
      (node (ref "U8") (pin "33") (pinfunction "(#HWB)PE2_33") (pintype "bidirectional"))
    )
    (net (code "211") (name "Net-(U8-AREF)") (class "Default")
      (node (ref "C2") (pin "2") (pinfunction "2_2") (pintype "passive"))
      (node (ref "U8") (pin "42") (pinfunction "AREF_42") (pintype "power_in"))
    )
    (net (code "212") (name "Net-(U8-AVCC)") (class "Default")
      (node (ref "C6") (pin "2") (pinfunction "2_2") (pintype "passive"))
      (node (ref "L3") (pin "2") (pinfunction "2_2") (pintype "passive"))
      (node (ref "U8") (pin "24") (pinfunction "AVCC_24") (pintype "power_in"))
      (node (ref "U8") (pin "44") (pinfunction "AVCC1_44") (pintype "power_in"))
    )
    (net (code "213") (name "Net-(U8-UCAP)") (class "Default")
      (node (ref "C7") (pin "2") (pinfunction "2_2") (pintype "passive"))
      (node (ref "U8") (pin "6") (pinfunction "UCAP_6") (pintype "passive"))
    )
    (net (code "214") (name "Net-(U8-XTAL1)") (class "Default")
      (node (ref "R1") (pin "1") (pinfunction "1_1") (pintype "passive"))
      (node (ref "U8") (pin "17") (pinfunction "XTAL1_17") (pintype "bidirectional"))
      (node (ref "Y2") (pin "3") (pinfunction "3_3") (pintype "passive"))
    )
    (net (code "215") (name "Net-(U8-XTAL2)") (class "Default")
      (node (ref "R1") (pin "2") (pinfunction "2_2") (pintype "passive"))
      (node (ref "U8") (pin "16") (pinfunction "XTAL2_16") (pintype "bidirectional"))
      (node (ref "Y2") (pin "1") (pinfunction "1_1") (pintype "passive"))
    )
    (net (code "216") (name "Net-(U11B-+IN)") (class "Default")
      (node (ref "C82") (pin "2") (pinfunction "2_2") (pintype "passive"))
      (node (ref "R15") (pin "1") (pinfunction "1_1") (pintype "passive"))
      (node (ref "R16") (pin "2") (pinfunction "2_2") (pintype "passive"))
      (node (ref "U11") (pin "5") (pinfunction "+IN_5") (pintype "input"))
    )
    (net (code "217") (name "Net-(U11B--IN)") (class "Default")
      (node (ref "R41") (pin "2") (pinfunction "2_2") (pintype "passive"))
      (node (ref "R42") (pin "1") (pinfunction "1_1") (pintype "passive"))
      (node (ref "U11") (pin "6") (pinfunction "-IN_6") (pintype "input"))
    )
    (net (code "218") (name "Net-(U12-PB6(XTAL1{slash}TOSC1))") (class "Default")
      (node (ref "R30") (pin "2") (pinfunction "2_2") (pintype "passive"))
      (node (ref "U12") (pin "7") (pinfunction "PB6(XTAL1/TOSC1)_7") (pintype "bidirectional"))
      (node (ref "Y1") (pin "1") (pinfunction "1_1") (pintype "passive"))
    )
    (net (code "219") (name "Net-(U12-PB7(XTAL2{slash}TOSC2))") (class "Default")
      (node (ref "R30") (pin "1") (pinfunction "1_1") (pintype "passive"))
      (node (ref "U12") (pin "8") (pinfunction "PB7(XTAL2/TOSC2)_8") (pintype "bidirectional"))
      (node (ref "Y1") (pin "3") (pinfunction "3_3") (pintype "passive"))
    )
    (net (code "220") (name "Net-(U12-PD0(RXD))") (class "Default")
      (node (ref "R40") (pin "2") (pinfunction "2_2") (pintype "passive"))
      (node (ref "U12") (pin "30") (pinfunction "PD0(RXD)_30") (pintype "bidirectional"))
    )
    (net (code "221") (name "Net-(U13-CS)") (class "Default")
      (node (ref "C95") (pin "1") (pinfunction "1_1") (pintype "passive"))
      (node (ref "L15") (pin "2") (pinfunction "2_2") (pintype "passive"))
      (node (ref "U13") (pin "1") (pinfunction "VDD_1") (pintype "bidirectional"))
      (node (ref "U13") (pin "6") (pinfunction "VSS_6") (pintype "bidirectional"))
      (node (ref "U13") (pin "7") (pinfunction "CS_7") (pintype "bidirectional"))
    )
    (net (code "222") (name "Net-(X2-D+)") (class "Default")
      (node (ref "R2") (pin "1") (pinfunction "1_1") (pintype "passive"))
      (node (ref "X2") (pin "P3") (pinfunction "D+_P3") (pintype "bidirectional"))
      (node (ref "Z1") (pin "1") (pinfunction "1_1") (pintype "passive"))
    )
    (net (code "223") (name "Net-(X2-D-)") (class "Default")
      (node (ref "R4") (pin "1") (pinfunction "1_1") (pintype "passive"))
      (node (ref "X2") (pin "P2") (pinfunction "D-_P2") (pintype "bidirectional"))
      (node (ref "Z2") (pin "1") (pinfunction "1_1") (pintype "passive"))
    )
    (net (code "224") (name "Net-(X2-VBUS)") (class "Default")
      (node (ref "F1") (pin "2") (pinfunction "2_2") (pintype "passive"))
      (node (ref "X2") (pin "P1") (pinfunction "VBUS_P1") (pintype "power_in"))
    )
    (net (code "225") (name "POWER_VCC") (class "Default")
      (node (ref "Q4") (pin "2") (pinfunction "G_2") (pintype "passive"))
      (node (ref "U8") (pin "25") (pinfunction "(ICP1/ADC8)PD4_25") (pintype "bidirectional"))
    )
    (net (code "226") (name "QA") (class "Default")
      (node (ref "B1") (pin "SIG1A") (pinfunction "SIG1_SIG1A") (pintype "bidirectional"))
      (node (ref "B1") (pin "SIG1B") (pinfunction "SIG1_SIG1B") (pintype "bidirectional"))
      (node (ref "B1") (pin "SIG1C") (pinfunction "SIG1_SIG1C") (pintype "bidirectional"))
      (node (ref "B1") (pin "SIG1D") (pinfunction "SIG1_SIG1D") (pintype "bidirectional"))
      (node (ref "B3") (pin "SIG1A") (pinfunction "SIG1_SIG1A") (pintype "bidirectional"))
      (node (ref "B3") (pin "SIG1B") (pinfunction "SIG1_SIG1B") (pintype "bidirectional"))
      (node (ref "B3") (pin "SIG1C") (pinfunction "SIG1_SIG1C") (pintype "bidirectional"))
      (node (ref "B3") (pin "SIG1D") (pinfunction "SIG1_SIG1D") (pintype "bidirectional"))
      (node (ref "U10") (pin "3") (pinfunction "QA_3") (pintype "output"))
    )
    (net (code "227") (name "QB") (class "Default")
      (node (ref "B1") (pin "SIG1E") (pinfunction "SIG1_SIG1E") (pintype "bidirectional"))
      (node (ref "B1") (pin "SIG1F") (pinfunction "SIG1_SIG1F") (pintype "bidirectional"))
      (node (ref "B1") (pin "SIG1G") (pinfunction "SIG1_SIG1G") (pintype "bidirectional"))
      (node (ref "B1") (pin "SIG1H") (pinfunction "SIG1_SIG1H") (pintype "bidirectional"))
      (node (ref "B3") (pin "SIG1E") (pinfunction "SIG1_SIG1E") (pintype "bidirectional"))
      (node (ref "B3") (pin "SIG1F") (pinfunction "SIG1_SIG1F") (pintype "bidirectional"))
      (node (ref "B3") (pin "SIG1G") (pinfunction "SIG1_SIG1G") (pintype "bidirectional"))
      (node (ref "B3") (pin "SIG1H") (pinfunction "SIG1_SIG1H") (pintype "bidirectional"))
      (node (ref "U10") (pin "4") (pinfunction "QB_4") (pintype "output"))
    )
    (net (code "228") (name "QC") (class "Default")
      (node (ref "B1") (pin "SIG1I") (pinfunction "SIG1_SIG1I") (pintype "bidirectional"))
      (node (ref "B1") (pin "SIG1J") (pinfunction "SIG1_SIG1J") (pintype "bidirectional"))
      (node (ref "B1") (pin "SIG1K") (pinfunction "SIG1_SIG1K") (pintype "bidirectional"))
      (node (ref "B1") (pin "SIG1L") (pinfunction "SIG1_SIG1L") (pintype "bidirectional"))
      (node (ref "B3") (pin "SIG1I") (pinfunction "SIG1_SIG1I") (pintype "bidirectional"))
      (node (ref "B3") (pin "SIG1J") (pinfunction "SIG1_SIG1J") (pintype "bidirectional"))
      (node (ref "B3") (pin "SIG1K") (pinfunction "SIG1_SIG1K") (pintype "bidirectional"))
      (node (ref "B3") (pin "SIG1L") (pinfunction "SIG1_SIG1L") (pintype "bidirectional"))
      (node (ref "U10") (pin "5") (pinfunction "QC_5") (pintype "output"))
    )
    (net (code "229") (name "QD") (class "Default")
      (node (ref "B1") (pin "SIG1M") (pinfunction "SIG1_SIG1M") (pintype "bidirectional"))
      (node (ref "B1") (pin "SIG1N") (pinfunction "SIG1_SIG1N") (pintype "bidirectional"))
      (node (ref "B1") (pin "SIG1O") (pinfunction "SIG1_SIG1O") (pintype "bidirectional"))
      (node (ref "B1") (pin "SIG1P") (pinfunction "SIG1_SIG1P") (pintype "bidirectional"))
      (node (ref "B3") (pin "SIG1M") (pinfunction "SIG1_SIG1M") (pintype "bidirectional"))
      (node (ref "B3") (pin "SIG1N") (pinfunction "SIG1_SIG1N") (pintype "bidirectional"))
      (node (ref "B3") (pin "SIG1O") (pinfunction "SIG1_SIG1O") (pintype "bidirectional"))
      (node (ref "B3") (pin "SIG1P") (pinfunction "SIG1_SIG1P") (pintype "bidirectional"))
      (node (ref "U10") (pin "6") (pinfunction "QD_6") (pintype "output"))
    )
    (net (code "230") (name "QE") (class "Default")
      (node (ref "B2") (pin "SIG1A") (pinfunction "SIG1_SIG1A") (pintype "bidirectional"))
      (node (ref "B2") (pin "SIG1B") (pinfunction "SIG1_SIG1B") (pintype "bidirectional"))
      (node (ref "B2") (pin "SIG1C") (pinfunction "SIG1_SIG1C") (pintype "bidirectional"))
      (node (ref "B2") (pin "SIG1D") (pinfunction "SIG1_SIG1D") (pintype "bidirectional"))
      (node (ref "B4") (pin "SIG1A") (pinfunction "SIG1_SIG1A") (pintype "bidirectional"))
      (node (ref "B4") (pin "SIG1B") (pinfunction "SIG1_SIG1B") (pintype "bidirectional"))
      (node (ref "B4") (pin "SIG1C") (pinfunction "SIG1_SIG1C") (pintype "bidirectional"))
      (node (ref "B4") (pin "SIG1D") (pinfunction "SIG1_SIG1D") (pintype "bidirectional"))
      (node (ref "U10") (pin "10") (pinfunction "QE_10") (pintype "output"))
    )
    (net (code "231") (name "QF") (class "Default")
      (node (ref "B2") (pin "SIG1E") (pinfunction "SIG1_SIG1E") (pintype "bidirectional"))
      (node (ref "B2") (pin "SIG1F") (pinfunction "SIG1_SIG1F") (pintype "bidirectional"))
      (node (ref "B2") (pin "SIG1G") (pinfunction "SIG1_SIG1G") (pintype "bidirectional"))
      (node (ref "B2") (pin "SIG1H") (pinfunction "SIG1_SIG1H") (pintype "bidirectional"))
      (node (ref "B4") (pin "SIG1E") (pinfunction "SIG1_SIG1E") (pintype "bidirectional"))
      (node (ref "B4") (pin "SIG1F") (pinfunction "SIG1_SIG1F") (pintype "bidirectional"))
      (node (ref "B4") (pin "SIG1G") (pinfunction "SIG1_SIG1G") (pintype "bidirectional"))
      (node (ref "B4") (pin "SIG1H") (pinfunction "SIG1_SIG1H") (pintype "bidirectional"))
      (node (ref "U10") (pin "11") (pinfunction "QF_11") (pintype "output"))
    )
    (net (code "232") (name "QG") (class "Default")
      (node (ref "B2") (pin "SIG1I") (pinfunction "SIG1_SIG1I") (pintype "bidirectional"))
      (node (ref "B2") (pin "SIG1J") (pinfunction "SIG1_SIG1J") (pintype "bidirectional"))
      (node (ref "B2") (pin "SIG1K") (pinfunction "SIG1_SIG1K") (pintype "bidirectional"))
      (node (ref "B2") (pin "SIG1L") (pinfunction "SIG1_SIG1L") (pintype "bidirectional"))
      (node (ref "B4") (pin "SIG1I") (pinfunction "SIG1_SIG1I") (pintype "bidirectional"))
      (node (ref "B4") (pin "SIG1J") (pinfunction "SIG1_SIG1J") (pintype "bidirectional"))
      (node (ref "B4") (pin "SIG1K") (pinfunction "SIG1_SIG1K") (pintype "bidirectional"))
      (node (ref "B4") (pin "SIG1L") (pinfunction "SIG1_SIG1L") (pintype "bidirectional"))
      (node (ref "U10") (pin "12") (pinfunction "QG_12") (pintype "output"))
    )
    (net (code "233") (name "QH") (class "Default")
      (node (ref "B2") (pin "SIG1M") (pinfunction "SIG1_SIG1M") (pintype "bidirectional"))
      (node (ref "B2") (pin "SIG1N") (pinfunction "SIG1_SIG1N") (pintype "bidirectional"))
      (node (ref "B2") (pin "SIG1O") (pinfunction "SIG1_SIG1O") (pintype "bidirectional"))
      (node (ref "B2") (pin "SIG1P") (pinfunction "SIG1_SIG1P") (pintype "bidirectional"))
      (node (ref "B4") (pin "SIG1M") (pinfunction "SIG1_SIG1M") (pintype "bidirectional"))
      (node (ref "B4") (pin "SIG1N") (pinfunction "SIG1_SIG1N") (pintype "bidirectional"))
      (node (ref "B4") (pin "SIG1O") (pinfunction "SIG1_SIG1O") (pintype "bidirectional"))
      (node (ref "B4") (pin "SIG1P") (pinfunction "SIG1_SIG1P") (pintype "bidirectional"))
      (node (ref "U10") (pin "13") (pinfunction "QH_13") (pintype "output"))
    )
    (net (code "234") (name "RD+") (class "Default")
      (node (ref "R2") (pin "2") (pinfunction "2_2") (pintype "passive"))
      (node (ref "U8") (pin "4") (pinfunction "D+_4") (pintype "bidirectional"))
    )
    (net (code "235") (name "RD-") (class "Default")
      (node (ref "R4") (pin "2") (pinfunction "2_2") (pintype "passive"))
      (node (ref "U8") (pin "3") (pinfunction "D-_3") (pintype "bidirectional"))
    )
    (net (code "236") (name "RESET") (class "Default")
      (node (ref "C93") (pin "1") (pinfunction "1_1") (pintype "passive"))
      (node (ref "ICSP1") (pin "5") (pinfunction "5_5") (pintype "passive"))
      (node (ref "R17") (pin "1") (pinfunction "1_1") (pintype "passive"))
      (node (ref "U12") (pin "29") (pinfunction "PC6(/RESET)_29") (pintype "bidirectional"))
    )
    (net (code "237") (name "RST") (class "Default")
      (node (ref "D16") (pin "A") (pinfunction "A_A") (pintype "passive"))
      (node (ref "ICSP") (pin "5") (pinfunction "5_5") (pintype "passive"))
      (node (ref "R6") (pin "1") (pinfunction "1_1") (pintype "passive"))
      (node (ref "RST") (pin "2") (pinfunction "2_2") (pintype "passive"))
      (node (ref "U7") (pin "7") (pinfunction "I_7") (pintype "input"))
      (node (ref "U8") (pin "13") (pinfunction "RESET_13") (pintype "input"))
    )
    (net (code "238") (name "RXLED") (class "Default")
      (node (ref "R13") (pin "1") (pinfunction "1_1") (pintype "passive"))
      (node (ref "U8") (pin "8") (pinfunction "(SS/PCINT0)PB0_8") (pintype "bidirectional"))
    )
    (net (code "239") (name "RXLEO") (class "Default")
      (node (ref "U1") (pin "4") (pinfunction "Z_4") (pintype "bidirectional"))
      (node (ref "U8") (pin "20") (pinfunction "(RXD1/AIN1/INT2)PD2_20") (pintype "bidirectional"))
    )
    (net (code "240") (name "RXWIFI") (class "Default")
      (node (ref "U1") (pin "1") (pinfunction "I1_1") (pintype "bidirectional"))
      (node (ref "U2") (pin "P$13") (pinfunction "TX_P$13") (pintype "bidirectional"))
    )
    (net (code "241") (name "SCKA") (class "Default")
      (node (ref "ICSP") (pin "3") (pinfunction "3_3") (pintype "passive"))
      (node (ref "U8") (pin "9") (pinfunction "(SCLK/PCINT1)PB1_9") (pintype "bidirectional"))
    )
    (net (code "242") (name "SCKB") (class "Default")
      (node (ref "ICSP1") (pin "3") (pinfunction "3_3") (pintype "passive"))
      (node (ref "U12") (pin "17") (pinfunction "PB5(SCK)_17") (pintype "bidirectional"))
    )
    (net (code "243") (name "SCL") (class "Default")
      (node (ref "Q3") (pin "3") (pinfunction "D_3") (pintype "passive"))
      (node (ref "R10") (pin "1") (pinfunction "1_1") (pintype "passive"))
      (node (ref "U12") (pin "28") (pinfunction "PC5(ADC5/SCL)_28") (pintype "bidirectional"))
      (node (ref "U8") (pin "18") (pinfunction "(OC0B/SCL/INT0)PD0_18") (pintype "bidirectional"))
    )
    (net (code "244") (name "SDA") (class "Default")
      (node (ref "Q2") (pin "3") (pinfunction "D_3") (pintype "passive"))
      (node (ref "R8") (pin "1") (pinfunction "1_1") (pintype "passive"))
      (node (ref "U12") (pin "27") (pinfunction "PC4(ADC4/SDA)_27") (pintype "bidirectional"))
      (node (ref "U8") (pin "19") (pinfunction "(SDA/INT1)PD1_19") (pintype "bidirectional"))
    )
    (net (code "245") (name "SELECT") (class "Default")
      (node (ref "U1") (pin "6") (pinfunction "S_6") (pintype "bidirectional"))
      (node (ref "U8") (pin "26") (pinfunction "(T1/#OC4D/ADC9)PD6_26") (pintype "bidirectional"))
    )
    (net (code "246") (name "T1") (class "Default")
      (node (ref "B1") (pin "5C") (pinfunction "VDD_5C") (pintype "bidirectional"))
      (node (ref "B1") (pin "5D") (pinfunction "VDD_5D") (pintype "bidirectional"))
      (node (ref "B1") (pin "5G") (pinfunction "VDD_5G") (pintype "bidirectional"))
      (node (ref "B1") (pin "5H") (pinfunction "VDD_5H") (pintype "bidirectional"))
      (node (ref "B1") (pin "5K") (pinfunction "VDD_5K") (pintype "bidirectional"))
      (node (ref "B1") (pin "5L") (pinfunction "VDD_5L") (pintype "bidirectional"))
      (node (ref "B1") (pin "5O") (pinfunction "VDD_5O") (pintype "bidirectional"))
      (node (ref "B1") (pin "5P") (pinfunction "VDD_5P") (pintype "bidirectional"))
      (node (ref "Q6") (pin "7") (pinfunction "D_7") (pintype "passive"))
      (node (ref "Q6") (pin "8") (pinfunction "D_8") (pintype "passive"))
    )
    (net (code "247") (name "T2") (class "Default")
      (node (ref "B1") (pin "5A") (pinfunction "VDD_5A") (pintype "bidirectional"))
      (node (ref "B1") (pin "5B") (pinfunction "VDD_5B") (pintype "bidirectional"))
      (node (ref "B1") (pin "5E") (pinfunction "VDD_5E") (pintype "bidirectional"))
      (node (ref "B1") (pin "5F") (pinfunction "VDD_5F") (pintype "bidirectional"))
      (node (ref "B1") (pin "5I") (pinfunction "VDD_5I") (pintype "bidirectional"))
      (node (ref "B1") (pin "5J") (pinfunction "VDD_5J") (pintype "bidirectional"))
      (node (ref "B1") (pin "5M") (pinfunction "VDD_5M") (pintype "bidirectional"))
      (node (ref "B1") (pin "5N") (pinfunction "VDD_5N") (pintype "bidirectional"))
      (node (ref "Q6") (pin "5") (pinfunction "D_5") (pintype "passive"))
      (node (ref "Q6") (pin "6") (pinfunction "D_6") (pintype "passive"))
    )
    (net (code "248") (name "T3") (class "Default")
      (node (ref "B2") (pin "5A") (pinfunction "VDD_5A") (pintype "bidirectional"))
      (node (ref "B2") (pin "5B") (pinfunction "VDD_5B") (pintype "bidirectional"))
      (node (ref "B2") (pin "5E") (pinfunction "VDD_5E") (pintype "bidirectional"))
      (node (ref "B2") (pin "5F") (pinfunction "VDD_5F") (pintype "bidirectional"))
      (node (ref "B2") (pin "5I") (pinfunction "VDD_5I") (pintype "bidirectional"))
      (node (ref "B2") (pin "5J") (pinfunction "VDD_5J") (pintype "bidirectional"))
      (node (ref "B2") (pin "5M") (pinfunction "VDD_5M") (pintype "bidirectional"))
      (node (ref "B2") (pin "5N") (pinfunction "VDD_5N") (pintype "bidirectional"))
      (node (ref "Q7") (pin "7") (pinfunction "D_7") (pintype "passive"))
      (node (ref "Q7") (pin "8") (pinfunction "D_8") (pintype "passive"))
    )
    (net (code "249") (name "T4") (class "Default")
      (node (ref "B2") (pin "5C") (pinfunction "VDD_5C") (pintype "bidirectional"))
      (node (ref "B2") (pin "5D") (pinfunction "VDD_5D") (pintype "bidirectional"))
      (node (ref "B2") (pin "5G") (pinfunction "VDD_5G") (pintype "bidirectional"))
      (node (ref "B2") (pin "5H") (pinfunction "VDD_5H") (pintype "bidirectional"))
      (node (ref "B2") (pin "5K") (pinfunction "VDD_5K") (pintype "bidirectional"))
      (node (ref "B2") (pin "5L") (pinfunction "VDD_5L") (pintype "bidirectional"))
      (node (ref "B2") (pin "5O") (pinfunction "VDD_5O") (pintype "bidirectional"))
      (node (ref "B2") (pin "5P") (pinfunction "VDD_5P") (pintype "bidirectional"))
      (node (ref "Q7") (pin "5") (pinfunction "D_5") (pintype "passive"))
      (node (ref "Q7") (pin "6") (pinfunction "D_6") (pintype "passive"))
    )
    (net (code "250") (name "T5") (class "Default")
      (node (ref "B3") (pin "5C") (pinfunction "VDD_5C") (pintype "bidirectional"))
      (node (ref "B3") (pin "5D") (pinfunction "VDD_5D") (pintype "bidirectional"))
      (node (ref "B3") (pin "5G") (pinfunction "VDD_5G") (pintype "bidirectional"))
      (node (ref "B3") (pin "5H") (pinfunction "VDD_5H") (pintype "bidirectional"))
      (node (ref "B3") (pin "5K") (pinfunction "VDD_5K") (pintype "bidirectional"))
      (node (ref "B3") (pin "5L") (pinfunction "VDD_5L") (pintype "bidirectional"))
      (node (ref "B3") (pin "5O") (pinfunction "VDD_5O") (pintype "bidirectional"))
      (node (ref "B3") (pin "5P") (pinfunction "VDD_5P") (pintype "bidirectional"))
      (node (ref "Q8") (pin "7") (pinfunction "D_7") (pintype "passive"))
      (node (ref "Q8") (pin "8") (pinfunction "D_8") (pintype "passive"))
    )
    (net (code "251") (name "T6") (class "Default")
      (node (ref "B3") (pin "5A") (pinfunction "VDD_5A") (pintype "bidirectional"))
      (node (ref "B3") (pin "5B") (pinfunction "VDD_5B") (pintype "bidirectional"))
      (node (ref "B3") (pin "5E") (pinfunction "VDD_5E") (pintype "bidirectional"))
      (node (ref "B3") (pin "5F") (pinfunction "VDD_5F") (pintype "bidirectional"))
      (node (ref "B3") (pin "5I") (pinfunction "VDD_5I") (pintype "bidirectional"))
      (node (ref "B3") (pin "5J") (pinfunction "VDD_5J") (pintype "bidirectional"))
      (node (ref "B3") (pin "5M") (pinfunction "VDD_5M") (pintype "bidirectional"))
      (node (ref "B3") (pin "5N") (pinfunction "VDD_5N") (pintype "bidirectional"))
      (node (ref "Q8") (pin "5") (pinfunction "D_5") (pintype "passive"))
      (node (ref "Q8") (pin "6") (pinfunction "D_6") (pintype "passive"))
    )
    (net (code "252") (name "T7") (class "Default")
      (node (ref "B4") (pin "5A") (pinfunction "VDD_5A") (pintype "bidirectional"))
      (node (ref "B4") (pin "5B") (pinfunction "VDD_5B") (pintype "bidirectional"))
      (node (ref "B4") (pin "5E") (pinfunction "VDD_5E") (pintype "bidirectional"))
      (node (ref "B4") (pin "5F") (pinfunction "VDD_5F") (pintype "bidirectional"))
      (node (ref "B4") (pin "5I") (pinfunction "VDD_5I") (pintype "bidirectional"))
      (node (ref "B4") (pin "5J") (pinfunction "VDD_5J") (pintype "bidirectional"))
      (node (ref "B4") (pin "5M") (pinfunction "VDD_5M") (pintype "bidirectional"))
      (node (ref "B4") (pin "5N") (pinfunction "VDD_5N") (pintype "bidirectional"))
      (node (ref "Q9") (pin "7") (pinfunction "D_7") (pintype "passive"))
      (node (ref "Q9") (pin "8") (pinfunction "D_8") (pintype "passive"))
    )
    (net (code "253") (name "T8") (class "Default")
      (node (ref "B4") (pin "5C") (pinfunction "VDD_5C") (pintype "bidirectional"))
      (node (ref "B4") (pin "5D") (pinfunction "VDD_5D") (pintype "bidirectional"))
      (node (ref "B4") (pin "5G") (pinfunction "VDD_5G") (pintype "bidirectional"))
      (node (ref "B4") (pin "5H") (pinfunction "VDD_5H") (pintype "bidirectional"))
      (node (ref "B4") (pin "5K") (pinfunction "VDD_5K") (pintype "bidirectional"))
      (node (ref "B4") (pin "5L") (pinfunction "VDD_5L") (pintype "bidirectional"))
      (node (ref "B4") (pin "5O") (pinfunction "VDD_5O") (pintype "bidirectional"))
      (node (ref "B4") (pin "5P") (pinfunction "VDD_5P") (pintype "bidirectional"))
      (node (ref "Q9") (pin "5") (pinfunction "D_5") (pintype "passive"))
      (node (ref "Q9") (pin "6") (pinfunction "D_6") (pintype "passive"))
    )
    (net (code "254") (name "TXA") (class "Default")
      (node (ref "U1") (pin "3") (pinfunction "I0_3") (pintype "bidirectional"))
      (node (ref "U12") (pin "31") (pinfunction "PD1(TXD)_31") (pintype "bidirectional"))
    )
    (net (code "255") (name "TXLED") (class "Default")
      (node (ref "R12") (pin "1") (pinfunction "1_1") (pintype "passive"))
      (node (ref "U8") (pin "22") (pinfunction "(XCK1/#CTS)PD5_22") (pintype "bidirectional"))
    )
    (net (code "256") (name "TXWIFI") (class "Default")
      (node (ref "R40") (pin "1") (pinfunction "1_1") (pintype "passive"))
      (node (ref "U7") (pin "3") (pinfunction "I_3") (pintype "input"))
      (node (ref "U8") (pin "21") (pinfunction "(TXD1/INT3)PD3_21") (pintype "bidirectional"))
    )
    (net (code "257") (name "VBAT") (class "Default")
      (node (ref "BAT") (pin "2") (pinfunction "2_2") (pintype "passive"))
      (node (ref "C77") (pin "1") (pinfunction "1_1") (pintype "passive"))
      (node (ref "C78") (pin "1") (pinfunction "1_1") (pintype "passive"))
      (node (ref "U11") (pin "3") (pinfunction "+IN_3") (pintype "input"))
      (node (ref "U3") (pin "5") (pinfunction "VIN_5") (pintype "bidirectional"))
      (node (ref "U3") (pin "6") (pinfunction "EN_6") (pintype "bidirectional"))
      (node (ref "U3") (pin "7") (pinfunction "PS/SYNC_7") (pintype "bidirectional"))
      (node (ref "U3") (pin "8") (pinfunction "VINA_8") (pintype "bidirectional"))
      (node (ref "U5") (pin "3") (pinfunction "VBAT_3") (pintype "bidirectional"))
      (node (ref "U5") (pin "4") (pinfunction "VBAT_4") (pintype "bidirectional"))
    )
    (net (code "258") (name "VBATS") (class "Default")
      (node (ref "U11") (pin "1") (pinfunction "OUT_1") (pintype "output"))
      (node (ref "U11") (pin "2") (pinfunction "-IN_2") (pintype "input"))
      (node (ref "U12") (pin "23") (pinfunction "PC0(ADC0)_23") (pintype "bidirectional"))
      (node (ref "U8") (pin "36") (pinfunction "(ADC7/TDI)PF7_36") (pintype "bidirectional"))
    )
    (net (code "259") (name "VCC") (class "Default")
      (node (ref "B1") (pin "3A") (pinfunction "VCC_3A") (pintype "bidirectional"))
      (node (ref "B1") (pin "3B") (pinfunction "VCC_3B") (pintype "bidirectional"))
      (node (ref "B1") (pin "3C") (pinfunction "VCC_3C") (pintype "bidirectional"))
      (node (ref "B1") (pin "3D") (pinfunction "VCC_3D") (pintype "bidirectional"))
      (node (ref "B1") (pin "3E") (pinfunction "VCC_3E") (pintype "bidirectional"))
      (node (ref "B1") (pin "3F") (pinfunction "VCC_3F") (pintype "bidirectional"))
      (node (ref "B1") (pin "3G") (pinfunction "VCC_3G") (pintype "bidirectional"))
      (node (ref "B1") (pin "3H") (pinfunction "VCC_3H") (pintype "bidirectional"))
      (node (ref "B1") (pin "3I") (pinfunction "VCC_3I") (pintype "bidirectional"))
      (node (ref "B1") (pin "3J") (pinfunction "VCC_3J") (pintype "bidirectional"))
      (node (ref "B1") (pin "3K") (pinfunction "VCC_3K") (pintype "bidirectional"))
      (node (ref "B1") (pin "3L") (pinfunction "VCC_3L") (pintype "bidirectional"))
      (node (ref "B1") (pin "3M") (pinfunction "VCC_3M") (pintype "bidirectional"))
      (node (ref "B1") (pin "3N") (pinfunction "VCC_3N") (pintype "bidirectional"))
      (node (ref "B1") (pin "3O") (pinfunction "VCC_3O") (pintype "bidirectional"))
      (node (ref "B1") (pin "3P") (pinfunction "VCC_3P") (pintype "bidirectional"))
      (node (ref "B2") (pin "3A") (pinfunction "VCC_3A") (pintype "bidirectional"))
      (node (ref "B2") (pin "3B") (pinfunction "VCC_3B") (pintype "bidirectional"))
      (node (ref "B2") (pin "3C") (pinfunction "VCC_3C") (pintype "bidirectional"))
      (node (ref "B2") (pin "3D") (pinfunction "VCC_3D") (pintype "bidirectional"))
      (node (ref "B2") (pin "3E") (pinfunction "VCC_3E") (pintype "bidirectional"))
      (node (ref "B2") (pin "3F") (pinfunction "VCC_3F") (pintype "bidirectional"))
      (node (ref "B2") (pin "3G") (pinfunction "VCC_3G") (pintype "bidirectional"))
      (node (ref "B2") (pin "3H") (pinfunction "VCC_3H") (pintype "bidirectional"))
      (node (ref "B2") (pin "3I") (pinfunction "VCC_3I") (pintype "bidirectional"))
      (node (ref "B2") (pin "3J") (pinfunction "VCC_3J") (pintype "bidirectional"))
      (node (ref "B2") (pin "3K") (pinfunction "VCC_3K") (pintype "bidirectional"))
      (node (ref "B2") (pin "3L") (pinfunction "VCC_3L") (pintype "bidirectional"))
      (node (ref "B2") (pin "3M") (pinfunction "VCC_3M") (pintype "bidirectional"))
      (node (ref "B2") (pin "3N") (pinfunction "VCC_3N") (pintype "bidirectional"))
      (node (ref "B2") (pin "3O") (pinfunction "VCC_3O") (pintype "bidirectional"))
      (node (ref "B2") (pin "3P") (pinfunction "VCC_3P") (pintype "bidirectional"))
      (node (ref "B3") (pin "3A") (pinfunction "VCC_3A") (pintype "bidirectional"))
      (node (ref "B3") (pin "3B") (pinfunction "VCC_3B") (pintype "bidirectional"))
      (node (ref "B3") (pin "3C") (pinfunction "VCC_3C") (pintype "bidirectional"))
      (node (ref "B3") (pin "3D") (pinfunction "VCC_3D") (pintype "bidirectional"))
      (node (ref "B3") (pin "3E") (pinfunction "VCC_3E") (pintype "bidirectional"))
      (node (ref "B3") (pin "3F") (pinfunction "VCC_3F") (pintype "bidirectional"))
      (node (ref "B3") (pin "3G") (pinfunction "VCC_3G") (pintype "bidirectional"))
      (node (ref "B3") (pin "3H") (pinfunction "VCC_3H") (pintype "bidirectional"))
      (node (ref "B3") (pin "3I") (pinfunction "VCC_3I") (pintype "bidirectional"))
      (node (ref "B3") (pin "3J") (pinfunction "VCC_3J") (pintype "bidirectional"))
      (node (ref "B3") (pin "3K") (pinfunction "VCC_3K") (pintype "bidirectional"))
      (node (ref "B3") (pin "3L") (pinfunction "VCC_3L") (pintype "bidirectional"))
      (node (ref "B3") (pin "3M") (pinfunction "VCC_3M") (pintype "bidirectional"))
      (node (ref "B3") (pin "3N") (pinfunction "VCC_3N") (pintype "bidirectional"))
      (node (ref "B3") (pin "3O") (pinfunction "VCC_3O") (pintype "bidirectional"))
      (node (ref "B3") (pin "3P") (pinfunction "VCC_3P") (pintype "bidirectional"))
      (node (ref "B4") (pin "3A") (pinfunction "VCC_3A") (pintype "bidirectional"))
      (node (ref "B4") (pin "3B") (pinfunction "VCC_3B") (pintype "bidirectional"))
      (node (ref "B4") (pin "3C") (pinfunction "VCC_3C") (pintype "bidirectional"))
      (node (ref "B4") (pin "3D") (pinfunction "VCC_3D") (pintype "bidirectional"))
      (node (ref "B4") (pin "3E") (pinfunction "VCC_3E") (pintype "bidirectional"))
      (node (ref "B4") (pin "3F") (pinfunction "VCC_3F") (pintype "bidirectional"))
      (node (ref "B4") (pin "3G") (pinfunction "VCC_3G") (pintype "bidirectional"))
      (node (ref "B4") (pin "3H") (pinfunction "VCC_3H") (pintype "bidirectional"))
      (node (ref "B4") (pin "3I") (pinfunction "VCC_3I") (pintype "bidirectional"))
      (node (ref "B4") (pin "3J") (pinfunction "VCC_3J") (pintype "bidirectional"))
      (node (ref "B4") (pin "3K") (pinfunction "VCC_3K") (pintype "bidirectional"))
      (node (ref "B4") (pin "3L") (pinfunction "VCC_3L") (pintype "bidirectional"))
      (node (ref "B4") (pin "3M") (pinfunction "VCC_3M") (pintype "bidirectional"))
      (node (ref "B4") (pin "3N") (pinfunction "VCC_3N") (pintype "bidirectional"))
      (node (ref "B4") (pin "3O") (pinfunction "VCC_3O") (pintype "bidirectional"))
      (node (ref "B4") (pin "3P") (pinfunction "VCC_3P") (pintype "bidirectional"))
      (node (ref "C10") (pin "1") (pinfunction "1_1") (pintype "passive"))
      (node (ref "C11") (pin "1") (pinfunction "1_1") (pintype "passive"))
      (node (ref "C12") (pin "1") (pinfunction "1_1") (pintype "passive"))
      (node (ref "C13") (pin "1") (pinfunction "1_1") (pintype "passive"))
      (node (ref "C14") (pin "1") (pinfunction "1_1") (pintype "passive"))
      (node (ref "C15") (pin "1") (pinfunction "1_1") (pintype "passive"))
      (node (ref "C16") (pin "1") (pinfunction "1_1") (pintype "passive"))
      (node (ref "C17") (pin "1") (pinfunction "1_1") (pintype "passive"))
      (node (ref "C18") (pin "1") (pinfunction "1_1") (pintype "passive"))
      (node (ref "C19") (pin "1") (pinfunction "1_1") (pintype "passive"))
      (node (ref "C20") (pin "1") (pinfunction "1_1") (pintype "passive"))
      (node (ref "C21") (pin "1") (pinfunction "1_1") (pintype "passive"))
      (node (ref "C22") (pin "1") (pinfunction "1_1") (pintype "passive"))
      (node (ref "C23") (pin "1") (pinfunction "1_1") (pintype "passive"))
      (node (ref "C24") (pin "1") (pinfunction "1_1") (pintype "passive"))
      (node (ref "C25") (pin "1") (pinfunction "1_1") (pintype "passive"))
      (node (ref "C26") (pin "1") (pinfunction "1_1") (pintype "passive"))
      (node (ref "C27") (pin "1") (pinfunction "1_1") (pintype "passive"))
      (node (ref "C28") (pin "1") (pinfunction "1_1") (pintype "passive"))
      (node (ref "C29") (pin "1") (pinfunction "1_1") (pintype "passive"))
      (node (ref "C30") (pin "1") (pinfunction "1_1") (pintype "passive"))
      (node (ref "C31") (pin "1") (pinfunction "1_1") (pintype "passive"))
      (node (ref "C32") (pin "1") (pinfunction "1_1") (pintype "passive"))
      (node (ref "C33") (pin "1") (pinfunction "1_1") (pintype "passive"))
      (node (ref "C34") (pin "1") (pinfunction "1_1") (pintype "passive"))
      (node (ref "C35") (pin "1") (pinfunction "1_1") (pintype "passive"))
      (node (ref "C36") (pin "1") (pinfunction "1_1") (pintype "passive"))
      (node (ref "C37") (pin "1") (pinfunction "1_1") (pintype "passive"))
      (node (ref "C38") (pin "1") (pinfunction "1_1") (pintype "passive"))
      (node (ref "C39") (pin "1") (pinfunction "1_1") (pintype "passive"))
      (node (ref "C40") (pin "1") (pinfunction "1_1") (pintype "passive"))
      (node (ref "C41") (pin "1") (pinfunction "1_1") (pintype "passive"))
      (node (ref "C42") (pin "1") (pinfunction "1_1") (pintype "passive"))
      (node (ref "C43") (pin "1") (pinfunction "1_1") (pintype "passive"))
      (node (ref "C44") (pin "1") (pinfunction "1_1") (pintype "passive"))
      (node (ref "C45") (pin "1") (pinfunction "1_1") (pintype "passive"))
      (node (ref "C46") (pin "1") (pinfunction "1_1") (pintype "passive"))
      (node (ref "C47") (pin "1") (pinfunction "1_1") (pintype "passive"))
      (node (ref "C48") (pin "1") (pinfunction "1_1") (pintype "passive"))
      (node (ref "C49") (pin "1") (pinfunction "1_1") (pintype "passive"))
      (node (ref "C50") (pin "1") (pinfunction "1_1") (pintype "passive"))
      (node (ref "C51") (pin "1") (pinfunction "1_1") (pintype "passive"))
      (node (ref "C52") (pin "1") (pinfunction "1_1") (pintype "passive"))
      (node (ref "C53") (pin "1") (pinfunction "1_1") (pintype "passive"))
      (node (ref "C54") (pin "1") (pinfunction "1_1") (pintype "passive"))
      (node (ref "C55") (pin "1") (pinfunction "1_1") (pintype "passive"))
      (node (ref "C56") (pin "1") (pinfunction "1_1") (pintype "passive"))
      (node (ref "C57") (pin "1") (pinfunction "1_1") (pintype "passive"))
      (node (ref "C58") (pin "1") (pinfunction "1_1") (pintype "passive"))
      (node (ref "C59") (pin "1") (pinfunction "1_1") (pintype "passive"))
      (node (ref "C60") (pin "1") (pinfunction "1_1") (pintype "passive"))
      (node (ref "C61") (pin "1") (pinfunction "1_1") (pintype "passive"))
      (node (ref "C62") (pin "1") (pinfunction "1_1") (pintype "passive"))
      (node (ref "C63") (pin "1") (pinfunction "1_1") (pintype "passive"))
      (node (ref "C64") (pin "1") (pinfunction "1_1") (pintype "passive"))
      (node (ref "C65") (pin "1") (pinfunction "1_1") (pintype "passive"))
      (node (ref "C66") (pin "1") (pinfunction "1_1") (pintype "passive"))
      (node (ref "C67") (pin "1") (pinfunction "1_1") (pintype "passive"))
      (node (ref "C68") (pin "1") (pinfunction "1_1") (pintype "passive"))
      (node (ref "C69") (pin "1") (pinfunction "1_1") (pintype "passive"))
      (node (ref "C70") (pin "1") (pinfunction "1_1") (pintype "passive"))
      (node (ref "C71") (pin "1") (pinfunction "1_1") (pintype "passive"))
      (node (ref "C74") (pin "1") (pinfunction "1_1") (pintype "passive"))
      (node (ref "C75") (pin "1") (pinfunction "1_1") (pintype "passive"))
      (node (ref "C8") (pin "1") (pinfunction "1_1") (pintype "passive"))
      (node (ref "C9") (pin "1") (pinfunction "1_1") (pintype "passive"))
      (node (ref "C91") (pin "1") (pinfunction "1_1") (pintype "passive"))
      (node (ref "Q4") (pin "7") (pinfunction "D_7") (pintype "passive"))
      (node (ref "Q4") (pin "8") (pinfunction "D_8") (pintype "passive"))
      (node (ref "R28") (pin "2") (pinfunction "2_2") (pintype "passive"))
      (node (ref "U10") (pin "14") (pinfunction "VCC_14") (pintype "power_in"))
      (node (ref "U10") (pin "9") (pinfunction "CLR_9") (pintype "input"))
      (node (ref "U6") (pin "5") (pinfunction "VIN_5") (pintype "bidirectional"))
      (node (ref "U9") (pin "16") (pinfunction "VCC_16") (pintype "power_in"))
    )
    (net (code "260") (name "VIN") (class "Default")
      (node (ref "C86") (pin "1") (pinfunction "1_1") (pintype "passive"))
      (node (ref "C87") (pin "1") (pinfunction "1_1") (pintype "passive"))
      (node (ref "D34") (pin "C") (pinfunction "C_C") (pintype "passive"))
      (node (ref "L16") (pin "2") (pinfunction "2_2") (pintype "passive"))
      (node (ref "U4") (pin "1") (pinfunction "VIN_1") (pintype "bidirectional"))
    )
    (net (code "261") (name "VUSB") (class "Default")
      (node (ref "C1") (pin "2") (pinfunction "2_2") (pintype "passive"))
      (node (ref "C5") (pin "2") (pinfunction "2_2") (pintype "passive"))
      (node (ref "F1") (pin "1") (pinfunction "1_1") (pintype "passive"))
      (node (ref "Q4") (pin "3") (pinfunction "S_3") (pintype "passive"))
      (node (ref "Q5") (pin "3") (pinfunction "S_3") (pintype "passive"))
      (node (ref "U12") (pin "25") (pinfunction "PC2(ADC2)_25") (pintype "bidirectional"))
      (node (ref "U8") (pin "7") (pinfunction "VBUS_7") (pintype "input"))
    )
    (net (code "262") (name "unconnected-(U2-3.3V-ROUT-PadP$17)") (class "Default")
      (node (ref "U2") (pin "P$17") (pinfunction "3.3V-ROUT_P$17") (pintype "bidirectional"))
    )
    (net (code "263") (name "unconnected-(U2-CLK-PadP$15)") (class "Default")
      (node (ref "U2") (pin "P$15") (pinfunction "CLK_P$15") (pintype "bidirectional"))
    )
    (net (code "264") (name "unconnected-(U2-DMA-RX-PadP$23)") (class "Default")
      (node (ref "U2") (pin "P$23") (pinfunction "DMA-RX_P$23") (pintype "bidirectional"))
    )
    (net (code "265") (name "unconnected-(U2-DMA-TX-PadP$22)") (class "Default")
      (node (ref "U2") (pin "P$22") (pinfunction "DMA-TX_P$22") (pintype "bidirectional"))
    )
    (net (code "266") (name "unconnected-(U2-EPC-A-PadP$6)") (class "Default")
      (node (ref "U2") (pin "P$6") (pinfunction "EPC-A_P$6") (pintype "bidirectional"))
    )
    (net (code "267") (name "unconnected-(U2-EPC-B-PadP$7)") (class "Default")
      (node (ref "U2") (pin "P$7") (pinfunction "EPC-B_P$7") (pintype "bidirectional"))
    )
    (net (code "268") (name "unconnected-(U2-GPIO-5-PadP$28)") (class "Default")
      (node (ref "U2") (pin "P$28") (pinfunction "GPIO-5_P$28") (pintype "bidirectional"))
    )
    (net (code "269") (name "unconnected-(U2-GPIO-7-PadP$26)") (class "Default")
      (node (ref "U2") (pin "P$26") (pinfunction "GPIO-7_P$26") (pintype "bidirectional"))
    )
    (net (code "270") (name "unconnected-(U2-GPIO-8-PadP$25)") (class "Default")
      (node (ref "U2") (pin "P$25") (pinfunction "GPIO-8_P$25") (pintype "bidirectional"))
    )
    (net (code "271") (name "unconnected-(U2-GPIO-12-PadP$11)") (class "Default")
      (node (ref "U2") (pin "P$11") (pinfunction "GPIO-12_P$11") (pintype "bidirectional"))
    )
    (net (code "272") (name "unconnected-(U2-GPIO-13-PadP$10)") (class "Default")
      (node (ref "U2") (pin "P$10") (pinfunction "GPIO-13_P$10") (pintype "bidirectional"))
    )
    (net (code "273") (name "unconnected-(U2-MISO-PadP$16)") (class "Default")
      (node (ref "U2") (pin "P$16") (pinfunction "MISO_P$16") (pintype "bidirectional"))
    )
    (net (code "274") (name "unconnected-(U2-MOSI-PadP$14)") (class "Default")
      (node (ref "U2") (pin "P$14") (pinfunction "MOSI_P$14") (pintype "bidirectional"))
    )
    (net (code "275") (name "unconnected-(U2-SEN0-PadP$34)") (class "Default")
      (node (ref "U2") (pin "P$34") (pinfunction "SEN0_P$34") (pintype "bidirectional"))
    )
    (net (code "276") (name "unconnected-(U2-SEN1-PadP$30)") (class "Default")
      (node (ref "U2") (pin "P$30") (pinfunction "SEN1_P$30") (pintype "bidirectional"))
    )
    (net (code "277") (name "unconnected-(U2-SEN2-PadP$31)") (class "Default")
      (node (ref "U2") (pin "P$31") (pinfunction "SEN2_P$31") (pintype "bidirectional"))
    )
    (net (code "278") (name "unconnected-(U2-SEN3-PadP$32)") (class "Default")
      (node (ref "U2") (pin "P$32") (pinfunction "SEN3_P$32") (pintype "bidirectional"))
    )
    (net (code "279") (name "unconnected-(U2-SEN4-PadP$2)") (class "Default")
      (node (ref "U2") (pin "P$2") (pinfunction "SEN4_P$2") (pintype "bidirectional"))
    )
    (net (code "280") (name "unconnected-(U2-SEN5-PadP$3)") (class "Default")
      (node (ref "U2") (pin "P$3") (pinfunction "SEN5_P$3") (pintype "bidirectional"))
    )
    (net (code "281") (name "unconnected-(U2-SEN6-PadP$1)") (class "Default")
      (node (ref "U2") (pin "P$1") (pinfunction "SEN6_P$1") (pintype "bidirectional"))
    )
    (net (code "282") (name "unconnected-(U2-SEN7-PadP$4)") (class "Default")
      (node (ref "U2") (pin "P$4") (pinfunction "SEN7_P$4") (pintype "bidirectional"))
    )
    (net (code "283") (name "unconnected-(U2-SENSE-PWR-PadP$33)") (class "Default")
      (node (ref "U2") (pin "P$33") (pinfunction "SENSE-PWR_P$33") (pintype "bidirectional"))
    )
    (net (code "284") (name "unconnected-(U2-S_CAP-PadP$8)") (class "Default")
      (node (ref "U2") (pin "P$8") (pinfunction "S_CAP_P$8") (pintype "bidirectional"))
    )
    (net (code "285") (name "unconnected-(U4-EN-Pad3)") (class "Default")
      (node (ref "U4") (pin "3") (pinfunction "EN_3") (pintype "bidirectional"))
    )
    (net (code "286") (name "unconnected-(U9A-QH-Pad9)") (class "Default")
      (node (ref "U9") (pin "9") (pinfunction "QH_9") (pintype "output"))
    )
    (net (code "287") (name "unconnected-(U12-ADC6-Pad19)") (class "Default")
      (node (ref "U12") (pin "19") (pinfunction "ADC6_19") (pintype "bidirectional"))
    )
    (net (code "288") (name "unconnected-(U12-ADC7-Pad22)") (class "Default")
      (node (ref "U12") (pin "22") (pinfunction "ADC7_22") (pintype "bidirectional"))
    )
    (net (code "289") (name "unconnected-(U13-INT1-Pad8)") (class "Default")
      (node (ref "U13") (pin "8") (pinfunction "INT1_8") (pintype "bidirectional"))
    )
    (net (code "290") (name "unconnected-(U13-INT2-Pad9)") (class "Default")
      (node (ref "U13") (pin "9") (pinfunction "INT2_9") (pintype "bidirectional"))
    )
    (net (code "291") (name "unconnected-(U13-NC-Pad3)") (class "Default")
      (node (ref "U13") (pin "3") (pinfunction "NC_3") (pintype "bidirectional"))
    )
    (net (code "292") (name "unconnected-(U13-N{slash}C-Pad11)") (class "Default")
      (node (ref "U13") (pin "11") (pinfunction "N/C_11") (pintype "bidirectional"))
    )
    (net (code "293") (name "unconnected-(X2-ID-PadP4)") (class "Default")
      (node (ref "X2") (pin "P4") (pinfunction "ID_P4") (pintype "bidirectional"))
    )
  )
)
